# DRYER_CONTROLLER.net
KiCad netlist of a schematic drawn in EAGLE
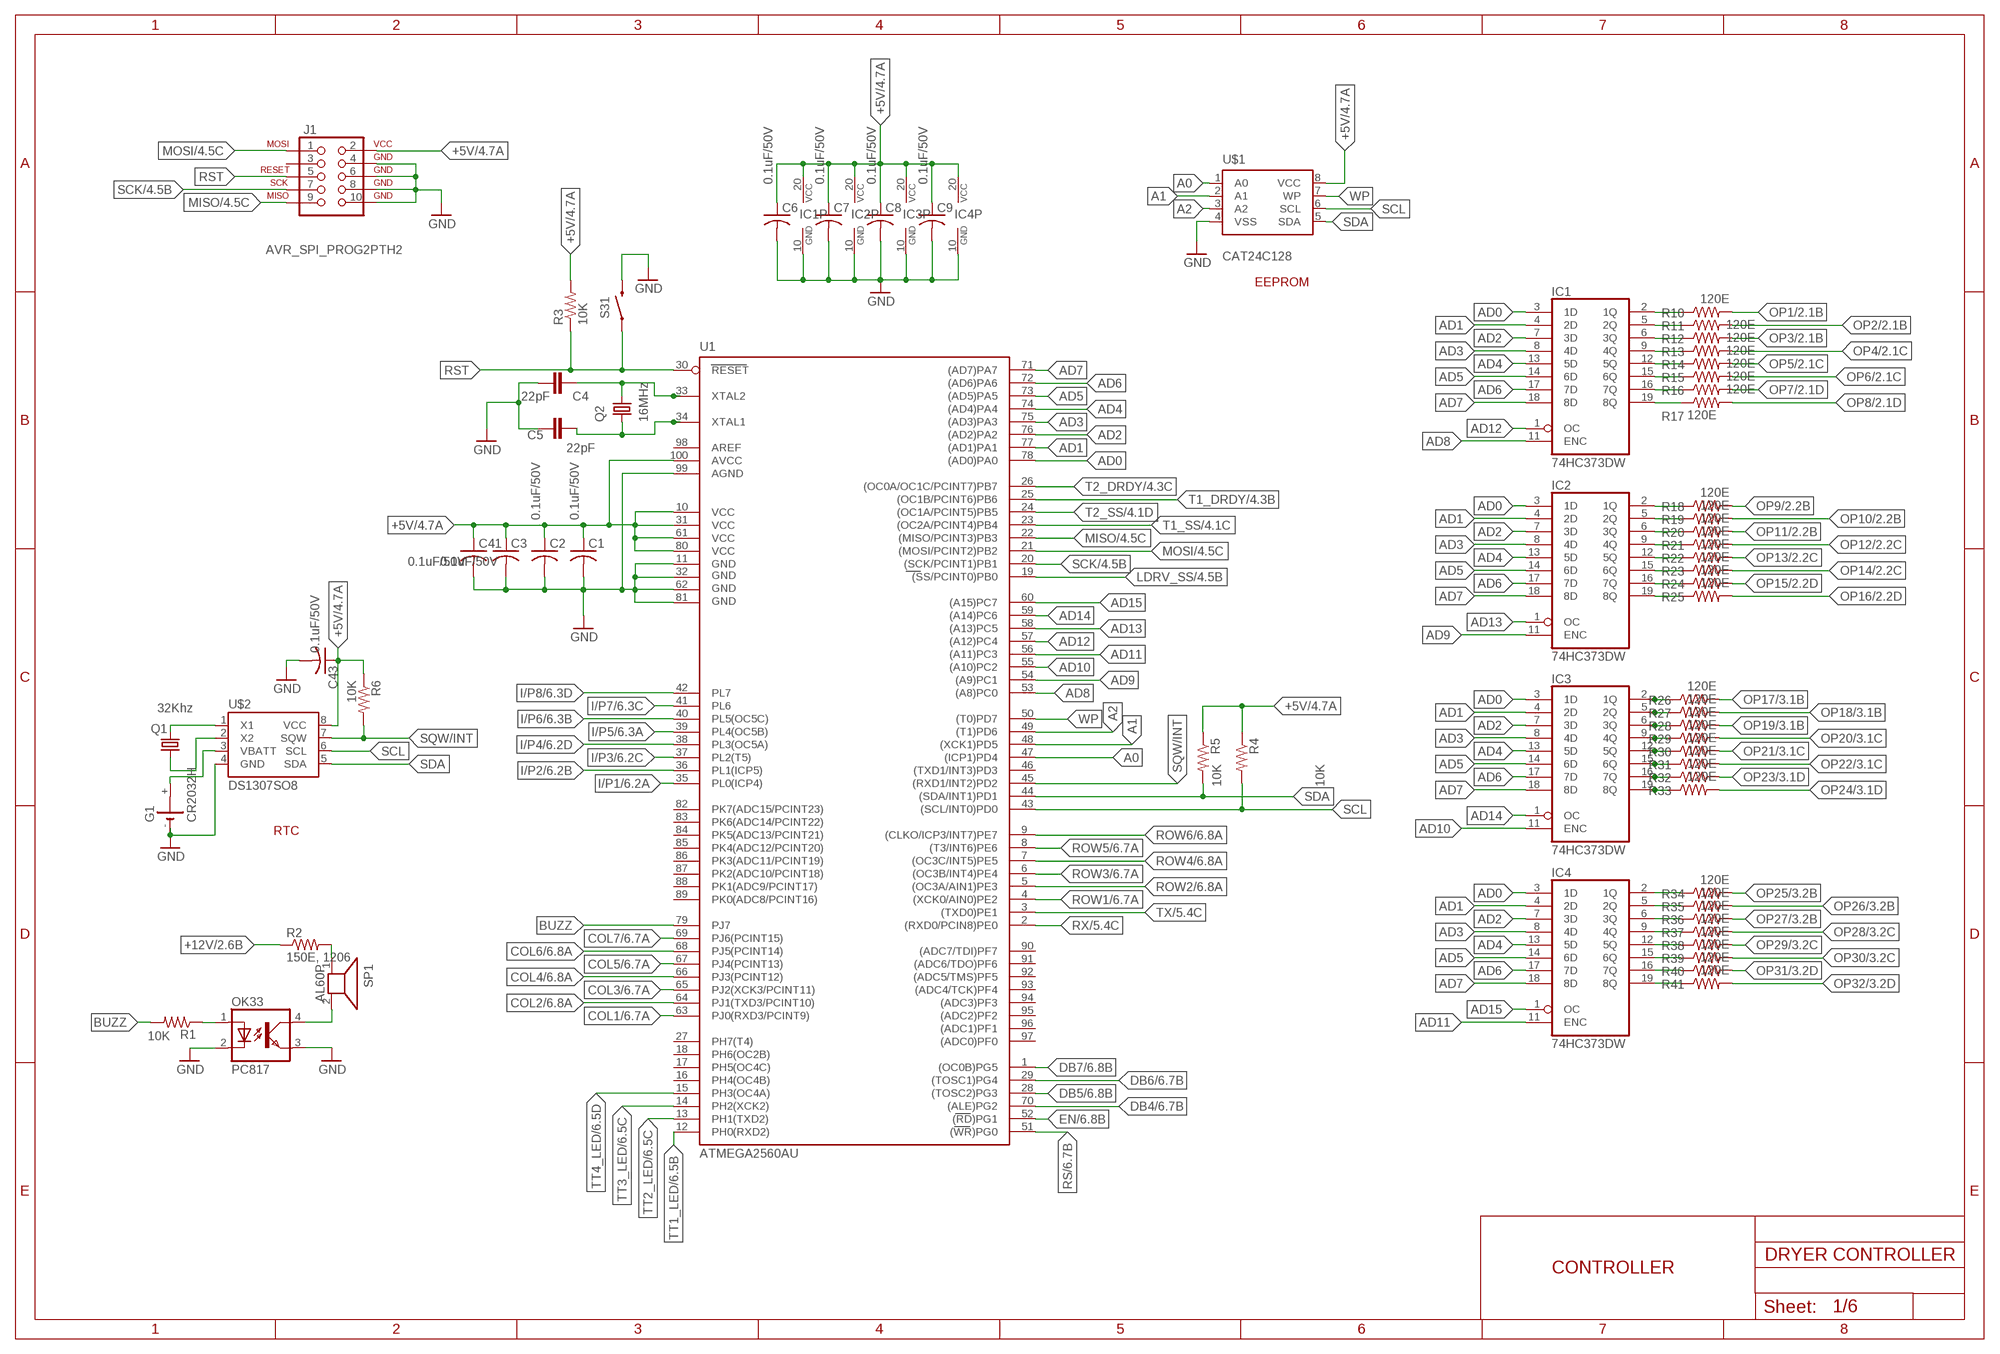
[diagram p0: schematic, sheet 1]
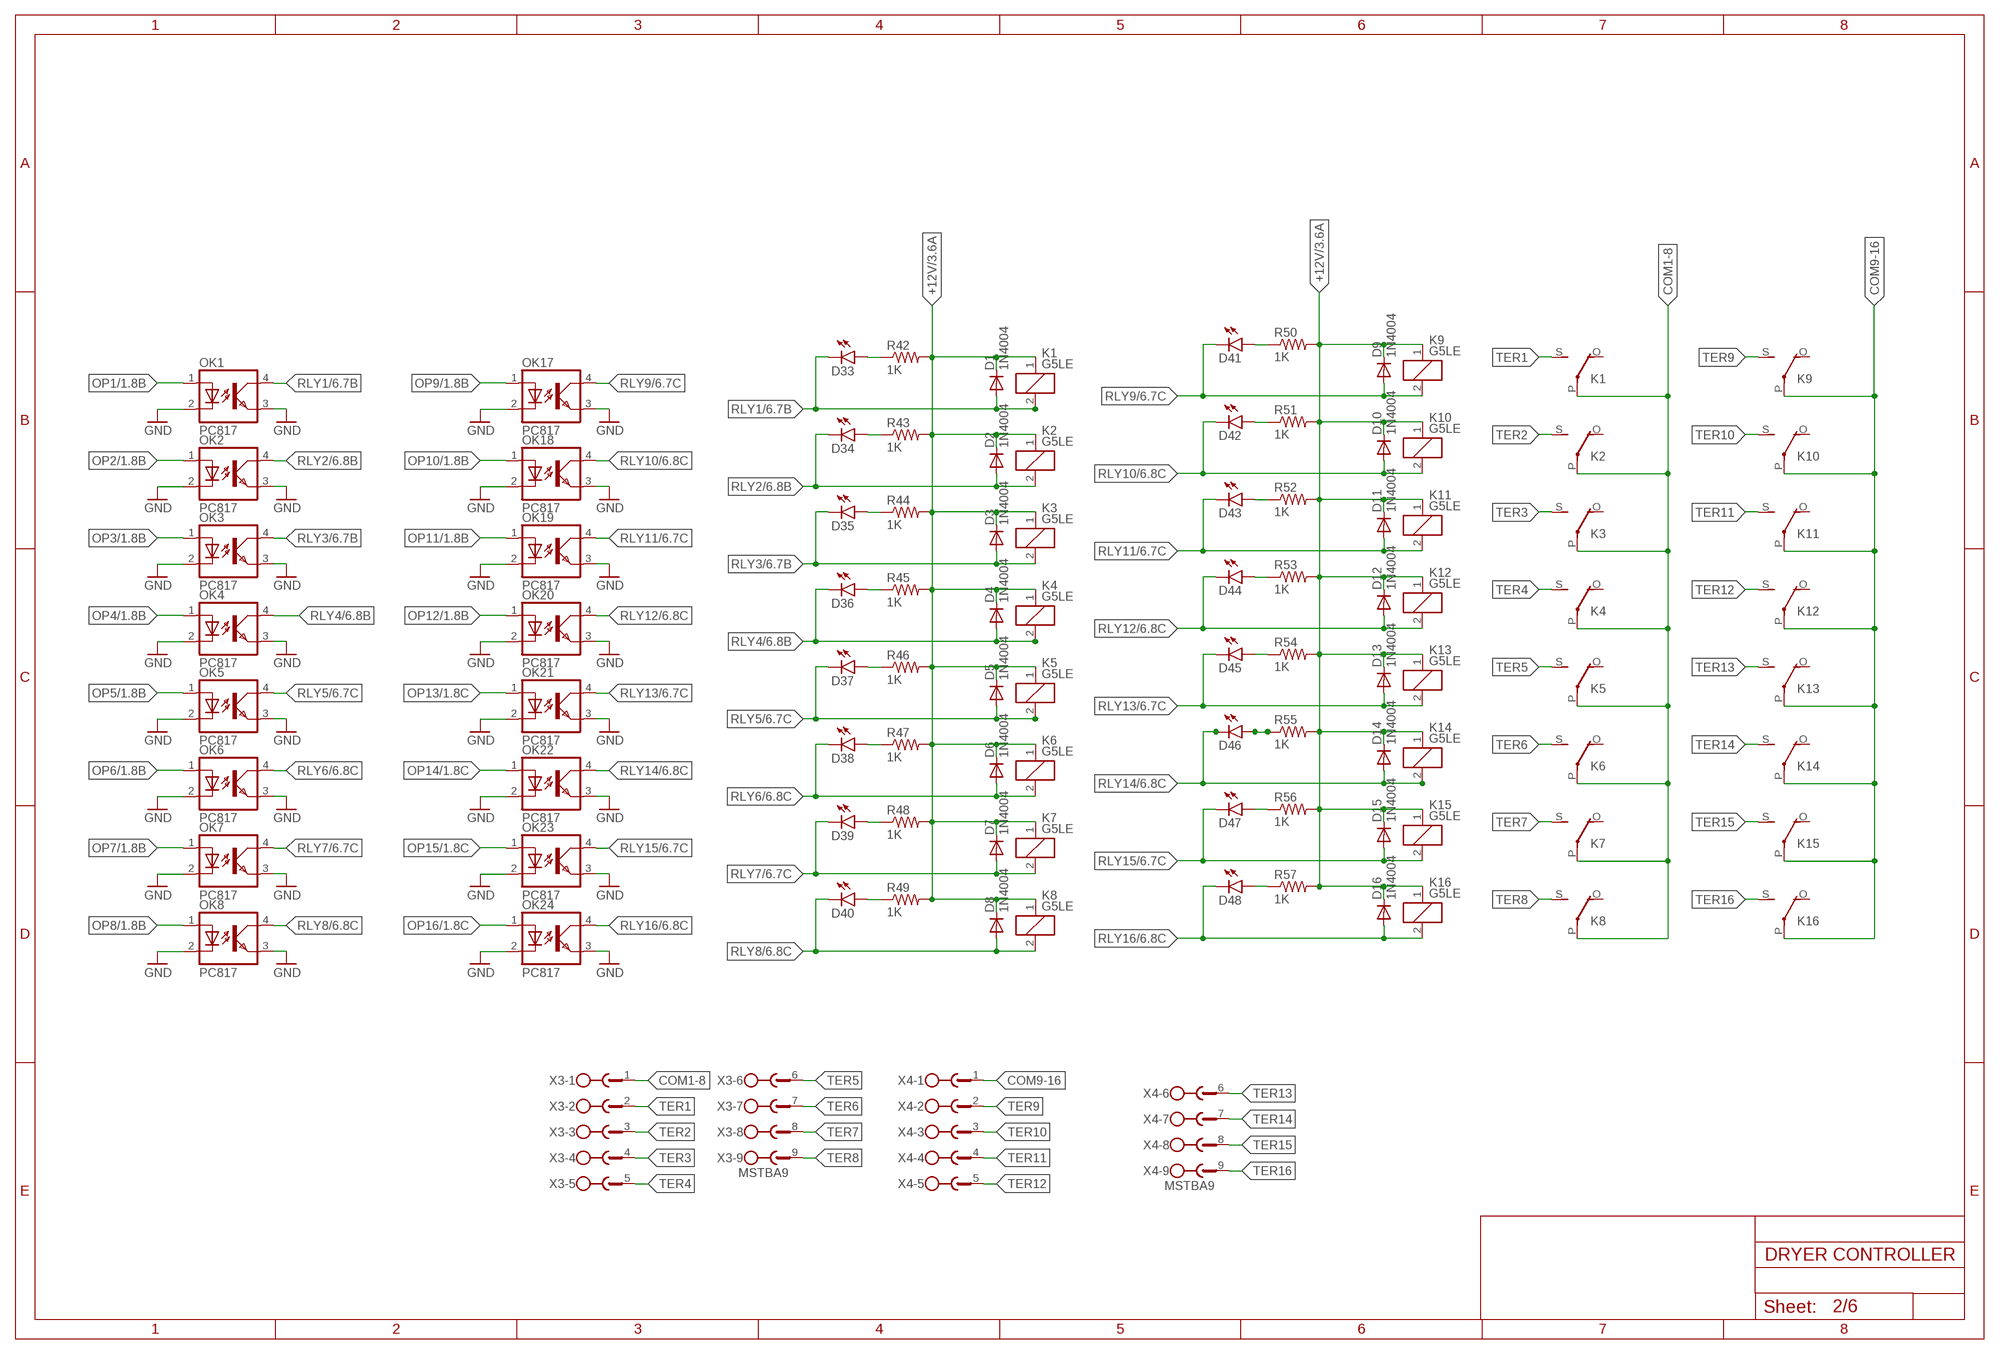
[diagram p1: schematic, sheet 2]
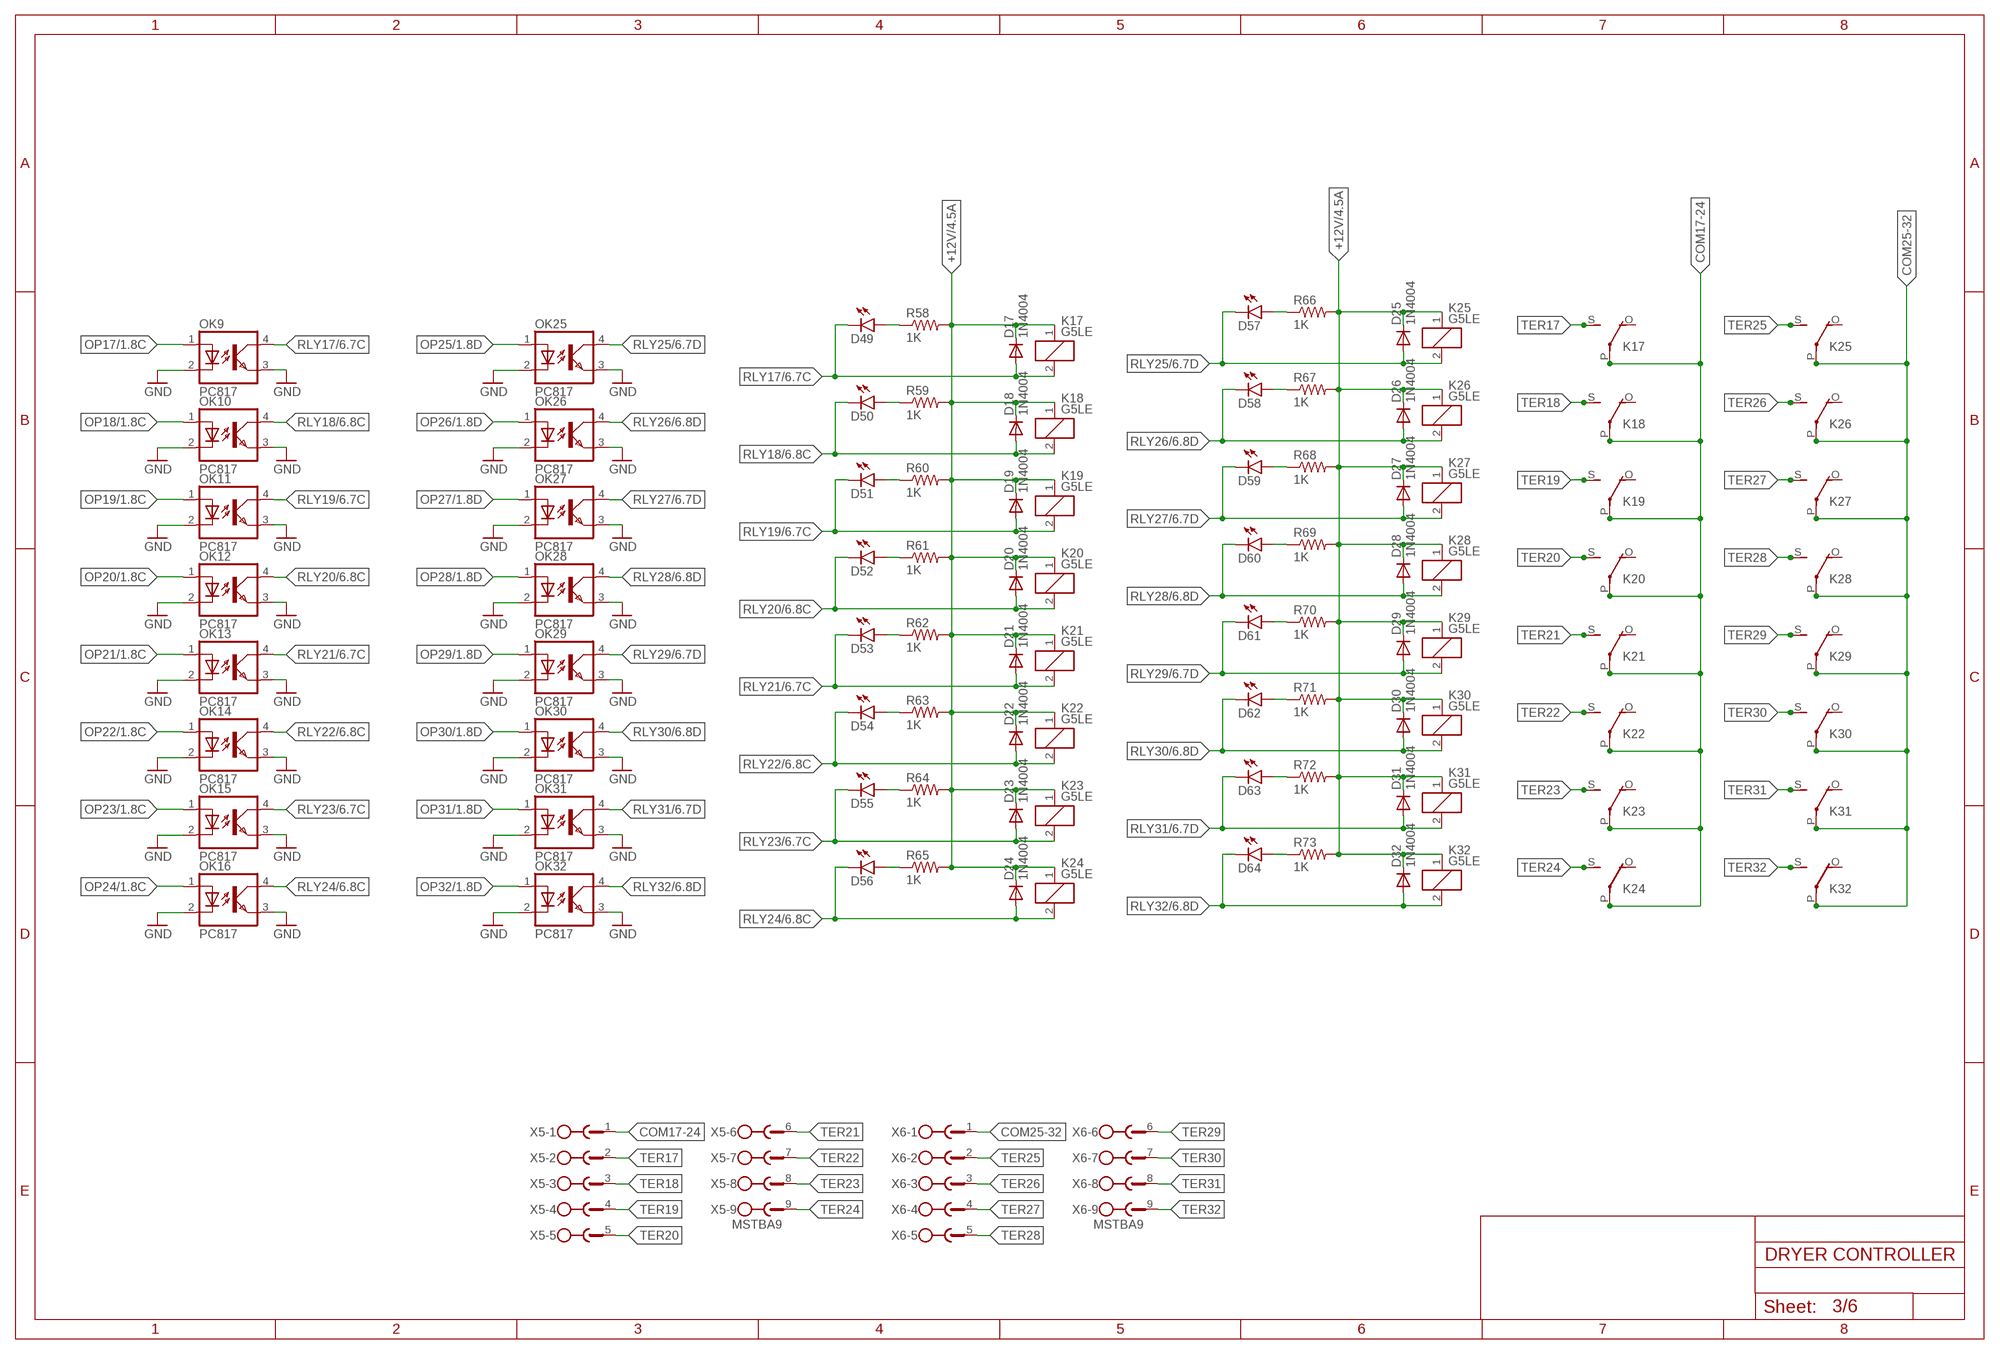
[diagram p2: schematic, sheet 3]
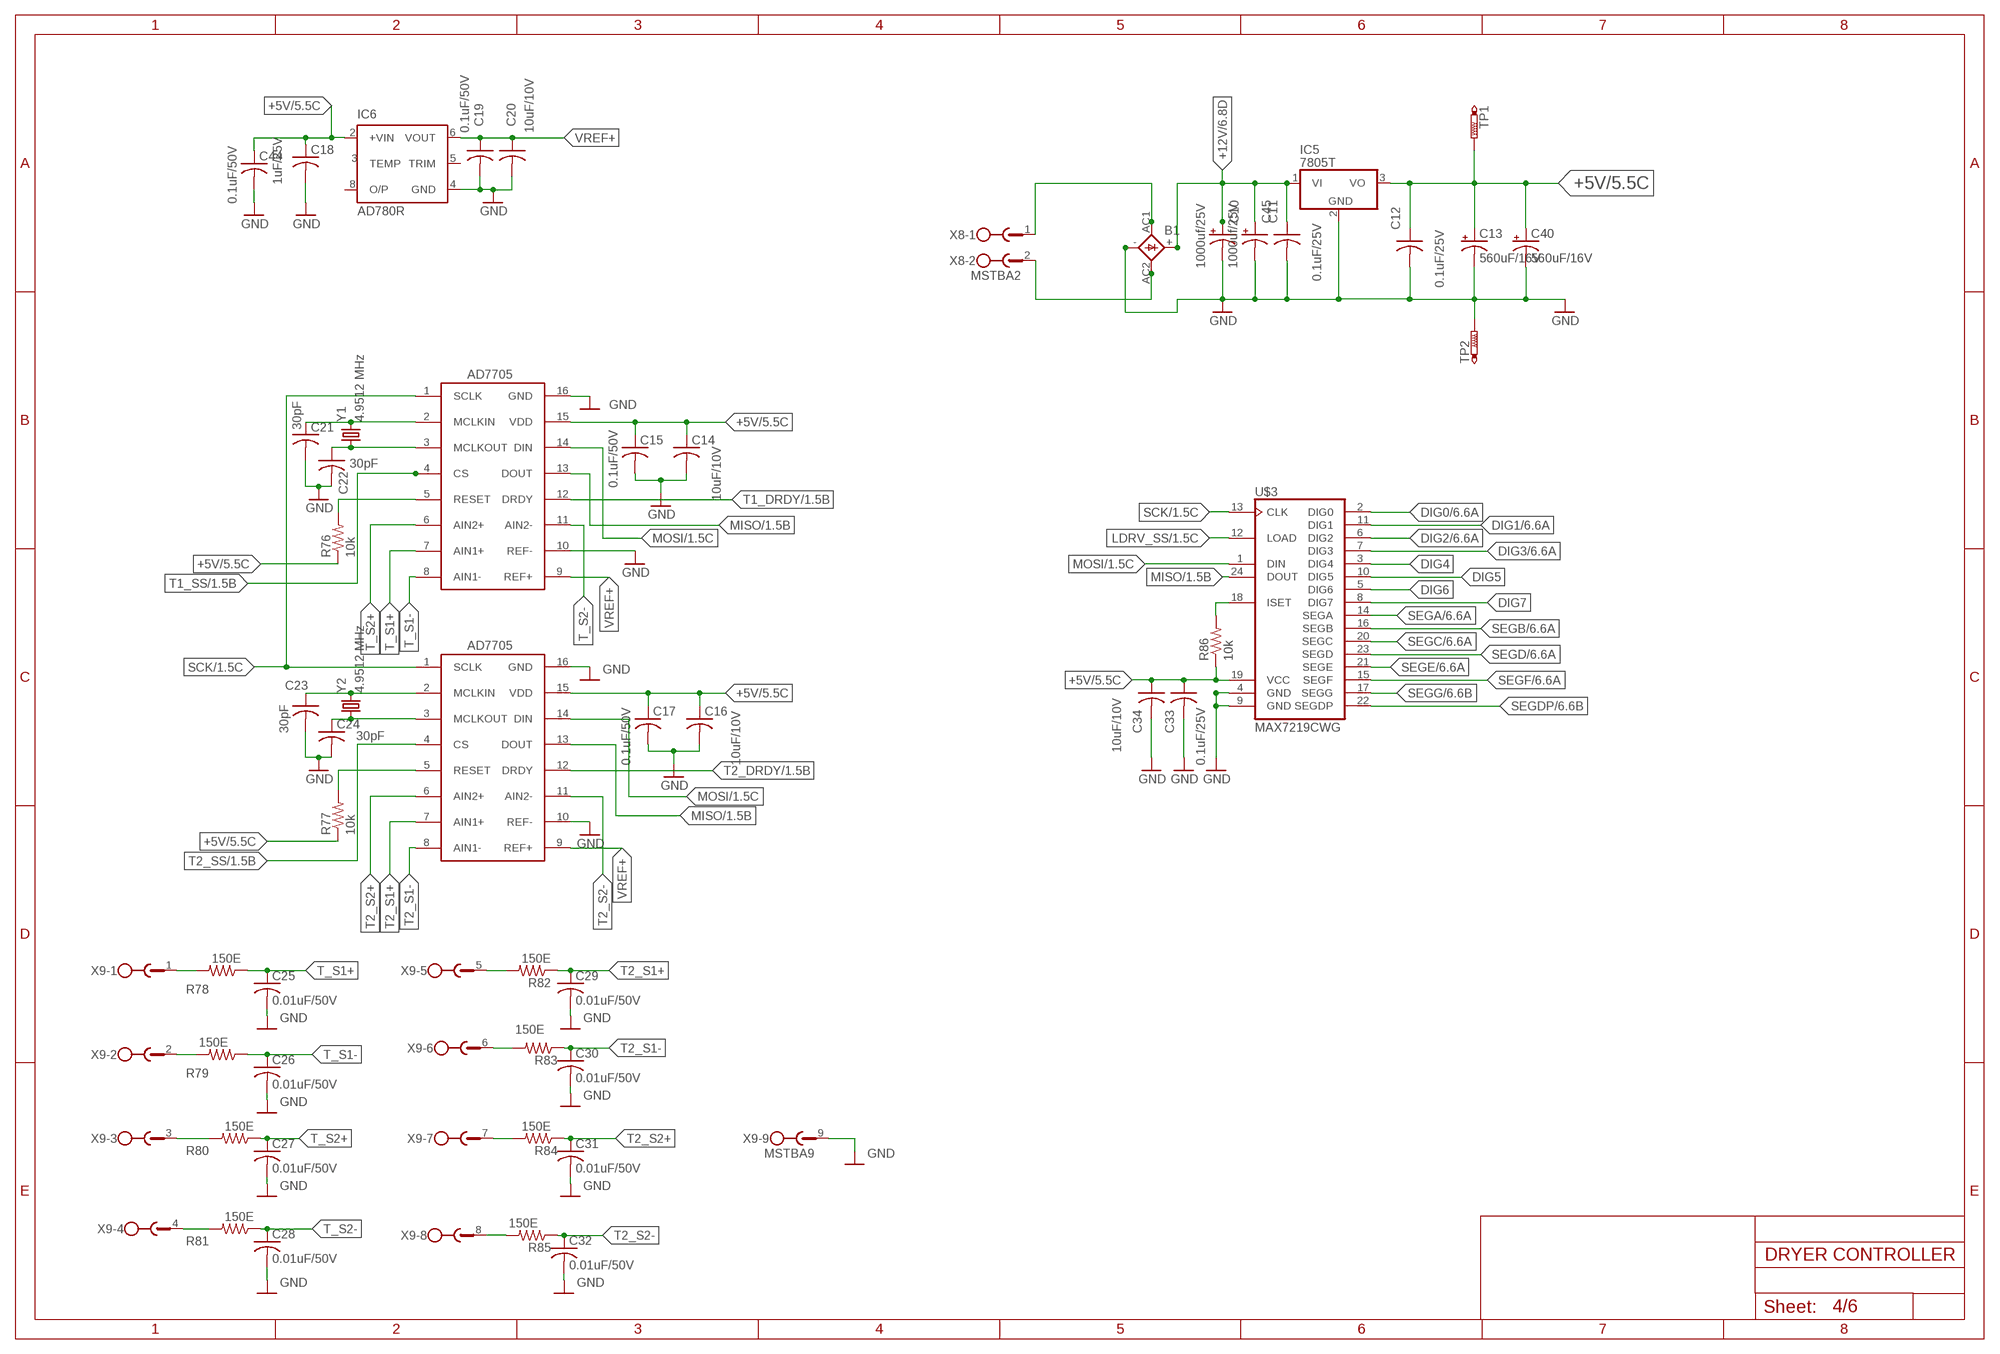
[diagram p3: schematic, sheet 4]
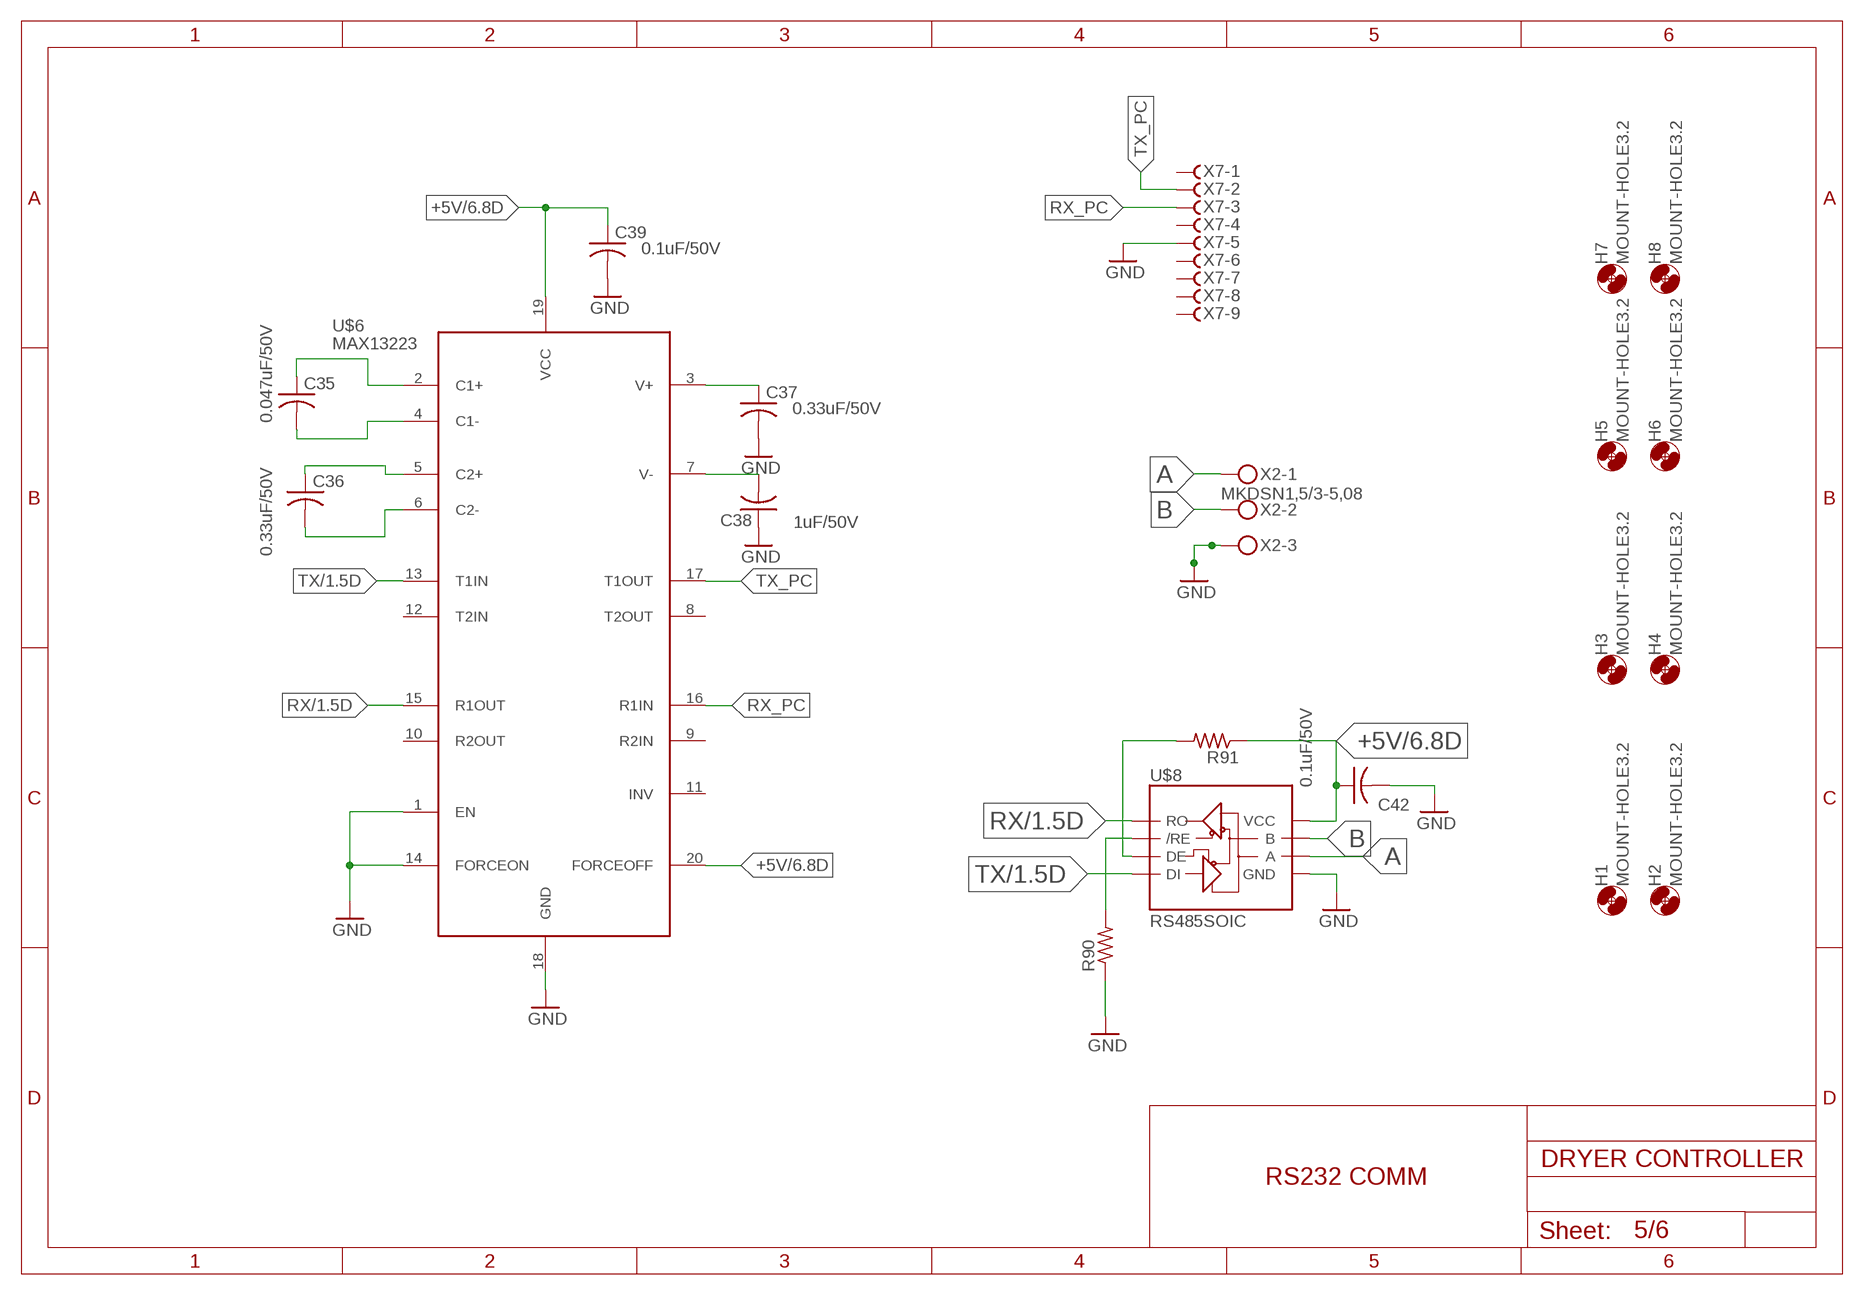
[diagram p4: schematic, sheet 5]
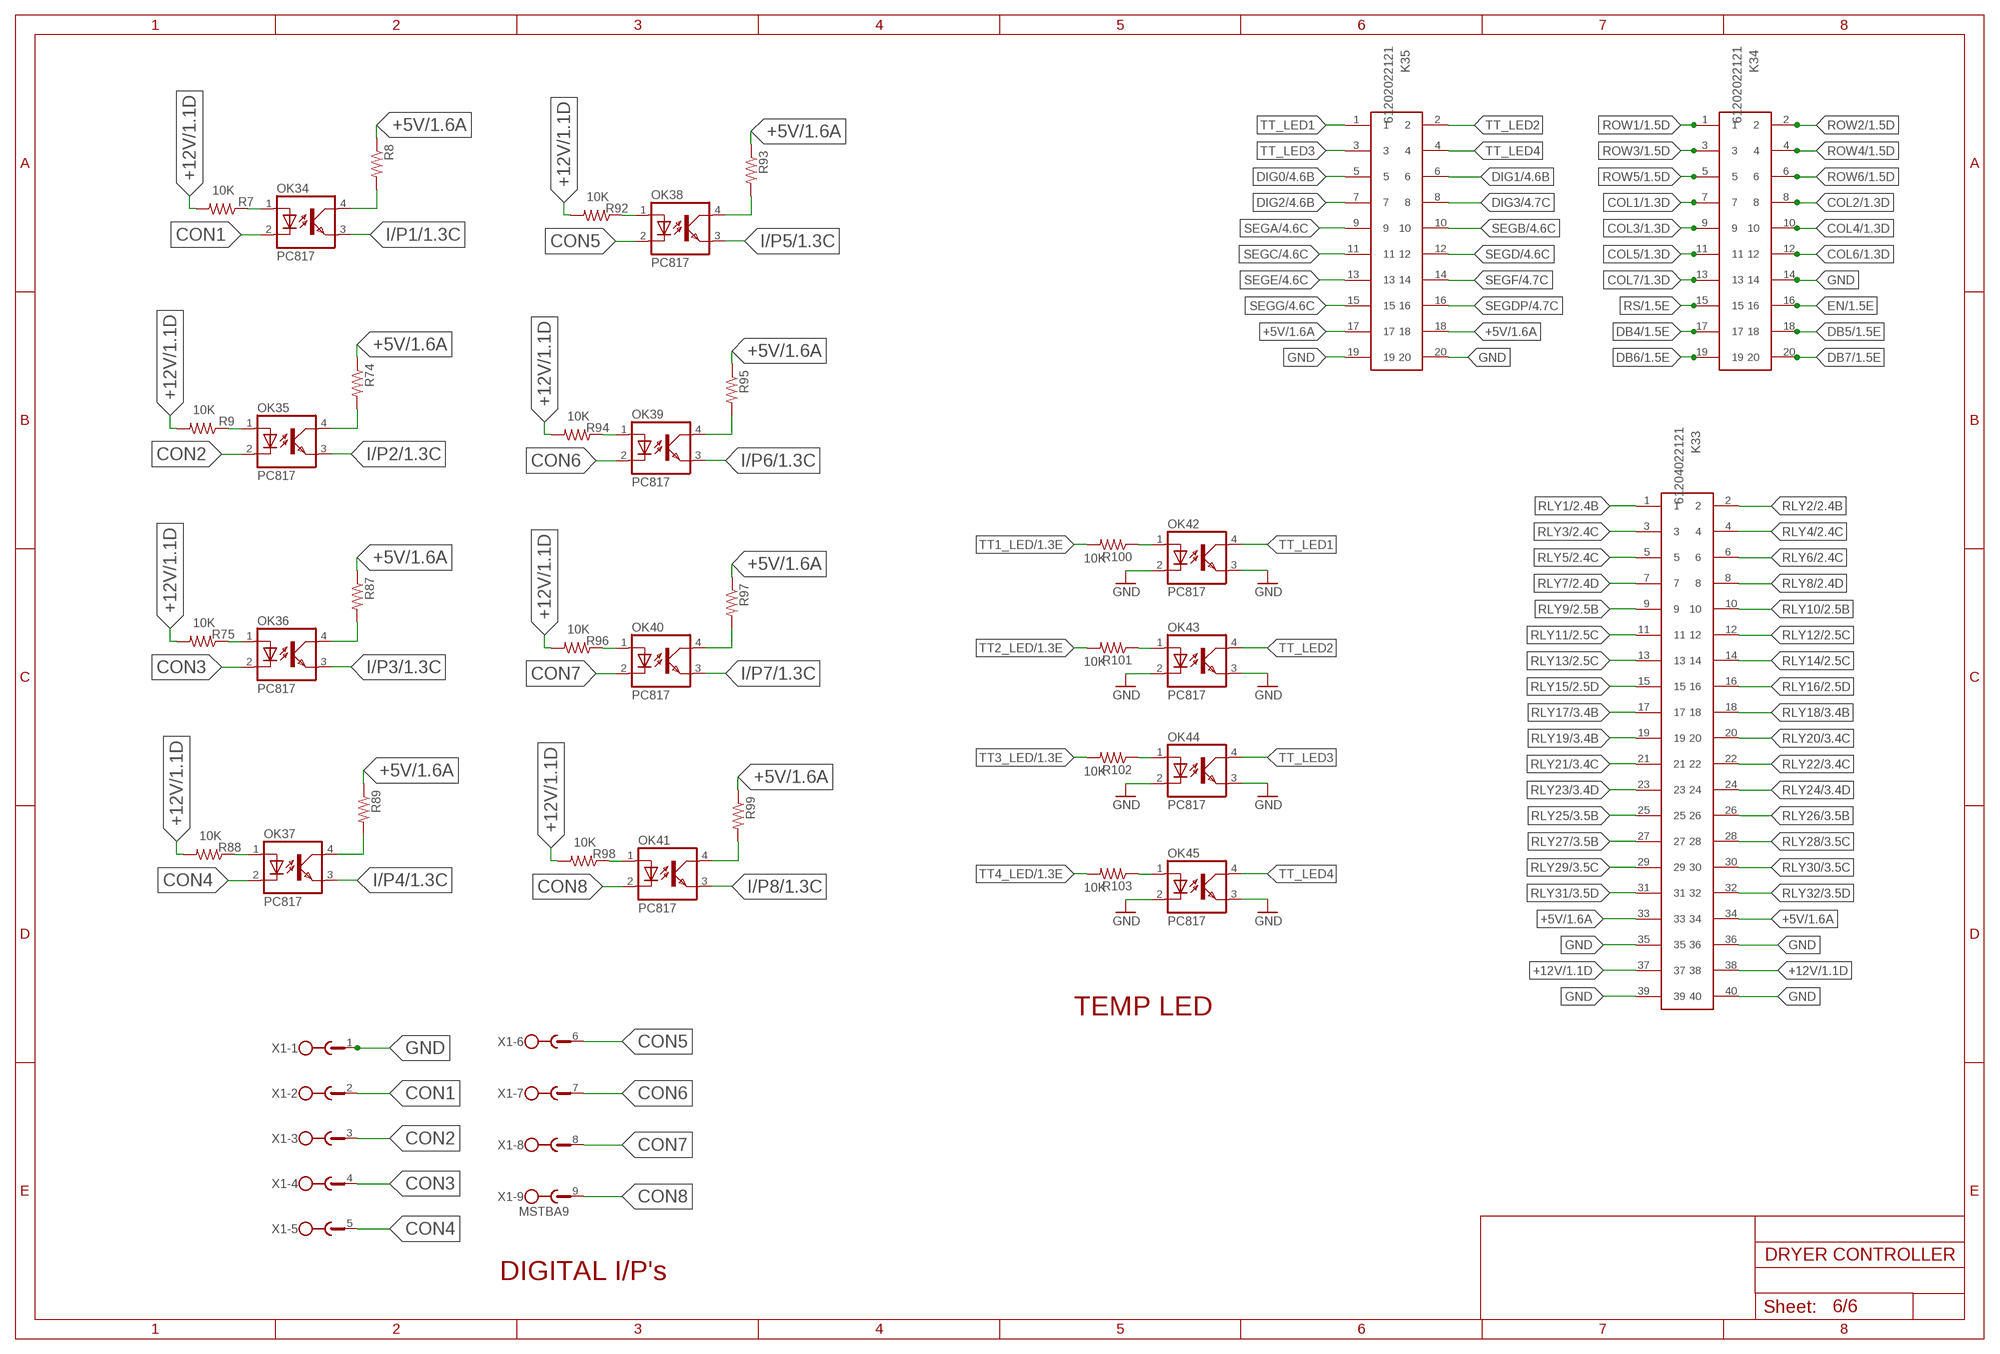
[diagram p5: schematic, sheet 6]

(export (version "E")
  (design (tool "Eeschema 10.0.6"))
  (components
    (comp (ref "B1")
      (value "2KBP")
      (footprint "eagle-import:2KBP")
      (libsource (lib "eagle-import") (part "2KBP"))
    )
    (comp (ref "C10")
      (value "1000uf/25V")
      (footprint "eagle-import:CPOL-RADIAL-1000UF-25V-KIT")
      (libsource (lib "eagle-import") (part "1000UF-25V(PTH)KIT"))
    )
    (comp (ref "C11")
      (value "0.1uF/25V")
      (footprint "eagle-import:C0805K")
      (libsource (lib "eagle-import") (part "C-USC0805K"))
    )
    (comp (ref "C12")
      (value "0.1uF/25V")
      (footprint "eagle-import:C0805K")
      (libsource (lib "eagle-import") (part "C-USC0805K"))
    )
    (comp (ref "C13")
      (value "560uF/16V")
      (footprint "eagle-import:E5-8,5")
      (libsource (lib "eagle-import") (part "CPOL-USE5-8.5"))
    )
    (comp (ref "C14")
      (value "10uF/10V")
      (footprint "eagle-import:C0805K")
      (libsource (lib "eagle-import") (part "C-USC0805K"))
    )
    (comp (ref "C15")
      (value "0.1uF/50V")
      (footprint "eagle-import:C0805K")
      (libsource (lib "eagle-import") (part "C-USC0805K"))
    )
    (comp (ref "C16")
      (value "10uF/10V")
      (footprint "eagle-import:C0805K")
      (libsource (lib "eagle-import") (part "C-USC0805K"))
    )
    (comp (ref "C17")
      (value "0.1uF/50V")
      (footprint "eagle-import:C0805K")
      (libsource (lib "eagle-import") (part "C-USC0805K"))
    )
    (comp (ref "C18")
      (value "1uF/25V")
      (footprint "eagle-import:C0805K")
      (libsource (lib "eagle-import") (part "C-USC0805K"))
    )
    (comp (ref "C19")
      (value "0.1uF/50V")
      (footprint "eagle-import:C0805K")
      (libsource (lib "eagle-import") (part "C-USC0805K"))
    )
    (comp (ref "C20")
      (value "10uF/10V")
      (footprint "eagle-import:C0805K")
      (libsource (lib "eagle-import") (part "C-USC0805K"))
    )
    (comp (ref "C21")
      (value "30pF")
      (footprint "eagle-import:C0603K")
      (libsource (lib "eagle-import") (part "C-USC0603K"))
    )
    (comp (ref "C22")
      (value "30pF")
      (footprint "eagle-import:C0603K")
      (libsource (lib "eagle-import") (part "C-USC0603K"))
    )
    (comp (ref "C23")
      (value "30pF")
      (footprint "eagle-import:C0603K")
      (libsource (lib "eagle-import") (part "C-USC0603K"))
    )
    (comp (ref "C24")
      (value "30pF")
      (footprint "eagle-import:C0603K")
      (libsource (lib "eagle-import") (part "C-USC0603K"))
    )
    (comp (ref "C25")
      (value "0.01uF/50V")
      (footprint "eagle-import:C0603")
      (libsource (lib "eagle-import") (part "C-USC0603"))
    )
    (comp (ref "C26")
      (value "0.01uF/50V")
      (footprint "eagle-import:C0603")
      (libsource (lib "eagle-import") (part "C-USC0603"))
    )
    (comp (ref "C27")
      (value "0.01uF/50V")
      (footprint "eagle-import:C0603")
      (libsource (lib "eagle-import") (part "C-USC0603"))
    )
    (comp (ref "C28")
      (value "0.01uF/50V")
      (footprint "eagle-import:C0603")
      (libsource (lib "eagle-import") (part "C-USC0603"))
    )
    (comp (ref "C29")
      (value "0.01uF/50V")
      (footprint "eagle-import:C0603")
      (libsource (lib "eagle-import") (part "C-USC0603"))
    )
    (comp (ref "C30")
      (value "0.01uF/50V")
      (footprint "eagle-import:C0603")
      (libsource (lib "eagle-import") (part "C-USC0603"))
    )
    (comp (ref "C31")
      (value "0.01uF/50V")
      (footprint "eagle-import:C0603")
      (libsource (lib "eagle-import") (part "C-USC0603"))
    )
    (comp (ref "C32")
      (value "0.01uF/50V")
      (footprint "eagle-import:C0603")
      (libsource (lib "eagle-import") (part "C-USC0603"))
    )
    (comp (ref "C33")
      (value "0.1uF/25V")
      (footprint "eagle-import:C0805K")
      (libsource (lib "eagle-import") (part "C-USC0805K"))
    )
    (comp (ref "C34")
      (value "10uF/10V")
      (footprint "eagle-import:C0805K")
      (libsource (lib "eagle-import") (part "C-USC0805K"))
    )
    (comp (ref "C40")
      (value "560uF/16V")
      (footprint "eagle-import:E5-8,5")
      (libsource (lib "eagle-import") (part "CPOL-USE5-8.5"))
    )
    (comp (ref "C44")
      (value "0.1uF/50V")
      (footprint "eagle-import:C0805K")
      (libsource (lib "eagle-import") (part "C-USC0805K"))
    )
    (comp (ref "C45")
      (value "1000uf/25V")
      (footprint "eagle-import:CPOL-RADIAL-1000UF-25V-KIT")
      (libsource (lib "eagle-import") (part "1000UF-25V(PTH)KIT"))
    )
    (comp (ref "IC5")
      (value "7805T")
      (footprint "eagle-import:TO220H")
      (libsource (lib "eagle-import") (part "78T05"))
    )
    (comp (ref "IC6")
      (value "AD780R")
      (footprint "eagle-import:SO8")
      (fields (field (name "MPN") "AD780BRZ-REEL"))
      (libsource (lib "eagle-import") (part "AD780R"))
    )
    (comp (ref "R76")
      (value "10k")
      (footprint "eagle-import:R0805")
      (libsource (lib "eagle-import") (part "R-US_R0805"))
    )
    (comp (ref "R77")
      (value "10k")
      (footprint "eagle-import:R0805")
      (libsource (lib "eagle-import") (part "R-US_R0805"))
    )
    (comp (ref "R78")
      (value "150E")
      (footprint "eagle-import:R0805")
      (libsource (lib "eagle-import") (part "R-US_R0805"))
    )
    (comp (ref "R79")
      (value "150E")
      (footprint "eagle-import:R0805")
      (libsource (lib "eagle-import") (part "R-US_R0805"))
    )
    (comp (ref "R80")
      (value "150E")
      (footprint "eagle-import:R0805")
      (libsource (lib "eagle-import") (part "R-US_R0805"))
    )
    (comp (ref "R81")
      (value "150E")
      (footprint "eagle-import:R0805")
      (libsource (lib "eagle-import") (part "R-US_R0805"))
    )
    (comp (ref "R82")
      (value "150E")
      (footprint "eagle-import:R0805")
      (libsource (lib "eagle-import") (part "R-US_R0805"))
    )
    (comp (ref "R83")
      (value "150E")
      (footprint "eagle-import:R0805")
      (libsource (lib "eagle-import") (part "R-US_R0805"))
    )
    (comp (ref "R84")
      (value "150E")
      (footprint "eagle-import:R0805")
      (libsource (lib "eagle-import") (part "R-US_R0805"))
    )
    (comp (ref "R85")
      (value "150E")
      (footprint "eagle-import:R0805")
      (libsource (lib "eagle-import") (part "R-US_R0805"))
    )
    (comp (ref "R86")
      (value "10k")
      (footprint "eagle-import:R0805")
      (libsource (lib "eagle-import") (part "R-US_R0805"))
    )
    (comp (ref "TP1")
      (value "PTR1B2,54")
      (footprint "eagle-import:B2,54")
      (libsource (lib "eagle-import") (part "PTR1B2,54"))
    )
    (comp (ref "TP2")
      (value "PTR1B2,54")
      (footprint "eagle-import:B2,54")
      (libsource (lib "eagle-import") (part "PTR1B2,54"))
    )
    (comp (ref "U$3")
      (value "MAX7219CWG")
      (footprint "eagle-import:SO24L")
      (libsource (lib "eagle-import") (part "MAX7219CWG"))
    )
    (comp (ref "U$4")
      (value "AD7705")
      (footprint "eagle-import:SO-16W")
      (libsource (lib "eagle-import") (part "AD7705"))
    )
    (comp (ref "U$5")
      (value "AD7705")
      (footprint "eagle-import:SO-16W")
      (libsource (lib "eagle-import") (part "AD7705"))
    )
    (comp (ref "X8")
      (value "MSTBA2")
      (footprint "eagle-import:MSTBA2")
      (fields (field (name "MF") "FARNELL") (field (name "MPN") "1757242"))
      (libsource (lib "eagle-import") (part "MSTBA2"))
    )
    (comp (ref "X9")
      (value "MSTBA9")
      (footprint "eagle-import:MSTBA9")
      (fields (field (name "MF") "FARNELL") (field (name "MPN") "1757310"))
      (libsource (lib "eagle-import") (part "MSTBA9"))
    )
    (comp (ref "Y1")
      (value "4.9512 MHz")
      (footprint "eagle-import:HC49U-V")
      (libsource (lib "eagle-import") (part "CRYSTALHC49UV"))
    )
    (comp (ref "Y2")
      (value "4.9512 MHz")
      (footprint "eagle-import:HC49U-V")
      (libsource (lib "eagle-import") (part "CRYSTALHC49UV"))
    )
    (comp (ref "D17")
      (value "1N4004")
      (footprint "eagle-import:DO41-10")
      (libsource (lib "eagle-import") (part "1N4004"))
    )
    (comp (ref "D18")
      (value "1N4004")
      (footprint "eagle-import:DO41-10")
      (libsource (lib "eagle-import") (part "1N4004"))
    )
    (comp (ref "D19")
      (value "1N4004")
      (footprint "eagle-import:DO41-10")
      (libsource (lib "eagle-import") (part "1N4004"))
    )
    (comp (ref "D20")
      (value "1N4004")
      (footprint "eagle-import:DO41-10")
      (libsource (lib "eagle-import") (part "1N4004"))
    )
    (comp (ref "D21")
      (value "1N4004")
      (footprint "eagle-import:DO41-10")
      (libsource (lib "eagle-import") (part "1N4004"))
    )
    (comp (ref "D22")
      (value "1N4004")
      (footprint "eagle-import:DO41-10")
      (libsource (lib "eagle-import") (part "1N4004"))
    )
    (comp (ref "D23")
      (value "1N4004")
      (footprint "eagle-import:DO41-10")
      (libsource (lib "eagle-import") (part "1N4004"))
    )
    (comp (ref "D24")
      (value "1N4004")
      (footprint "eagle-import:DO41-10")
      (libsource (lib "eagle-import") (part "1N4004"))
    )
    (comp (ref "D25")
      (value "1N4004")
      (footprint "eagle-import:DO41-10")
      (libsource (lib "eagle-import") (part "1N4004"))
    )
    (comp (ref "D26")
      (value "1N4004")
      (footprint "eagle-import:DO41-10")
      (libsource (lib "eagle-import") (part "1N4004"))
    )
    (comp (ref "D27")
      (value "1N4004")
      (footprint "eagle-import:DO41-10")
      (libsource (lib "eagle-import") (part "1N4004"))
    )
    (comp (ref "D28")
      (value "1N4004")
      (footprint "eagle-import:DO41-10")
      (libsource (lib "eagle-import") (part "1N4004"))
    )
    (comp (ref "D29")
      (value "1N4004")
      (footprint "eagle-import:DO41-10")
      (libsource (lib "eagle-import") (part "1N4004"))
    )
    (comp (ref "D30")
      (value "1N4004")
      (footprint "eagle-import:DO41-10")
      (libsource (lib "eagle-import") (part "1N4004"))
    )
    (comp (ref "D31")
      (value "1N4004")
      (footprint "eagle-import:DO41-10")
      (libsource (lib "eagle-import") (part "1N4004"))
    )
    (comp (ref "D32")
      (value "1N4004")
      (footprint "eagle-import:DO41-10")
      (libsource (lib "eagle-import") (part "1N4004"))
    )
    (comp (ref "D49")
      (value "LED1206")
      (footprint "eagle-import:LED-1206")
      (libsource (lib "eagle-import") (part "LED1206"))
    )
    (comp (ref "D50")
      (value "LED1206")
      (footprint "eagle-import:LED-1206")
      (libsource (lib "eagle-import") (part "LED1206"))
    )
    (comp (ref "D51")
      (value "LED1206")
      (footprint "eagle-import:LED-1206")
      (libsource (lib "eagle-import") (part "LED1206"))
    )
    (comp (ref "D52")
      (value "LED1206")
      (footprint "eagle-import:LED-1206")
      (libsource (lib "eagle-import") (part "LED1206"))
    )
    (comp (ref "D53")
      (value "LED1206")
      (footprint "eagle-import:LED-1206")
      (libsource (lib "eagle-import") (part "LED1206"))
    )
    (comp (ref "D54")
      (value "LED1206")
      (footprint "eagle-import:LED-1206")
      (libsource (lib "eagle-import") (part "LED1206"))
    )
    (comp (ref "D55")
      (value "LED1206")
      (footprint "eagle-import:LED-1206")
      (libsource (lib "eagle-import") (part "LED1206"))
    )
    (comp (ref "D56")
      (value "LED1206")
      (footprint "eagle-import:LED-1206")
      (libsource (lib "eagle-import") (part "LED1206"))
    )
    (comp (ref "D57")
      (value "LED1206")
      (footprint "eagle-import:LED-1206")
      (libsource (lib "eagle-import") (part "LED1206"))
    )
    (comp (ref "D58")
      (value "LED1206")
      (footprint "eagle-import:LED-1206")
      (libsource (lib "eagle-import") (part "LED1206"))
    )
    (comp (ref "D59")
      (value "LED1206")
      (footprint "eagle-import:LED-1206")
      (libsource (lib "eagle-import") (part "LED1206"))
    )
    (comp (ref "D60")
      (value "LED1206")
      (footprint "eagle-import:LED-1206")
      (libsource (lib "eagle-import") (part "LED1206"))
    )
    (comp (ref "D61")
      (value "LED1206")
      (footprint "eagle-import:LED-1206")
      (libsource (lib "eagle-import") (part "LED1206"))
    )
    (comp (ref "D62")
      (value "LED1206")
      (footprint "eagle-import:LED-1206")
      (libsource (lib "eagle-import") (part "LED1206"))
    )
    (comp (ref "D63")
      (value "LED1206")
      (footprint "eagle-import:LED-1206")
      (libsource (lib "eagle-import") (part "LED1206"))
    )
    (comp (ref "D64")
      (value "LED1206")
      (footprint "eagle-import:LED-1206")
      (libsource (lib "eagle-import") (part "LED1206"))
    )
    (comp (ref "K17")
      (value "G5LE")
      (footprint "eagle-import:G5LE")
      (libsource (lib "eagle-import") (part "G5LE"))
    )
    (comp (ref "K18")
      (value "G5LE")
      (footprint "eagle-import:G5LE")
      (libsource (lib "eagle-import") (part "G5LE"))
    )
    (comp (ref "K19")
      (value "G5LE")
      (footprint "eagle-import:G5LE")
      (libsource (lib "eagle-import") (part "G5LE"))
    )
    (comp (ref "K20")
      (value "G5LE")
      (footprint "eagle-import:G5LE")
      (libsource (lib "eagle-import") (part "G5LE"))
    )
    (comp (ref "K21")
      (value "G5LE")
      (footprint "eagle-import:G5LE")
      (libsource (lib "eagle-import") (part "G5LE"))
    )
    (comp (ref "K22")
      (value "G5LE")
      (footprint "eagle-import:G5LE")
      (libsource (lib "eagle-import") (part "G5LE"))
    )
    (comp (ref "K23")
      (value "G5LE")
      (footprint "eagle-import:G5LE")
      (libsource (lib "eagle-import") (part "G5LE"))
    )
    (comp (ref "K24")
      (value "G5LE")
      (footprint "eagle-import:G5LE")
      (libsource (lib "eagle-import") (part "G5LE"))
    )
    (comp (ref "K25")
      (value "G5LE")
      (footprint "eagle-import:G5LE")
      (libsource (lib "eagle-import") (part "G5LE"))
    )
    (comp (ref "K26")
      (value "G5LE")
      (footprint "eagle-import:G5LE")
      (libsource (lib "eagle-import") (part "G5LE"))
    )
    (comp (ref "K27")
      (value "G5LE")
      (footprint "eagle-import:G5LE")
      (libsource (lib "eagle-import") (part "G5LE"))
    )
    (comp (ref "K28")
      (value "G5LE")
      (footprint "eagle-import:G5LE")
      (libsource (lib "eagle-import") (part "G5LE"))
    )
    (comp (ref "K29")
      (value "G5LE")
      (footprint "eagle-import:G5LE")
      (libsource (lib "eagle-import") (part "G5LE"))
    )
    (comp (ref "K30")
      (value "G5LE")
      (footprint "eagle-import:G5LE")
      (libsource (lib "eagle-import") (part "G5LE"))
    )
    (comp (ref "K31")
      (value "G5LE")
      (footprint "eagle-import:G5LE")
      (libsource (lib "eagle-import") (part "G5LE"))
    )
    (comp (ref "K32")
      (value "G5LE")
      (footprint "eagle-import:G5LE")
      (libsource (lib "eagle-import") (part "G5LE"))
    )
    (comp (ref "OK9")
      (value "PC817")
      (footprint "eagle-import:DIL04")
      (fields (field (name "MPN") "PC817X4J000F"))
      (libsource (lib "eagle-import") (part "PC817"))
    )
    (comp (ref "OK10")
      (value "PC817")
      (footprint "eagle-import:DIL04")
      (fields (field (name "MPN") "PC817X4J000F"))
      (libsource (lib "eagle-import") (part "PC817"))
    )
    (comp (ref "OK11")
      (value "PC817")
      (footprint "eagle-import:DIL04")
      (fields (field (name "MPN") "PC817X4J000F"))
      (libsource (lib "eagle-import") (part "PC817"))
    )
    (comp (ref "OK12")
      (value "PC817")
      (footprint "eagle-import:DIL04")
      (fields (field (name "MPN") "PC817X4J000F"))
      (libsource (lib "eagle-import") (part "PC817"))
    )
    (comp (ref "OK13")
      (value "PC817")
      (footprint "eagle-import:DIL04")
      (fields (field (name "MPN") "PC817X4J000F"))
      (libsource (lib "eagle-import") (part "PC817"))
    )
    (comp (ref "OK14")
      (value "PC817")
      (footprint "eagle-import:DIL04")
      (fields (field (name "MPN") "PC817X4J000F"))
      (libsource (lib "eagle-import") (part "PC817"))
    )
    (comp (ref "OK15")
      (value "PC817")
      (footprint "eagle-import:DIL04")
      (fields (field (name "MPN") "PC817X4J000F"))
      (libsource (lib "eagle-import") (part "PC817"))
    )
    (comp (ref "OK16")
      (value "PC817")
      (footprint "eagle-import:DIL04")
      (fields (field (name "MPN") "PC817X4J000F"))
      (libsource (lib "eagle-import") (part "PC817"))
    )
    (comp (ref "OK25")
      (value "PC817")
      (footprint "eagle-import:DIL04")
      (fields (field (name "MPN") "PC817X4J000F"))
      (libsource (lib "eagle-import") (part "PC817"))
    )
    (comp (ref "OK26")
      (value "PC817")
      (footprint "eagle-import:DIL04")
      (fields (field (name "MPN") "PC817X4J000F"))
      (libsource (lib "eagle-import") (part "PC817"))
    )
    (comp (ref "OK27")
      (value "PC817")
      (footprint "eagle-import:DIL04")
      (fields (field (name "MPN") "PC817X4J000F"))
      (libsource (lib "eagle-import") (part "PC817"))
    )
    (comp (ref "OK28")
      (value "PC817")
      (footprint "eagle-import:DIL04")
      (fields (field (name "MPN") "PC817X4J000F"))
      (libsource (lib "eagle-import") (part "PC817"))
    )
    (comp (ref "OK29")
      (value "PC817")
      (footprint "eagle-import:DIL04")
      (fields (field (name "MPN") "PC817X4J000F"))
      (libsource (lib "eagle-import") (part "PC817"))
    )
    (comp (ref "OK30")
      (value "PC817")
      (footprint "eagle-import:DIL04")
      (fields (field (name "MPN") "PC817X4J000F"))
      (libsource (lib "eagle-import") (part "PC817"))
    )
    (comp (ref "OK31")
      (value "PC817")
      (footprint "eagle-import:DIL04")
      (fields (field (name "MPN") "PC817X4J000F"))
      (libsource (lib "eagle-import") (part "PC817"))
    )
    (comp (ref "OK32")
      (value "PC817")
      (footprint "eagle-import:DIL04")
      (fields (field (name "MPN") "PC817X4J000F"))
      (libsource (lib "eagle-import") (part "PC817"))
    )
    (comp (ref "R58")
      (value "1K")
      (footprint "eagle-import:R0805")
      (libsource (lib "eagle-import") (part "R-US_R0805"))
    )
    (comp (ref "R59")
      (value "1K")
      (footprint "eagle-import:R0805")
      (libsource (lib "eagle-import") (part "R-US_R0805"))
    )
    (comp (ref "R60")
      (value "1K")
      (footprint "eagle-import:R0805")
      (libsource (lib "eagle-import") (part "R-US_R0805"))
    )
    (comp (ref "R61")
      (value "1K")
      (footprint "eagle-import:R0805")
      (libsource (lib "eagle-import") (part "R-US_R0805"))
    )
    (comp (ref "R62")
      (value "1K")
      (footprint "eagle-import:R0805")
      (libsource (lib "eagle-import") (part "R-US_R0805"))
    )
    (comp (ref "R63")
      (value "1K")
      (footprint "eagle-import:R0805")
      (libsource (lib "eagle-import") (part "R-US_R0805"))
    )
    (comp (ref "R64")
      (value "1K")
      (footprint "eagle-import:R0805")
      (libsource (lib "eagle-import") (part "R-US_R0805"))
    )
    (comp (ref "R65")
      (value "1K")
      (footprint "eagle-import:R0805")
      (libsource (lib "eagle-import") (part "R-US_R0805"))
    )
    (comp (ref "R66")
      (value "1K")
      (footprint "eagle-import:R0805")
      (libsource (lib "eagle-import") (part "R-US_R0805"))
    )
    (comp (ref "R67")
      (value "1K")
      (footprint "eagle-import:R0805")
      (libsource (lib "eagle-import") (part "R-US_R0805"))
    )
    (comp (ref "R68")
      (value "1K")
      (footprint "eagle-import:R0805")
      (libsource (lib "eagle-import") (part "R-US_R0805"))
    )
    (comp (ref "R69")
      (value "1K")
      (footprint "eagle-import:R0805")
      (libsource (lib "eagle-import") (part "R-US_R0805"))
    )
    (comp (ref "R70")
      (value "1K")
      (footprint "eagle-import:R0805")
      (libsource (lib "eagle-import") (part "R-US_R0805"))
    )
    (comp (ref "R71")
      (value "1K")
      (footprint "eagle-import:R0805")
      (libsource (lib "eagle-import") (part "R-US_R0805"))
    )
    (comp (ref "R72")
      (value "1K")
      (footprint "eagle-import:R0805")
      (libsource (lib "eagle-import") (part "R-US_R0805"))
    )
    (comp (ref "R73")
      (value "1K")
      (footprint "eagle-import:R0805")
      (libsource (lib "eagle-import") (part "R-US_R0805"))
    )
    (comp (ref "X5")
      (value "MSTBA9")
      (footprint "eagle-import:MSTBA9")
      (fields (field (name "MF") "FARNELL") (field (name "MPN") "1757310"))
      (libsource (lib "eagle-import") (part "MSTBA9"))
    )
    (comp (ref "X6")
      (value "MSTBA9")
      (footprint "eagle-import:MSTBA9")
      (fields (field (name "MF") "FARNELL") (field (name "MPN") "1757310"))
      (libsource (lib "eagle-import") (part "MSTBA9"))
    )
    (comp (ref "K33")
      (value "61204022121")
      (footprint "eagle-import:61204022121")
      (libsource (lib "eagle-import") (part "61204022121"))
    )
    (comp (ref "K34")
      (value "61202022121")
      (footprint "eagle-import:61202022121")
      (libsource (lib "eagle-import") (part "61202022121"))
    )
    (comp (ref "K35")
      (value "61202022121")
      (footprint "eagle-import:61202022121")
      (libsource (lib "eagle-import") (part "61202022121"))
    )
    (comp (ref "OK34")
      (value "PC817")
      (footprint "eagle-import:DIL04")
      (fields (field (name "MPN") "PC817X4J000F"))
      (libsource (lib "eagle-import") (part "PC817"))
    )
    (comp (ref "OK35")
      (value "PC817")
      (footprint "eagle-import:DIL04")
      (fields (field (name "MPN") "PC817X4J000F"))
      (libsource (lib "eagle-import") (part "PC817"))
    )
    (comp (ref "OK36")
      (value "PC817")
      (footprint "eagle-import:DIL04")
      (fields (field (name "MPN") "PC817X4J000F"))
      (libsource (lib "eagle-import") (part "PC817"))
    )
    (comp (ref "OK37")
      (value "PC817")
      (footprint "eagle-import:DIL04")
      (fields (field (name "MPN") "PC817X4J000F"))
      (libsource (lib "eagle-import") (part "PC817"))
    )
    (comp (ref "OK38")
      (value "PC817")
      (footprint "eagle-import:DIL04")
      (fields (field (name "MPN") "PC817X4J000F"))
      (libsource (lib "eagle-import") (part "PC817"))
    )
    (comp (ref "OK39")
      (value "PC817")
      (footprint "eagle-import:DIL04")
      (fields (field (name "MPN") "PC817X4J000F"))
      (libsource (lib "eagle-import") (part "PC817"))
    )
    (comp (ref "OK40")
      (value "PC817")
      (footprint "eagle-import:DIL04")
      (fields (field (name "MPN") "PC817X4J000F"))
      (libsource (lib "eagle-import") (part "PC817"))
    )
    (comp (ref "OK41")
      (value "PC817")
      (footprint "eagle-import:DIL04")
      (fields (field (name "MPN") "PC817X4J000F"))
      (libsource (lib "eagle-import") (part "PC817"))
    )
    (comp (ref "OK42")
      (value "PC817")
      (footprint "eagle-import:DIL04")
      (fields (field (name "MPN") "PC817X4J000F"))
      (libsource (lib "eagle-import") (part "PC817"))
    )
    (comp (ref "OK43")
      (value "PC817")
      (footprint "eagle-import:DIL04")
      (fields (field (name "MPN") "PC817X4J000F"))
      (libsource (lib "eagle-import") (part "PC817"))
    )
    (comp (ref "OK44")
      (value "PC817")
      (footprint "eagle-import:DIL04")
      (fields (field (name "MPN") "PC817X4J000F"))
      (libsource (lib "eagle-import") (part "PC817"))
    )
    (comp (ref "OK45")
      (value "PC817")
      (footprint "eagle-import:DIL04")
      (fields (field (name "MPN") "PC817X4J000F"))
      (libsource (lib "eagle-import") (part "PC817"))
    )
    (comp (ref "R7")
      (value "10K")
      (footprint "eagle-import:R0805")
      (libsource (lib "eagle-import") (part "R-US_R0805"))
    )
    (comp (ref "R8")
      (value "R-US_R1206")
      (footprint "eagle-import:R1206")
      (libsource (lib "eagle-import") (part "R-US_R1206"))
    )
    (comp (ref "R9")
      (value "10K")
      (footprint "eagle-import:R0805")
      (libsource (lib "eagle-import") (part "R-US_R0805"))
    )
    (comp (ref "R74")
      (value "R-US_R1206")
      (footprint "eagle-import:R1206")
      (libsource (lib "eagle-import") (part "R-US_R1206"))
    )
    (comp (ref "R75")
      (value "10K")
      (footprint "eagle-import:R0805")
      (libsource (lib "eagle-import") (part "R-US_R0805"))
    )
    (comp (ref "R87")
      (value "R-US_R1206")
      (footprint "eagle-import:R1206")
      (libsource (lib "eagle-import") (part "R-US_R1206"))
    )
    (comp (ref "R88")
      (value "10K")
      (footprint "eagle-import:R0805")
      (libsource (lib "eagle-import") (part "R-US_R0805"))
    )
    (comp (ref "R89")
      (value "R-US_R1206")
      (footprint "eagle-import:R1206")
      (libsource (lib "eagle-import") (part "R-US_R1206"))
    )
    (comp (ref "R92")
      (value "10K")
      (footprint "eagle-import:R0805")
      (libsource (lib "eagle-import") (part "R-US_R0805"))
    )
    (comp (ref "R93")
      (value "R-US_R1206")
      (footprint "eagle-import:R1206")
      (libsource (lib "eagle-import") (part "R-US_R1206"))
    )
    (comp (ref "R94")
      (value "10K")
      (footprint "eagle-import:R0805")
      (libsource (lib "eagle-import") (part "R-US_R0805"))
    )
    (comp (ref "R95")
      (value "R-US_R1206")
      (footprint "eagle-import:R1206")
      (libsource (lib "eagle-import") (part "R-US_R1206"))
    )
    (comp (ref "R96")
      (value "10K")
      (footprint "eagle-import:R0805")
      (libsource (lib "eagle-import") (part "R-US_R0805"))
    )
    (comp (ref "R97")
      (value "R-US_R1206")
      (footprint "eagle-import:R1206")
      (libsource (lib "eagle-import") (part "R-US_R1206"))
    )
    (comp (ref "R98")
      (value "10K")
      (footprint "eagle-import:R0805")
      (libsource (lib "eagle-import") (part "R-US_R0805"))
    )
    (comp (ref "R99")
      (value "R-US_R1206")
      (footprint "eagle-import:R1206")
      (libsource (lib "eagle-import") (part "R-US_R1206"))
    )
    (comp (ref "R100")
      (value "10K")
      (footprint "eagle-import:R0805")
      (libsource (lib "eagle-import") (part "R-US_R0805"))
    )
    (comp (ref "R101")
      (value "10K")
      (footprint "eagle-import:R0805")
      (libsource (lib "eagle-import") (part "R-US_R0805"))
    )
    (comp (ref "R102")
      (value "10K")
      (footprint "eagle-import:R0805")
      (libsource (lib "eagle-import") (part "R-US_R0805"))
    )
    (comp (ref "R103")
      (value "10K")
      (footprint "eagle-import:R0805")
      (libsource (lib "eagle-import") (part "R-US_R0805"))
    )
    (comp (ref "X1")
      (value "MSTBA9")
      (footprint "eagle-import:MSTBA9")
      (fields (field (name "MF") "FARNELL") (field (name "MPN") "1757310"))
      (libsource (lib "eagle-import") (part "MSTBA9"))
    )
    (comp (ref "C1")
      (value "0.1uF/50V")
      (footprint "eagle-import:C0805K")
      (libsource (lib "eagle-import") (part "C-USC0805K"))
    )
    (comp (ref "C2")
      (value "0.1uF/50V")
      (footprint "eagle-import:C0805K")
      (libsource (lib "eagle-import") (part "C-USC0805K"))
    )
    (comp (ref "C3")
      (value "0.1uF/50V")
      (footprint "eagle-import:C0805K")
      (libsource (lib "eagle-import") (part "C-USC0805K"))
    )
    (comp (ref "C4")
      (value "22pF")
      (footprint "eagle-import:0805")
      (libsource (lib "eagle-import") (part "CAP0805"))
    )
    (comp (ref "C5")
      (value "22pF")
      (footprint "eagle-import:0805")
      (libsource (lib "eagle-import") (part "CAP0805"))
    )
    (comp (ref "C6")
      (value "0.1uF/50V")
      (footprint "eagle-import:C0805K")
      (libsource (lib "eagle-import") (part "C-USC0805K"))
    )
    (comp (ref "C7")
      (value "0.1uF/50V")
      (footprint "eagle-import:C0805K")
      (libsource (lib "eagle-import") (part "C-USC0805K"))
    )
    (comp (ref "C8")
      (value "0.1uF/50V")
      (footprint "eagle-import:C0805K")
      (libsource (lib "eagle-import") (part "C-USC0805K"))
    )
    (comp (ref "C9")
      (value "0.1uF/50V")
      (footprint "eagle-import:C0805K")
      (libsource (lib "eagle-import") (part "C-USC0805K"))
    )
    (comp (ref "C41")
      (value "0.1uF/50V")
      (footprint "eagle-import:C0805K")
      (libsource (lib "eagle-import") (part "C-USC0805K"))
    )
    (comp (ref "C43")
      (value "0.1uF/50V")
      (footprint "eagle-import:C0805K")
      (libsource (lib "eagle-import") (part "C-USC0805K"))
    )
    (comp (ref "G1")
      (value "CR2032H")
      (footprint "eagle-import:CR2032H")
      (libsource (lib "eagle-import") (part "CR2032H"))
    )
    (comp (ref "IC1")
      (value "74HC373DW")
      (footprint "eagle-import:SO20W")
      (libsource (lib "eagle-import") (part "74373DWHC"))
    )
    (comp (ref "IC2")
      (value "74HC373DW")
      (footprint "eagle-import:SO20W")
      (libsource (lib "eagle-import") (part "74373DWHC"))
    )
    (comp (ref "IC3")
      (value "74HC373DW")
      (footprint "eagle-import:SO20W")
      (libsource (lib "eagle-import") (part "74373DWHC"))
    )
    (comp (ref "IC4")
      (value "74HC373DW")
      (footprint "eagle-import:SO20W")
      (libsource (lib "eagle-import") (part "74373DWHC"))
    )
    (comp (ref "J1")
      (value "AVR_SPI_PROG2PTH2")
      (footprint "eagle-import:2X5-SHROUDED")
      (libsource (lib "eagle-import") (part "AVR_SPI_PROG2PTH2"))
    )
    (comp (ref "OK33")
      (value "PC817")
      (footprint "eagle-import:DIL04")
      (fields (field (name "MPN") "PC817X4J000F"))
      (libsource (lib "eagle-import") (part "PC817"))
    )
    (comp (ref "Q1")
      (value "32Khz")
      (footprint "eagle-import:HC49_S")
      (fields (field (name "OC_FARNELL") "1667008") (field (name "OC_NEWARK") "unknown"))
      (libsource (lib "eagle-import") (part "CRYSTALHC49S"))
    )
    (comp (ref "Q2")
      (value "16MHz")
      (footprint "eagle-import:HC49_S")
      (libsource (lib "eagle-import") (part "CRYSTALHC49S"))
    )
    (comp (ref "R1")
      (value "10K")
      (footprint "eagle-import:R0805")
      (libsource (lib "eagle-import") (part "R-US_R0805"))
    )
    (comp (ref "R2")
      (value "150E, 1206")
      (footprint "eagle-import:R1206")
      (libsource (lib "eagle-import") (part "R-US_R1206"))
    )
    (comp (ref "R3")
      (value "10K")
      (footprint "eagle-import:R0805")
      (libsource (lib "eagle-import") (part "R-US_R0805"))
    )
    (comp (ref "R4")
      (value "10K")
      (footprint "eagle-import:R0805")
      (libsource (lib "eagle-import") (part "R-US_R0805"))
    )
    (comp (ref "R5")
      (value "10K")
      (footprint "eagle-import:R0805")
      (libsource (lib "eagle-import") (part "R-US_R0805"))
    )
    (comp (ref "R6")
      (value "10K")
      (footprint "eagle-import:R0805")
      (libsource (lib "eagle-import") (part "R-US_R0805"))
    )
    (comp (ref "R10")
      (value "120E")
      (footprint "eagle-import:R0805")
      (libsource (lib "eagle-import") (part "R-US_R0805"))
    )
    (comp (ref "R11")
      (value "120E")
      (footprint "eagle-import:R0805")
      (libsource (lib "eagle-import") (part "R-US_R0805"))
    )
    (comp (ref "R12")
      (value "120E")
      (footprint "eagle-import:R0805")
      (libsource (lib "eagle-import") (part "R-US_R0805"))
    )
    (comp (ref "R13")
      (value "120E")
      (footprint "eagle-import:R0805")
      (libsource (lib "eagle-import") (part "R-US_R0805"))
    )
    (comp (ref "R14")
      (value "120E")
      (footprint "eagle-import:R0805")
      (libsource (lib "eagle-import") (part "R-US_R0805"))
    )
    (comp (ref "R15")
      (value "120E")
      (footprint "eagle-import:R0805")
      (libsource (lib "eagle-import") (part "R-US_R0805"))
    )
    (comp (ref "R16")
      (value "120E")
      (footprint "eagle-import:R0805")
      (libsource (lib "eagle-import") (part "R-US_R0805"))
    )
    (comp (ref "R17")
      (value "120E")
      (footprint "eagle-import:R0805")
      (libsource (lib "eagle-import") (part "R-US_R0805"))
    )
    (comp (ref "R18")
      (value "120E")
      (footprint "eagle-import:R0805")
      (libsource (lib "eagle-import") (part "R-US_R0805"))
    )
    (comp (ref "R19")
      (value "120E")
      (footprint "eagle-import:R0805")
      (libsource (lib "eagle-import") (part "R-US_R0805"))
    )
    (comp (ref "R20")
      (value "120E")
      (footprint "eagle-import:R0805")
      (libsource (lib "eagle-import") (part "R-US_R0805"))
    )
    (comp (ref "R21")
      (value "120E")
      (footprint "eagle-import:R0805")
      (libsource (lib "eagle-import") (part "R-US_R0805"))
    )
    (comp (ref "R22")
      (value "120E")
      (footprint "eagle-import:R0805")
      (libsource (lib "eagle-import") (part "R-US_R0805"))
    )
    (comp (ref "R23")
      (value "120E")
      (footprint "eagle-import:R0805")
      (libsource (lib "eagle-import") (part "R-US_R0805"))
    )
    (comp (ref "R24")
      (value "120E")
      (footprint "eagle-import:R0805")
      (libsource (lib "eagle-import") (part "R-US_R0805"))
    )
    (comp (ref "R25")
      (value "120E")
      (footprint "eagle-import:R0805")
      (libsource (lib "eagle-import") (part "R-US_R0805"))
    )
    (comp (ref "R26")
      (value "120E")
      (footprint "eagle-import:R0805")
      (libsource (lib "eagle-import") (part "R-US_R0805"))
    )
    (comp (ref "R27")
      (value "120E")
      (footprint "eagle-import:R0805")
      (libsource (lib "eagle-import") (part "R-US_R0805"))
    )
    (comp (ref "R28")
      (value "120E")
      (footprint "eagle-import:R0805")
      (libsource (lib "eagle-import") (part "R-US_R0805"))
    )
    (comp (ref "R29")
      (value "120E")
      (footprint "eagle-import:R0805")
      (libsource (lib "eagle-import") (part "R-US_R0805"))
    )
    (comp (ref "R30")
      (value "120E")
      (footprint "eagle-import:R0805")
      (libsource (lib "eagle-import") (part "R-US_R0805"))
    )
    (comp (ref "R31")
      (value "120E")
      (footprint "eagle-import:R0805")
      (libsource (lib "eagle-import") (part "R-US_R0805"))
    )
    (comp (ref "R32")
      (value "120E")
      (footprint "eagle-import:R0805")
      (libsource (lib "eagle-import") (part "R-US_R0805"))
    )
    (comp (ref "R33")
      (value "120E")
      (footprint "eagle-import:R0805")
      (libsource (lib "eagle-import") (part "R-US_R0805"))
    )
    (comp (ref "R34")
      (value "120E")
      (footprint "eagle-import:R0805")
      (libsource (lib "eagle-import") (part "R-US_R0805"))
    )
    (comp (ref "R35")
      (value "120E")
      (footprint "eagle-import:R0805")
      (libsource (lib "eagle-import") (part "R-US_R0805"))
    )
    (comp (ref "R36")
      (value "120E")
      (footprint "eagle-import:R0805")
      (libsource (lib "eagle-import") (part "R-US_R0805"))
    )
    (comp (ref "R37")
      (value "120E")
      (footprint "eagle-import:R0805")
      (libsource (lib "eagle-import") (part "R-US_R0805"))
    )
    (comp (ref "R38")
      (value "120E")
      (footprint "eagle-import:R0805")
      (libsource (lib "eagle-import") (part "R-US_R0805"))
    )
    (comp (ref "R39")
      (value "120E")
      (footprint "eagle-import:R0805")
      (libsource (lib "eagle-import") (part "R-US_R0805"))
    )
    (comp (ref "R40")
      (value "120E")
      (footprint "eagle-import:R0805")
      (libsource (lib "eagle-import") (part "R-US_R0805"))
    )
    (comp (ref "R41")
      (value "120E")
      (footprint "eagle-import:R0805")
      (libsource (lib "eagle-import") (part "R-US_R0805"))
    )
    (comp (ref "S31")
      (value "SWITCH-MOMENTARY-2SMD-4")
      (footprint "eagle-import:TACTILE_SWITCH_TALL")
      (libsource (lib "eagle-import") (part "SWITCH-MOMENTARY-2SMD-4"))
    )
    (comp (ref "SP1")
      (value "AL60P")
      (footprint "eagle-import:AL60P")
      (libsource (lib "eagle-import") (part "AL60P"))
    )
    (comp (ref "U$1")
      (value "CAT24C128")
      (footprint "eagle-import:SOIC8")
      (libsource (lib "eagle-import") (part "CAT24C128"))
    )
    (comp (ref "U$2")
      (value "DS1307SO8")
      (footprint "eagle-import:SO08")
      (libsource (lib "eagle-import") (part "DS1307SO8"))
    )
    (comp (ref "U1")
      (value "ATMEGA2560AU")
      (footprint "eagle-import:TQFP100")
      (libsource (lib "eagle-import") (part "ATMEGA2560AU"))
    )
    (comp (ref "D1")
      (value "1N4004")
      (footprint "eagle-import:DO41-10")
      (libsource (lib "eagle-import") (part "1N4004"))
    )
    (comp (ref "D2")
      (value "1N4004")
      (footprint "eagle-import:DO41-10")
      (libsource (lib "eagle-import") (part "1N4004"))
    )
    (comp (ref "D3")
      (value "1N4004")
      (footprint "eagle-import:DO41-10")
      (libsource (lib "eagle-import") (part "1N4004"))
    )
    (comp (ref "D4")
      (value "1N4004")
      (footprint "eagle-import:DO41-10")
      (libsource (lib "eagle-import") (part "1N4004"))
    )
    (comp (ref "D5")
      (value "1N4004")
      (footprint "eagle-import:DO41-10")
      (libsource (lib "eagle-import") (part "1N4004"))
    )
    (comp (ref "D6")
      (value "1N4004")
      (footprint "eagle-import:DO41-10")
      (libsource (lib "eagle-import") (part "1N4004"))
    )
    (comp (ref "D7")
      (value "1N4004")
      (footprint "eagle-import:DO41-10")
      (libsource (lib "eagle-import") (part "1N4004"))
    )
    (comp (ref "D8")
      (value "1N4004")
      (footprint "eagle-import:DO41-10")
      (libsource (lib "eagle-import") (part "1N4004"))
    )
    (comp (ref "D9")
      (value "1N4004")
      (footprint "eagle-import:DO41-10")
      (libsource (lib "eagle-import") (part "1N4004"))
    )
    (comp (ref "D10")
      (value "1N4004")
      (footprint "eagle-import:DO41-10")
      (libsource (lib "eagle-import") (part "1N4004"))
    )
    (comp (ref "D11")
      (value "1N4004")
      (footprint "eagle-import:DO41-10")
      (libsource (lib "eagle-import") (part "1N4004"))
    )
    (comp (ref "D12")
      (value "1N4004")
      (footprint "eagle-import:DO41-10")
      (libsource (lib "eagle-import") (part "1N4004"))
    )
    (comp (ref "D13")
      (value "1N4004")
      (footprint "eagle-import:DO41-10")
      (libsource (lib "eagle-import") (part "1N4004"))
    )
    (comp (ref "D14")
      (value "1N4004")
      (footprint "eagle-import:DO41-10")
      (libsource (lib "eagle-import") (part "1N4004"))
    )
    (comp (ref "D15")
      (value "1N4004")
      (footprint "eagle-import:DO41-10")
      (libsource (lib "eagle-import") (part "1N4004"))
    )
    (comp (ref "D16")
      (value "1N4004")
      (footprint "eagle-import:DO41-10")
      (libsource (lib "eagle-import") (part "1N4004"))
    )
    (comp (ref "D33")
      (value "LED1206")
      (footprint "eagle-import:LED-1206")
      (libsource (lib "eagle-import") (part "LED1206"))
    )
    (comp (ref "D34")
      (value "LED1206")
      (footprint "eagle-import:LED-1206")
      (libsource (lib "eagle-import") (part "LED1206"))
    )
    (comp (ref "D35")
      (value "LED1206")
      (footprint "eagle-import:LED-1206")
      (libsource (lib "eagle-import") (part "LED1206"))
    )
    (comp (ref "D36")
      (value "LED1206")
      (footprint "eagle-import:LED-1206")
      (libsource (lib "eagle-import") (part "LED1206"))
    )
    (comp (ref "D37")
      (value "LED1206")
      (footprint "eagle-import:LED-1206")
      (libsource (lib "eagle-import") (part "LED1206"))
    )
    (comp (ref "D38")
      (value "LED1206")
      (footprint "eagle-import:LED-1206")
      (libsource (lib "eagle-import") (part "LED1206"))
    )
    (comp (ref "D39")
      (value "LED1206")
      (footprint "eagle-import:LED-1206")
      (libsource (lib "eagle-import") (part "LED1206"))
    )
    (comp (ref "D40")
      (value "LED1206")
      (footprint "eagle-import:LED-1206")
      (libsource (lib "eagle-import") (part "LED1206"))
    )
    (comp (ref "D41")
      (value "LED1206")
      (footprint "eagle-import:LED-1206")
      (libsource (lib "eagle-import") (part "LED1206"))
    )
    (comp (ref "D42")
      (value "LED1206")
      (footprint "eagle-import:LED-1206")
      (libsource (lib "eagle-import") (part "LED1206"))
    )
    (comp (ref "D43")
      (value "LED1206")
      (footprint "eagle-import:LED-1206")
      (libsource (lib "eagle-import") (part "LED1206"))
    )
    (comp (ref "D44")
      (value "LED1206")
      (footprint "eagle-import:LED-1206")
      (libsource (lib "eagle-import") (part "LED1206"))
    )
    (comp (ref "D45")
      (value "LED1206")
      (footprint "eagle-import:LED-1206")
      (libsource (lib "eagle-import") (part "LED1206"))
    )
    (comp (ref "D46")
      (value "LED1206")
      (footprint "eagle-import:LED-1206")
      (libsource (lib "eagle-import") (part "LED1206"))
    )
    (comp (ref "D47")
      (value "LED1206")
      (footprint "eagle-import:LED-1206")
      (libsource (lib "eagle-import") (part "LED1206"))
    )
    (comp (ref "D48")
      (value "LED1206")
      (footprint "eagle-import:LED-1206")
      (libsource (lib "eagle-import") (part "LED1206"))
    )
    (comp (ref "K1")
      (value "G5LE")
      (footprint "eagle-import:G5LE")
      (libsource (lib "eagle-import") (part "G5LE"))
    )
    (comp (ref "K2")
      (value "G5LE")
      (footprint "eagle-import:G5LE")
      (libsource (lib "eagle-import") (part "G5LE"))
    )
    (comp (ref "K3")
      (value "G5LE")
      (footprint "eagle-import:G5LE")
      (libsource (lib "eagle-import") (part "G5LE"))
    )
    (comp (ref "K4")
      (value "G5LE")
      (footprint "eagle-import:G5LE")
      (libsource (lib "eagle-import") (part "G5LE"))
    )
    (comp (ref "K5")
      (value "G5LE")
      (footprint "eagle-import:G5LE")
      (libsource (lib "eagle-import") (part "G5LE"))
    )
    (comp (ref "K6")
      (value "G5LE")
      (footprint "eagle-import:G5LE")
      (libsource (lib "eagle-import") (part "G5LE"))
    )
    (comp (ref "K7")
      (value "G5LE")
      (footprint "eagle-import:G5LE")
      (libsource (lib "eagle-import") (part "G5LE"))
    )
    (comp (ref "K8")
      (value "G5LE")
      (footprint "eagle-import:G5LE")
      (libsource (lib "eagle-import") (part "G5LE"))
    )
    (comp (ref "K9")
      (value "G5LE")
      (footprint "eagle-import:G5LE")
      (libsource (lib "eagle-import") (part "G5LE"))
    )
    (comp (ref "K10")
      (value "G5LE")
      (footprint "eagle-import:G5LE")
      (libsource (lib "eagle-import") (part "G5LE"))
    )
    (comp (ref "K11")
      (value "G5LE")
      (footprint "eagle-import:G5LE")
      (libsource (lib "eagle-import") (part "G5LE"))
    )
    (comp (ref "K12")
      (value "G5LE")
      (footprint "eagle-import:G5LE")
      (libsource (lib "eagle-import") (part "G5LE"))
    )
    (comp (ref "K13")
      (value "G5LE")
      (footprint "eagle-import:G5LE")
      (libsource (lib "eagle-import") (part "G5LE"))
    )
    (comp (ref "K14")
      (value "G5LE")
      (footprint "eagle-import:G5LE")
      (libsource (lib "eagle-import") (part "G5LE"))
    )
    (comp (ref "K15")
      (value "G5LE")
      (footprint "eagle-import:G5LE")
      (libsource (lib "eagle-import") (part "G5LE"))
    )
    (comp (ref "K16")
      (value "G5LE")
      (footprint "eagle-import:G5LE")
      (libsource (lib "eagle-import") (part "G5LE"))
    )
    (comp (ref "OK1")
      (value "PC817")
      (footprint "eagle-import:DIL04")
      (fields (field (name "MPN") "PC817X4J000F"))
      (libsource (lib "eagle-import") (part "PC817"))
    )
    (comp (ref "OK2")
      (value "PC817")
      (footprint "eagle-import:DIL04")
      (fields (field (name "MPN") "PC817X4J000F"))
      (libsource (lib "eagle-import") (part "PC817"))
    )
    (comp (ref "OK3")
      (value "PC817")
      (footprint "eagle-import:DIL04")
      (fields (field (name "MPN") "PC817X4J000F"))
      (libsource (lib "eagle-import") (part "PC817"))
    )
    (comp (ref "OK4")
      (value "PC817")
      (footprint "eagle-import:DIL04")
      (fields (field (name "MPN") "PC817X4J000F"))
      (libsource (lib "eagle-import") (part "PC817"))
    )
    (comp (ref "OK5")
      (value "PC817")
      (footprint "eagle-import:DIL04")
      (fields (field (name "MPN") "PC817X4J000F"))
      (libsource (lib "eagle-import") (part "PC817"))
    )
    (comp (ref "OK6")
      (value "PC817")
      (footprint "eagle-import:DIL04")
      (fields (field (name "MPN") "PC817X4J000F"))
      (libsource (lib "eagle-import") (part "PC817"))
    )
    (comp (ref "OK7")
      (value "PC817")
      (footprint "eagle-import:DIL04")
      (fields (field (name "MPN") "PC817X4J000F"))
      (libsource (lib "eagle-import") (part "PC817"))
    )
    (comp (ref "OK8")
      (value "PC817")
      (footprint "eagle-import:DIL04")
      (fields (field (name "MPN") "PC817X4J000F"))
      (libsource (lib "eagle-import") (part "PC817"))
    )
    (comp (ref "OK17")
      (value "PC817")
      (footprint "eagle-import:DIL04")
      (fields (field (name "MPN") "PC817X4J000F"))
      (libsource (lib "eagle-import") (part "PC817"))
    )
    (comp (ref "OK18")
      (value "PC817")
      (footprint "eagle-import:DIL04")
      (fields (field (name "MPN") "PC817X4J000F"))
      (libsource (lib "eagle-import") (part "PC817"))
    )
    (comp (ref "OK19")
      (value "PC817")
      (footprint "eagle-import:DIL04")
      (fields (field (name "MPN") "PC817X4J000F"))
      (libsource (lib "eagle-import") (part "PC817"))
    )
    (comp (ref "OK20")
      (value "PC817")
      (footprint "eagle-import:DIL04")
      (fields (field (name "MPN") "PC817X4J000F"))
      (libsource (lib "eagle-import") (part "PC817"))
    )
    (comp (ref "OK21")
      (value "PC817")
      (footprint "eagle-import:DIL04")
      (fields (field (name "MPN") "PC817X4J000F"))
      (libsource (lib "eagle-import") (part "PC817"))
    )
    (comp (ref "OK22")
      (value "PC817")
      (footprint "eagle-import:DIL04")
      (fields (field (name "MPN") "PC817X4J000F"))
      (libsource (lib "eagle-import") (part "PC817"))
    )
    (comp (ref "OK23")
      (value "PC817")
      (footprint "eagle-import:DIL04")
      (fields (field (name "MPN") "PC817X4J000F"))
      (libsource (lib "eagle-import") (part "PC817"))
    )
    (comp (ref "OK24")
      (value "PC817")
      (footprint "eagle-import:DIL04")
      (fields (field (name "MPN") "PC817X4J000F"))
      (libsource (lib "eagle-import") (part "PC817"))
    )
    (comp (ref "R42")
      (value "1K")
      (footprint "eagle-import:R0805")
      (libsource (lib "eagle-import") (part "R-US_R0805"))
    )
    (comp (ref "R43")
      (value "1K")
      (footprint "eagle-import:R0805")
      (libsource (lib "eagle-import") (part "R-US_R0805"))
    )
    (comp (ref "R44")
      (value "1K")
      (footprint "eagle-import:R0805")
      (libsource (lib "eagle-import") (part "R-US_R0805"))
    )
    (comp (ref "R45")
      (value "1K")
      (footprint "eagle-import:R0805")
      (libsource (lib "eagle-import") (part "R-US_R0805"))
    )
    (comp (ref "R46")
      (value "1K")
      (footprint "eagle-import:R0805")
      (libsource (lib "eagle-import") (part "R-US_R0805"))
    )
    (comp (ref "R47")
      (value "1K")
      (footprint "eagle-import:R0805")
      (libsource (lib "eagle-import") (part "R-US_R0805"))
    )
    (comp (ref "R48")
      (value "1K")
      (footprint "eagle-import:R0805")
      (libsource (lib "eagle-import") (part "R-US_R0805"))
    )
    (comp (ref "R49")
      (value "1K")
      (footprint "eagle-import:R0805")
      (libsource (lib "eagle-import") (part "R-US_R0805"))
    )
    (comp (ref "R50")
      (value "1K")
      (footprint "eagle-import:R0805")
      (libsource (lib "eagle-import") (part "R-US_R0805"))
    )
    (comp (ref "R51")
      (value "1K")
      (footprint "eagle-import:R0805")
      (libsource (lib "eagle-import") (part "R-US_R0805"))
    )
    (comp (ref "R52")
      (value "1K")
      (footprint "eagle-import:R0805")
      (libsource (lib "eagle-import") (part "R-US_R0805"))
    )
    (comp (ref "R53")
      (value "1K")
      (footprint "eagle-import:R0805")
      (libsource (lib "eagle-import") (part "R-US_R0805"))
    )
    (comp (ref "R54")
      (value "1K")
      (footprint "eagle-import:R0805")
      (libsource (lib "eagle-import") (part "R-US_R0805"))
    )
    (comp (ref "R55")
      (value "1K")
      (footprint "eagle-import:R0805")
      (libsource (lib "eagle-import") (part "R-US_R0805"))
    )
    (comp (ref "R56")
      (value "1K")
      (footprint "eagle-import:R0805")
      (libsource (lib "eagle-import") (part "R-US_R0805"))
    )
    (comp (ref "R57")
      (value "1K")
      (footprint "eagle-import:R0805")
      (libsource (lib "eagle-import") (part "R-US_R0805"))
    )
    (comp (ref "X3")
      (value "MSTBA9")
      (footprint "eagle-import:MSTBA9")
      (fields (field (name "MF") "FARNELL") (field (name "MPN") "1757310"))
      (libsource (lib "eagle-import") (part "MSTBA9"))
    )
    (comp (ref "X4")
      (value "MSTBA9")
      (footprint "eagle-import:MSTBA9")
      (fields (field (name "MF") "FARNELL") (field (name "MPN") "1757310"))
      (libsource (lib "eagle-import") (part "MSTBA9"))
    )
    (comp (ref "C35")
      (value "0.047uF/50V")
      (footprint "eagle-import:C0805K")
      (libsource (lib "eagle-import") (part "C-USC0805K"))
    )
    (comp (ref "C36")
      (value "0.33uF/50V")
      (footprint "eagle-import:C0805K")
      (libsource (lib "eagle-import") (part "C-USC0805K"))
    )
    (comp (ref "C37")
      (value "0.33uF/50V")
      (footprint "eagle-import:C0805K")
      (libsource (lib "eagle-import") (part "C-USC0805K"))
    )
    (comp (ref "C38")
      (value "1uF/50V")
      (footprint "eagle-import:C0805K")
      (libsource (lib "eagle-import") (part "C-USC0805K"))
    )
    (comp (ref "C39")
      (value "0.1uF/50V")
      (footprint "eagle-import:C0805K")
      (libsource (lib "eagle-import") (part "C-USC0805K"))
    )
    (comp (ref "C42")
      (value "0.1uF/50V")
      (footprint "eagle-import:C0805K")
      (libsource (lib "eagle-import") (part "C-USC0805K"))
    )
    (comp (ref "H1")
      (value "MOUNT-HOLE3.2")
      (footprint "eagle-import:3,2")
      (libsource (lib "eagle-import") (part "MOUNT-HOLE3.2"))
    )
    (comp (ref "H2")
      (value "MOUNT-HOLE3.2")
      (footprint "eagle-import:3,2")
      (libsource (lib "eagle-import") (part "MOUNT-HOLE3.2"))
    )
    (comp (ref "H3")
      (value "MOUNT-HOLE3.2")
      (footprint "eagle-import:3,2")
      (libsource (lib "eagle-import") (part "MOUNT-HOLE3.2"))
    )
    (comp (ref "H4")
      (value "MOUNT-HOLE3.2")
      (footprint "eagle-import:3,2")
      (libsource (lib "eagle-import") (part "MOUNT-HOLE3.2"))
    )
    (comp (ref "H5")
      (value "MOUNT-HOLE3.2")
      (footprint "eagle-import:3,2")
      (libsource (lib "eagle-import") (part "MOUNT-HOLE3.2"))
    )
    (comp (ref "H6")
      (value "MOUNT-HOLE3.2")
      (footprint "eagle-import:3,2")
      (libsource (lib "eagle-import") (part "MOUNT-HOLE3.2"))
    )
    (comp (ref "H7")
      (value "MOUNT-HOLE3.2")
      (footprint "eagle-import:3,2")
      (libsource (lib "eagle-import") (part "MOUNT-HOLE3.2"))
    )
    (comp (ref "H8")
      (value "MOUNT-HOLE3.2")
      (footprint "eagle-import:3,2")
      (libsource (lib "eagle-import") (part "MOUNT-HOLE3.2"))
    )
    (comp (ref "R90")
      (value "R-US_R0805")
      (footprint "eagle-import:R0805")
      (libsource (lib "eagle-import") (part "R-US_R0805"))
    )
    (comp (ref "R91")
      (value "R-US_R0805")
      (footprint "eagle-import:R0805")
      (libsource (lib "eagle-import") (part "R-US_R0805"))
    )
    (comp (ref "U$6")
      (value "MAX13223")
      (footprint "eagle-import:TSSOP20")
      (libsource (lib "eagle-import") (part "MAX13223"))
    )
    (comp (ref "U$8")
      (value "RS485SOIC")
      (footprint "eagle-import:SO08")
      (libsource (lib "eagle-import") (part "RS485SOIC"))
    )
    (comp (ref "X2")
      (value "MKDSN1,5/3-5,08")
      (footprint "eagle-import:MKDSN1,5_3-5,08")
      (fields (field (name "MPN") "SMKDSN1,5/3-5,08"))
      (libsource (lib "eagle-import") (part "MKDSN1,5/3-5,08"))
    )
    (comp (ref "X7")
      (value "F09.590S")
      (footprint "eagle-import:177-009-FEMALE")
      (libsource (lib "eagle-import") (part "F09?S.590"))
    )
  )
  (nets
    (net (code "1") (name "+5V") (class "Default")
      (node (ref "C1") (pin "1") (pinfunction "1_1") (pintype "passive"))
      (node (ref "C12") (pin "1") (pinfunction "1_1") (pintype "passive"))
      (node (ref "C13") (pin "+") (pinfunction "+_+") (pintype "passive"))
      (node (ref "C14") (pin "1") (pinfunction "1_1") (pintype "passive"))
      (node (ref "C15") (pin "1") (pinfunction "1_1") (pintype "passive"))
      (node (ref "C16") (pin "1") (pinfunction "1_1") (pintype "passive"))
      (node (ref "C17") (pin "1") (pinfunction "1_1") (pintype "passive"))
      (node (ref "C18") (pin "1") (pinfunction "1_1") (pintype "passive"))
      (node (ref "C2") (pin "1") (pinfunction "1_1") (pintype "passive"))
      (node (ref "C3") (pin "1") (pinfunction "1_1") (pintype "passive"))
      (node (ref "C33") (pin "1") (pinfunction "1_1") (pintype "passive"))
      (node (ref "C34") (pin "1") (pinfunction "1_1") (pintype "passive"))
      (node (ref "C39") (pin "1") (pinfunction "1_1") (pintype "passive"))
      (node (ref "C40") (pin "+") (pinfunction "+_+") (pintype "passive"))
      (node (ref "C41") (pin "1") (pinfunction "1_1") (pintype "passive"))
      (node (ref "C42") (pin "1") (pinfunction "1_1") (pintype "passive"))
      (node (ref "C43") (pin "1") (pinfunction "1_1") (pintype "passive"))
      (node (ref "C44") (pin "1") (pinfunction "1_1") (pintype "passive"))
      (node (ref "C6") (pin "1") (pinfunction "1_1") (pintype "passive"))
      (node (ref "C7") (pin "1") (pinfunction "1_1") (pintype "passive"))
      (node (ref "C8") (pin "1") (pinfunction "1_1") (pintype "passive"))
      (node (ref "C9") (pin "1") (pinfunction "1_1") (pintype "passive"))
      (node (ref "IC1") (pin "20") (pinfunction "VCC_20") (pintype "power_in"))
      (node (ref "IC2") (pin "20") (pinfunction "VCC_20") (pintype "power_in"))
      (node (ref "IC3") (pin "20") (pinfunction "VCC_20") (pintype "power_in"))
      (node (ref "IC4") (pin "20") (pinfunction "VCC_20") (pintype "power_in"))
      (node (ref "IC5") (pin "3") (pinfunction "VO_3") (pintype "passive"))
      (node (ref "IC6") (pin "2") (pinfunction "+VIN_2") (pintype "input"))
      (node (ref "J1") (pin "2") (pinfunction "VCC_2") (pintype "power_in"))
      (node (ref "K33") (pin "33") (pinfunction "33_33") (pintype "passive"))
      (node (ref "K33") (pin "34") (pinfunction "34_34") (pintype "passive"))
      (node (ref "K35") (pin "17") (pinfunction "17_17") (pintype "passive"))
      (node (ref "K35") (pin "18") (pinfunction "18_18") (pintype "passive"))
      (node (ref "R3") (pin "2") (pinfunction "2_2") (pintype "passive"))
      (node (ref "R4") (pin "1") (pinfunction "1_1") (pintype "passive"))
      (node (ref "R5") (pin "1") (pinfunction "1_1") (pintype "passive"))
      (node (ref "R6") (pin "1") (pinfunction "1_1") (pintype "passive"))
      (node (ref "R74") (pin "1") (pinfunction "1_1") (pintype "passive"))
      (node (ref "R76") (pin "1") (pinfunction "1_1") (pintype "passive"))
      (node (ref "R77") (pin "1") (pinfunction "1_1") (pintype "passive"))
      (node (ref "R8") (pin "1") (pinfunction "1_1") (pintype "passive"))
      (node (ref "R86") (pin "1") (pinfunction "1_1") (pintype "passive"))
      (node (ref "R87") (pin "1") (pinfunction "1_1") (pintype "passive"))
      (node (ref "R89") (pin "1") (pinfunction "1_1") (pintype "passive"))
      (node (ref "R91") (pin "1") (pinfunction "1_1") (pintype "passive"))
      (node (ref "R93") (pin "1") (pinfunction "1_1") (pintype "passive"))
      (node (ref "R95") (pin "1") (pinfunction "1_1") (pintype "passive"))
      (node (ref "R97") (pin "1") (pinfunction "1_1") (pintype "passive"))
      (node (ref "R99") (pin "1") (pinfunction "1_1") (pintype "passive"))
      (node (ref "TP1") (pin "TP") (pinfunction "TP_TP") (pintype "input"))
      (node (ref "U$1") (pin "8") (pinfunction "VCC_8") (pintype "power_in"))
      (node (ref "U$2") (pin "8") (pinfunction "VCC_8") (pintype "bidirectional"))
      (node (ref "U$3") (pin "19") (pinfunction "VCC_19") (pintype "power_in"))
      (node (ref "U$4") (pin "15") (pinfunction "VDD_15") (pintype "power_in"))
      (node (ref "U$5") (pin "15") (pinfunction "VDD_15") (pintype "power_in"))
      (node (ref "U$6") (pin "19") (pinfunction "VCC_19") (pintype "bidirectional"))
      (node (ref "U$6") (pin "20") (pinfunction "FORCEOFF_20") (pintype "bidirectional"))
      (node (ref "U$8") (pin "8") (pinfunction "VCC_8") (pintype "bidirectional"))
      (node (ref "U1") (pin "10") (pinfunction "VCC_10") (pintype "power_in"))
      (node (ref "U1") (pin "100") (pinfunction "AVCC_100") (pintype "power_in"))
      (node (ref "U1") (pin "31") (pinfunction "VCC1_31") (pintype "power_in"))
      (node (ref "U1") (pin "61") (pinfunction "VCC2_61") (pintype "power_in"))
      (node (ref "U1") (pin "80") (pinfunction "VCC3_80") (pintype "power_in"))
    )
    (net (code "2") (name "+12V") (class "Default")
      (node (ref "B1") (pin "+") (pinfunction "+_+") (pintype "passive"))
      (node (ref "C10") (pin "+") (pinfunction "+_+") (pintype "passive"))
      (node (ref "C11") (pin "1") (pinfunction "1_1") (pintype "passive"))
      (node (ref "C45") (pin "+") (pinfunction "+_+") (pintype "passive"))
      (node (ref "D1") (pin "C") (pinfunction "C_C") (pintype "passive"))
      (node (ref "D10") (pin "C") (pinfunction "C_C") (pintype "passive"))
      (node (ref "D11") (pin "C") (pinfunction "C_C") (pintype "passive"))
      (node (ref "D12") (pin "C") (pinfunction "C_C") (pintype "passive"))
      (node (ref "D13") (pin "C") (pinfunction "C_C") (pintype "passive"))
      (node (ref "D14") (pin "C") (pinfunction "C_C") (pintype "passive"))
      (node (ref "D15") (pin "C") (pinfunction "C_C") (pintype "passive"))
      (node (ref "D16") (pin "C") (pinfunction "C_C") (pintype "passive"))
      (node (ref "D17") (pin "C") (pinfunction "C_C") (pintype "passive"))
      (node (ref "D18") (pin "C") (pinfunction "C_C") (pintype "passive"))
      (node (ref "D19") (pin "C") (pinfunction "C_C") (pintype "passive"))
      (node (ref "D2") (pin "C") (pinfunction "C_C") (pintype "passive"))
      (node (ref "D20") (pin "C") (pinfunction "C_C") (pintype "passive"))
      (node (ref "D21") (pin "C") (pinfunction "C_C") (pintype "passive"))
      (node (ref "D22") (pin "C") (pinfunction "C_C") (pintype "passive"))
      (node (ref "D23") (pin "C") (pinfunction "C_C") (pintype "passive"))
      (node (ref "D24") (pin "C") (pinfunction "C_C") (pintype "passive"))
      (node (ref "D25") (pin "C") (pinfunction "C_C") (pintype "passive"))
      (node (ref "D26") (pin "C") (pinfunction "C_C") (pintype "passive"))
      (node (ref "D27") (pin "C") (pinfunction "C_C") (pintype "passive"))
      (node (ref "D28") (pin "C") (pinfunction "C_C") (pintype "passive"))
      (node (ref "D29") (pin "C") (pinfunction "C_C") (pintype "passive"))
      (node (ref "D3") (pin "C") (pinfunction "C_C") (pintype "passive"))
      (node (ref "D30") (pin "C") (pinfunction "C_C") (pintype "passive"))
      (node (ref "D31") (pin "C") (pinfunction "C_C") (pintype "passive"))
      (node (ref "D32") (pin "C") (pinfunction "C_C") (pintype "passive"))
      (node (ref "D4") (pin "C") (pinfunction "C_C") (pintype "passive"))
      (node (ref "D5") (pin "C") (pinfunction "C_C") (pintype "passive"))
      (node (ref "D6") (pin "C") (pinfunction "C_C") (pintype "passive"))
      (node (ref "D7") (pin "C") (pinfunction "C_C") (pintype "passive"))
      (node (ref "D8") (pin "C") (pinfunction "C_C") (pintype "passive"))
      (node (ref "D9") (pin "C") (pinfunction "C_C") (pintype "passive"))
      (node (ref "IC5") (pin "1") (pinfunction "VI_1") (pintype "input"))
      (node (ref "K1") (pin "1") (pinfunction "1_1") (pintype "passive"))
      (node (ref "K10") (pin "1") (pinfunction "1_1") (pintype "passive"))
      (node (ref "K11") (pin "1") (pinfunction "1_1") (pintype "passive"))
      (node (ref "K12") (pin "1") (pinfunction "1_1") (pintype "passive"))
      (node (ref "K13") (pin "1") (pinfunction "1_1") (pintype "passive"))
      (node (ref "K14") (pin "1") (pinfunction "1_1") (pintype "passive"))
      (node (ref "K15") (pin "1") (pinfunction "1_1") (pintype "passive"))
      (node (ref "K16") (pin "1") (pinfunction "1_1") (pintype "passive"))
      (node (ref "K17") (pin "1") (pinfunction "1_1") (pintype "passive"))
      (node (ref "K18") (pin "1") (pinfunction "1_1") (pintype "passive"))
      (node (ref "K19") (pin "1") (pinfunction "1_1") (pintype "passive"))
      (node (ref "K2") (pin "1") (pinfunction "1_1") (pintype "passive"))
      (node (ref "K20") (pin "1") (pinfunction "1_1") (pintype "passive"))
      (node (ref "K21") (pin "1") (pinfunction "1_1") (pintype "passive"))
      (node (ref "K22") (pin "1") (pinfunction "1_1") (pintype "passive"))
      (node (ref "K23") (pin "1") (pinfunction "1_1") (pintype "passive"))
      (node (ref "K24") (pin "1") (pinfunction "1_1") (pintype "passive"))
      (node (ref "K25") (pin "1") (pinfunction "1_1") (pintype "passive"))
      (node (ref "K26") (pin "1") (pinfunction "1_1") (pintype "passive"))
      (node (ref "K27") (pin "1") (pinfunction "1_1") (pintype "passive"))
      (node (ref "K28") (pin "1") (pinfunction "1_1") (pintype "passive"))
      (node (ref "K29") (pin "1") (pinfunction "1_1") (pintype "passive"))
      (node (ref "K3") (pin "1") (pinfunction "1_1") (pintype "passive"))
      (node (ref "K30") (pin "1") (pinfunction "1_1") (pintype "passive"))
      (node (ref "K31") (pin "1") (pinfunction "1_1") (pintype "passive"))
      (node (ref "K32") (pin "1") (pinfunction "1_1") (pintype "passive"))
      (node (ref "K33") (pin "37") (pinfunction "37_37") (pintype "passive"))
      (node (ref "K33") (pin "38") (pinfunction "38_38") (pintype "passive"))
      (node (ref "K4") (pin "1") (pinfunction "1_1") (pintype "passive"))
      (node (ref "K5") (pin "1") (pinfunction "1_1") (pintype "passive"))
      (node (ref "K6") (pin "1") (pinfunction "1_1") (pintype "passive"))
      (node (ref "K7") (pin "1") (pinfunction "1_1") (pintype "passive"))
      (node (ref "K8") (pin "1") (pinfunction "1_1") (pintype "passive"))
      (node (ref "K9") (pin "1") (pinfunction "1_1") (pintype "passive"))
      (node (ref "R2") (pin "1") (pinfunction "1_1") (pintype "passive"))
      (node (ref "R42") (pin "2") (pinfunction "2_2") (pintype "passive"))
      (node (ref "R43") (pin "2") (pinfunction "2_2") (pintype "passive"))
      (node (ref "R44") (pin "2") (pinfunction "2_2") (pintype "passive"))
      (node (ref "R45") (pin "2") (pinfunction "2_2") (pintype "passive"))
      (node (ref "R46") (pin "2") (pinfunction "2_2") (pintype "passive"))
      (node (ref "R47") (pin "2") (pinfunction "2_2") (pintype "passive"))
      (node (ref "R48") (pin "2") (pinfunction "2_2") (pintype "passive"))
      (node (ref "R49") (pin "2") (pinfunction "2_2") (pintype "passive"))
      (node (ref "R50") (pin "2") (pinfunction "2_2") (pintype "passive"))
      (node (ref "R51") (pin "2") (pinfunction "2_2") (pintype "passive"))
      (node (ref "R52") (pin "2") (pinfunction "2_2") (pintype "passive"))
      (node (ref "R53") (pin "2") (pinfunction "2_2") (pintype "passive"))
      (node (ref "R54") (pin "2") (pinfunction "2_2") (pintype "passive"))
      (node (ref "R55") (pin "2") (pinfunction "2_2") (pintype "passive"))
      (node (ref "R56") (pin "2") (pinfunction "2_2") (pintype "passive"))
      (node (ref "R57") (pin "2") (pinfunction "2_2") (pintype "passive"))
      (node (ref "R58") (pin "2") (pinfunction "2_2") (pintype "passive"))
      (node (ref "R59") (pin "2") (pinfunction "2_2") (pintype "passive"))
      (node (ref "R60") (pin "2") (pinfunction "2_2") (pintype "passive"))
      (node (ref "R61") (pin "2") (pinfunction "2_2") (pintype "passive"))
      (node (ref "R62") (pin "2") (pinfunction "2_2") (pintype "passive"))
      (node (ref "R63") (pin "2") (pinfunction "2_2") (pintype "passive"))
      (node (ref "R64") (pin "2") (pinfunction "2_2") (pintype "passive"))
      (node (ref "R65") (pin "2") (pinfunction "2_2") (pintype "passive"))
      (node (ref "R66") (pin "2") (pinfunction "2_2") (pintype "passive"))
      (node (ref "R67") (pin "2") (pinfunction "2_2") (pintype "passive"))
      (node (ref "R68") (pin "2") (pinfunction "2_2") (pintype "passive"))
      (node (ref "R69") (pin "2") (pinfunction "2_2") (pintype "passive"))
      (node (ref "R7") (pin "2") (pinfunction "2_2") (pintype "passive"))
      (node (ref "R70") (pin "2") (pinfunction "2_2") (pintype "passive"))
      (node (ref "R71") (pin "2") (pinfunction "2_2") (pintype "passive"))
      (node (ref "R72") (pin "2") (pinfunction "2_2") (pintype "passive"))
      (node (ref "R73") (pin "2") (pinfunction "2_2") (pintype "passive"))
      (node (ref "R75") (pin "2") (pinfunction "2_2") (pintype "passive"))
      (node (ref "R88") (pin "2") (pinfunction "2_2") (pintype "passive"))
      (node (ref "R9") (pin "2") (pinfunction "2_2") (pintype "passive"))
      (node (ref "R92") (pin "2") (pinfunction "2_2") (pintype "passive"))
      (node (ref "R94") (pin "2") (pinfunction "2_2") (pintype "passive"))
      (node (ref "R96") (pin "2") (pinfunction "2_2") (pintype "passive"))
      (node (ref "R98") (pin "2") (pinfunction "2_2") (pintype "passive"))
    )
    (net (code "3") (name "A") (class "Default")
      (node (ref "U$8") (pin "6") (pinfunction "A_6") (pintype "bidirectional"))
      (node (ref "X2") (pin "1") (pinfunction "KL_1") (pintype "passive"))
    )
    (net (code "4") (name "A0") (class "Default")
      (node (ref "U$1") (pin "1") (pinfunction "A0_1") (pintype "input"))
      (node (ref "U1") (pin "47") (pinfunction "(ICP1)PD4_47") (pintype "bidirectional"))
    )
    (net (code "5") (name "A1") (class "Default")
      (node (ref "U$1") (pin "2") (pinfunction "A1_2") (pintype "input"))
      (node (ref "U1") (pin "48") (pinfunction "(XCK1)PD5_48") (pintype "bidirectional"))
    )
    (net (code "6") (name "A2") (class "Default")
      (node (ref "U$1") (pin "3") (pinfunction "A2_3") (pintype "input"))
      (node (ref "U1") (pin "49") (pinfunction "(T1)PD6_49") (pintype "bidirectional"))
    )
    (net (code "7") (name "AD0") (class "Default")
      (node (ref "IC1") (pin "3") (pinfunction "1D_3") (pintype "input"))
      (node (ref "IC2") (pin "3") (pinfunction "1D_3") (pintype "input"))
      (node (ref "IC3") (pin "3") (pinfunction "1D_3") (pintype "input"))
      (node (ref "IC4") (pin "3") (pinfunction "1D_3") (pintype "input"))
      (node (ref "U1") (pin "78") (pinfunction "(AD0)PA0_78") (pintype "bidirectional"))
    )
    (net (code "8") (name "AD1") (class "Default")
      (node (ref "IC1") (pin "4") (pinfunction "2D_4") (pintype "input"))
      (node (ref "IC2") (pin "4") (pinfunction "2D_4") (pintype "input"))
      (node (ref "IC3") (pin "4") (pinfunction "2D_4") (pintype "input"))
      (node (ref "IC4") (pin "4") (pinfunction "2D_4") (pintype "input"))
      (node (ref "U1") (pin "77") (pinfunction "(AD1)PA1_77") (pintype "bidirectional"))
    )
    (net (code "9") (name "AD2") (class "Default")
      (node (ref "IC1") (pin "7") (pinfunction "3D_7") (pintype "input"))
      (node (ref "IC2") (pin "7") (pinfunction "3D_7") (pintype "input"))
      (node (ref "IC3") (pin "7") (pinfunction "3D_7") (pintype "input"))
      (node (ref "IC4") (pin "7") (pinfunction "3D_7") (pintype "input"))
      (node (ref "U1") (pin "76") (pinfunction "(AD2)PA2_76") (pintype "bidirectional"))
    )
    (net (code "10") (name "AD3") (class "Default")
      (node (ref "IC1") (pin "8") (pinfunction "4D_8") (pintype "input"))
      (node (ref "IC2") (pin "8") (pinfunction "4D_8") (pintype "input"))
      (node (ref "IC3") (pin "8") (pinfunction "4D_8") (pintype "input"))
      (node (ref "IC4") (pin "8") (pinfunction "4D_8") (pintype "input"))
      (node (ref "U1") (pin "75") (pinfunction "(AD3)PA3_75") (pintype "bidirectional"))
    )
    (net (code "11") (name "AD4") (class "Default")
      (node (ref "IC1") (pin "13") (pinfunction "5D_13") (pintype "input"))
      (node (ref "IC2") (pin "13") (pinfunction "5D_13") (pintype "input"))
      (node (ref "IC3") (pin "13") (pinfunction "5D_13") (pintype "input"))
      (node (ref "IC4") (pin "13") (pinfunction "5D_13") (pintype "input"))
      (node (ref "U1") (pin "74") (pinfunction "(AD4)PA4_74") (pintype "bidirectional"))
    )
    (net (code "12") (name "AD5") (class "Default")
      (node (ref "IC1") (pin "14") (pinfunction "6D_14") (pintype "input"))
      (node (ref "IC2") (pin "14") (pinfunction "6D_14") (pintype "input"))
      (node (ref "IC3") (pin "14") (pinfunction "6D_14") (pintype "input"))
      (node (ref "IC4") (pin "14") (pinfunction "6D_14") (pintype "input"))
      (node (ref "U1") (pin "73") (pinfunction "(AD5)PA5_73") (pintype "bidirectional"))
    )
    (net (code "13") (name "AD6") (class "Default")
      (node (ref "IC1") (pin "17") (pinfunction "7D_17") (pintype "input"))
      (node (ref "IC2") (pin "17") (pinfunction "7D_17") (pintype "input"))
      (node (ref "IC3") (pin "17") (pinfunction "7D_17") (pintype "input"))
      (node (ref "IC4") (pin "17") (pinfunction "7D_17") (pintype "input"))
      (node (ref "U1") (pin "72") (pinfunction "(AD6)PA6_72") (pintype "bidirectional"))
    )
    (net (code "14") (name "AD7") (class "Default")
      (node (ref "IC1") (pin "18") (pinfunction "8D_18") (pintype "input"))
      (node (ref "IC2") (pin "18") (pinfunction "8D_18") (pintype "input"))
      (node (ref "IC3") (pin "18") (pinfunction "8D_18") (pintype "input"))
      (node (ref "IC4") (pin "18") (pinfunction "8D_18") (pintype "input"))
      (node (ref "U1") (pin "71") (pinfunction "(AD7)PA7_71") (pintype "bidirectional"))
    )
    (net (code "15") (name "AD8") (class "Default")
      (node (ref "IC1") (pin "11") (pinfunction "ENC_11") (pintype "input"))
      (node (ref "U1") (pin "53") (pinfunction "(A8)PC0_53") (pintype "bidirectional"))
    )
    (net (code "16") (name "AD9") (class "Default")
      (node (ref "IC2") (pin "11") (pinfunction "ENC_11") (pintype "input"))
      (node (ref "U1") (pin "54") (pinfunction "(A9)PC1_54") (pintype "bidirectional"))
    )
    (net (code "17") (name "AD10") (class "Default")
      (node (ref "IC3") (pin "11") (pinfunction "ENC_11") (pintype "input"))
      (node (ref "U1") (pin "55") (pinfunction "(A10)PC2_55") (pintype "bidirectional"))
    )
    (net (code "18") (name "AD11") (class "Default")
      (node (ref "IC4") (pin "11") (pinfunction "ENC_11") (pintype "input"))
      (node (ref "U1") (pin "56") (pinfunction "(A11)PC3_56") (pintype "bidirectional"))
    )
    (net (code "19") (name "AD12") (class "Default")
      (node (ref "IC1") (pin "1") (pinfunction "OC_1") (pintype "input"))
      (node (ref "U1") (pin "57") (pinfunction "(A12)PC4_57") (pintype "bidirectional"))
    )
    (net (code "20") (name "AD13") (class "Default")
      (node (ref "IC2") (pin "1") (pinfunction "OC_1") (pintype "input"))
      (node (ref "U1") (pin "58") (pinfunction "(A13)PC5_58") (pintype "bidirectional"))
    )
    (net (code "21") (name "AD14") (class "Default")
      (node (ref "IC3") (pin "1") (pinfunction "OC_1") (pintype "input"))
      (node (ref "U1") (pin "59") (pinfunction "(A14)PC6_59") (pintype "bidirectional"))
    )
    (net (code "22") (name "AD15") (class "Default")
      (node (ref "IC4") (pin "1") (pinfunction "OC_1") (pintype "input"))
      (node (ref "U1") (pin "60") (pinfunction "(A15)PC7_60") (pintype "bidirectional"))
    )
    (net (code "23") (name "B") (class "Default")
      (node (ref "U$8") (pin "7") (pinfunction "B_7") (pintype "bidirectional"))
      (node (ref "X2") (pin "2") (pinfunction "KL_2") (pintype "passive"))
    )
    (net (code "24") (name "BUZZ") (class "Default")
      (node (ref "R1") (pin "2") (pinfunction "2_2") (pintype "passive"))
      (node (ref "U1") (pin "79") (pinfunction "PJ7_79") (pintype "bidirectional"))
    )
    (net (code "25") (name "COL1") (class "Default")
      (node (ref "K34") (pin "7") (pinfunction "7_7") (pintype "passive"))
      (node (ref "U1") (pin "63") (pinfunction "PJ0(RXD3/PCINT9)_63") (pintype "bidirectional"))
    )
    (net (code "26") (name "COL2") (class "Default")
      (node (ref "K34") (pin "8") (pinfunction "8_8") (pintype "passive"))
      (node (ref "U1") (pin "64") (pinfunction "PJ1(TXD3/PCINT10)_64") (pintype "bidirectional"))
    )
    (net (code "27") (name "COL3") (class "Default")
      (node (ref "K34") (pin "9") (pinfunction "9_9") (pintype "passive"))
      (node (ref "U1") (pin "65") (pinfunction "PJ2(XCK3/PCINT11)_65") (pintype "bidirectional"))
    )
    (net (code "28") (name "COL4") (class "Default")
      (node (ref "K34") (pin "10") (pinfunction "10_10") (pintype "passive"))
      (node (ref "U1") (pin "66") (pinfunction "PJ3(PCINT12)_66") (pintype "bidirectional"))
    )
    (net (code "29") (name "COL5") (class "Default")
      (node (ref "K34") (pin "11") (pinfunction "11_11") (pintype "passive"))
      (node (ref "U1") (pin "67") (pinfunction "PJ4(PCINT13)_67") (pintype "bidirectional"))
    )
    (net (code "30") (name "COL6") (class "Default")
      (node (ref "K34") (pin "12") (pinfunction "12_12") (pintype "passive"))
      (node (ref "U1") (pin "68") (pinfunction "PJ5(PCINT14)_68") (pintype "bidirectional"))
    )
    (net (code "31") (name "COL7") (class "Default")
      (node (ref "K34") (pin "13") (pinfunction "13_13") (pintype "passive"))
      (node (ref "U1") (pin "69") (pinfunction "PJ6(PCINT15)_69") (pintype "bidirectional"))
    )
    (net (code "32") (name "COM1-8") (class "Default")
      (node (ref "K1") (pin "P") (pinfunction "P_P") (pintype "passive"))
      (node (ref "K2") (pin "P") (pinfunction "P_P") (pintype "passive"))
      (node (ref "K3") (pin "P") (pinfunction "P_P") (pintype "passive"))
      (node (ref "K4") (pin "P") (pinfunction "P_P") (pintype "passive"))
      (node (ref "K5") (pin "P") (pinfunction "P_P") (pintype "passive"))
      (node (ref "K6") (pin "P") (pinfunction "P_P") (pintype "passive"))
      (node (ref "K7") (pin "P") (pinfunction "P_P") (pintype "passive"))
      (node (ref "K8") (pin "P") (pinfunction "P_P") (pintype "passive"))
      (node (ref "X3") (pin "1") (pinfunction "1_1") (pintype "passive"))
    )
    (net (code "33") (name "COM9-16") (class "Default")
      (node (ref "K10") (pin "P") (pinfunction "P_P") (pintype "passive"))
      (node (ref "K11") (pin "P") (pinfunction "P_P") (pintype "passive"))
      (node (ref "K12") (pin "P") (pinfunction "P_P") (pintype "passive"))
      (node (ref "K13") (pin "P") (pinfunction "P_P") (pintype "passive"))
      (node (ref "K14") (pin "P") (pinfunction "P_P") (pintype "passive"))
      (node (ref "K15") (pin "P") (pinfunction "P_P") (pintype "passive"))
      (node (ref "K16") (pin "P") (pinfunction "P_P") (pintype "passive"))
      (node (ref "K9") (pin "P") (pinfunction "P_P") (pintype "passive"))
      (node (ref "X4") (pin "1") (pinfunction "1_1") (pintype "passive"))
    )
    (net (code "34") (name "COM17-24") (class "Default")
      (node (ref "K17") (pin "P") (pinfunction "P_P") (pintype "passive"))
      (node (ref "K18") (pin "P") (pinfunction "P_P") (pintype "passive"))
      (node (ref "K19") (pin "P") (pinfunction "P_P") (pintype "passive"))
      (node (ref "K20") (pin "P") (pinfunction "P_P") (pintype "passive"))
      (node (ref "K21") (pin "P") (pinfunction "P_P") (pintype "passive"))
      (node (ref "K22") (pin "P") (pinfunction "P_P") (pintype "passive"))
      (node (ref "K23") (pin "P") (pinfunction "P_P") (pintype "passive"))
      (node (ref "K24") (pin "P") (pinfunction "P_P") (pintype "passive"))
      (node (ref "X5") (pin "1") (pinfunction "1_1") (pintype "passive"))
    )
    (net (code "35") (name "COM25-32") (class "Default")
      (node (ref "K25") (pin "P") (pinfunction "P_P") (pintype "passive"))
      (node (ref "K26") (pin "P") (pinfunction "P_P") (pintype "passive"))
      (node (ref "K27") (pin "P") (pinfunction "P_P") (pintype "passive"))
      (node (ref "K28") (pin "P") (pinfunction "P_P") (pintype "passive"))
      (node (ref "K29") (pin "P") (pinfunction "P_P") (pintype "passive"))
      (node (ref "K30") (pin "P") (pinfunction "P_P") (pintype "passive"))
      (node (ref "K31") (pin "P") (pinfunction "P_P") (pintype "passive"))
      (node (ref "K32") (pin "P") (pinfunction "P_P") (pintype "passive"))
      (node (ref "X6") (pin "1") (pinfunction "1_1") (pintype "passive"))
    )
    (net (code "36") (name "CON1") (class "Default")
      (node (ref "OK34") (pin "2") (pinfunction "C_2") (pintype "passive"))
      (node (ref "X1") (pin "2") (pinfunction "1_2") (pintype "passive"))
    )
    (net (code "37") (name "CON2") (class "Default")
      (node (ref "OK35") (pin "2") (pinfunction "C_2") (pintype "passive"))
      (node (ref "X1") (pin "3") (pinfunction "1_3") (pintype "passive"))
    )
    (net (code "38") (name "CON3") (class "Default")
      (node (ref "OK36") (pin "2") (pinfunction "C_2") (pintype "passive"))
      (node (ref "X1") (pin "4") (pinfunction "1_4") (pintype "passive"))
    )
    (net (code "39") (name "CON4") (class "Default")
      (node (ref "OK37") (pin "2") (pinfunction "C_2") (pintype "passive"))
      (node (ref "X1") (pin "5") (pinfunction "1_5") (pintype "passive"))
    )
    (net (code "40") (name "CON5") (class "Default")
      (node (ref "OK38") (pin "2") (pinfunction "C_2") (pintype "passive"))
      (node (ref "X1") (pin "6") (pinfunction "1_6") (pintype "passive"))
    )
    (net (code "41") (name "CON6") (class "Default")
      (node (ref "OK39") (pin "2") (pinfunction "C_2") (pintype "passive"))
      (node (ref "X1") (pin "7") (pinfunction "1_7") (pintype "passive"))
    )
    (net (code "42") (name "CON7") (class "Default")
      (node (ref "OK40") (pin "2") (pinfunction "C_2") (pintype "passive"))
      (node (ref "X1") (pin "8") (pinfunction "1_8") (pintype "passive"))
    )
    (net (code "43") (name "CON8") (class "Default")
      (node (ref "OK41") (pin "2") (pinfunction "C_2") (pintype "passive"))
      (node (ref "X1") (pin "9") (pinfunction "1_9") (pintype "passive"))
    )
    (net (code "44") (name "DB4") (class "Default")
      (node (ref "K34") (pin "17") (pinfunction "17_17") (pintype "passive"))
      (node (ref "U1") (pin "70") (pinfunction "(ALE)PG2_70") (pintype "bidirectional"))
    )
    (net (code "45") (name "DB5") (class "Default")
      (node (ref "K34") (pin "18") (pinfunction "18_18") (pintype "passive"))
      (node (ref "U1") (pin "28") (pinfunction "(TOSC2)PG3_28") (pintype "bidirectional"))
    )
    (net (code "46") (name "DB6") (class "Default")
      (node (ref "K34") (pin "19") (pinfunction "19_19") (pintype "passive"))
      (node (ref "U1") (pin "29") (pinfunction "(TOSC1)PG4_29") (pintype "bidirectional"))
    )
    (net (code "47") (name "DB7") (class "Default")
      (node (ref "K34") (pin "20") (pinfunction "20_20") (pintype "passive"))
      (node (ref "U1") (pin "1") (pinfunction "(OC0B)PG5_1") (pintype "bidirectional"))
    )
    (net (code "48") (name "DIG0") (class "Default")
      (node (ref "K35") (pin "5") (pinfunction "5_5") (pintype "passive"))
      (node (ref "U$3") (pin "2") (pinfunction "DIG0_2") (pintype "output"))
    )
    (net (code "49") (name "DIG1") (class "Default")
      (node (ref "K35") (pin "6") (pinfunction "6_6") (pintype "passive"))
      (node (ref "U$3") (pin "11") (pinfunction "DIG1_11") (pintype "output"))
    )
    (net (code "50") (name "DIG2") (class "Default")
      (node (ref "K35") (pin "7") (pinfunction "7_7") (pintype "passive"))
      (node (ref "U$3") (pin "6") (pinfunction "DIG2_6") (pintype "output"))
    )
    (net (code "51") (name "DIG3") (class "Default")
      (node (ref "K35") (pin "8") (pinfunction "8_8") (pintype "passive"))
      (node (ref "U$3") (pin "7") (pinfunction "DIG3_7") (pintype "output"))
    )
    (net (code "52") (name "DIG4") (class "Default")
      (node (ref "U$3") (pin "3") (pinfunction "DIG4_3") (pintype "output"))
    )
    (net (code "53") (name "DIG5") (class "Default")
      (node (ref "U$3") (pin "10") (pinfunction "DIG5_10") (pintype "output"))
    )
    (net (code "54") (name "DIG6") (class "Default")
      (node (ref "U$3") (pin "5") (pinfunction "DIG6_5") (pintype "output"))
    )
    (net (code "55") (name "DIG7") (class "Default")
      (node (ref "U$3") (pin "8") (pinfunction "DIG7_8") (pintype "output"))
    )
    (net (code "56") (name "EN") (class "Default")
      (node (ref "K34") (pin "16") (pinfunction "16_16") (pintype "passive"))
      (node (ref "U1") (pin "52") (pinfunction "(RD)PG1_52") (pintype "bidirectional"))
    )
    (net (code "57") (name "GND") (class "Default")
      (node (ref "B1") (pin "-") (pinfunction "-_-") (pintype "passive"))
      (node (ref "C1") (pin "2") (pinfunction "2_2") (pintype "passive"))
      (node (ref "C10") (pin "-") (pinfunction "-_-") (pintype "passive"))
      (node (ref "C11") (pin "2") (pinfunction "2_2") (pintype "passive"))
      (node (ref "C12") (pin "2") (pinfunction "2_2") (pintype "passive"))
      (node (ref "C13") (pin "-") (pinfunction "-_-") (pintype "passive"))
      (node (ref "C14") (pin "2") (pinfunction "2_2") (pintype "passive"))
      (node (ref "C15") (pin "2") (pinfunction "2_2") (pintype "passive"))
      (node (ref "C16") (pin "2") (pinfunction "2_2") (pintype "passive"))
      (node (ref "C17") (pin "2") (pinfunction "2_2") (pintype "passive"))
      (node (ref "C18") (pin "2") (pinfunction "2_2") (pintype "passive"))
      (node (ref "C19") (pin "2") (pinfunction "2_2") (pintype "passive"))
      (node (ref "C2") (pin "2") (pinfunction "2_2") (pintype "passive"))
      (node (ref "C20") (pin "2") (pinfunction "2_2") (pintype "passive"))
      (node (ref "C21") (pin "2") (pinfunction "2_2") (pintype "passive"))
      (node (ref "C22") (pin "2") (pinfunction "2_2") (pintype "passive"))
      (node (ref "C23") (pin "2") (pinfunction "2_2") (pintype "passive"))
      (node (ref "C24") (pin "2") (pinfunction "2_2") (pintype "passive"))
      (node (ref "C25") (pin "2") (pinfunction "2_2") (pintype "passive"))
      (node (ref "C26") (pin "2") (pinfunction "2_2") (pintype "passive"))
      (node (ref "C27") (pin "2") (pinfunction "2_2") (pintype "passive"))
      (node (ref "C28") (pin "2") (pinfunction "2_2") (pintype "passive"))
      (node (ref "C29") (pin "2") (pinfunction "2_2") (pintype "passive"))
      (node (ref "C3") (pin "2") (pinfunction "2_2") (pintype "passive"))
      (node (ref "C30") (pin "2") (pinfunction "2_2") (pintype "passive"))
      (node (ref "C31") (pin "2") (pinfunction "2_2") (pintype "passive"))
      (node (ref "C32") (pin "2") (pinfunction "2_2") (pintype "passive"))
      (node (ref "C33") (pin "2") (pinfunction "2_2") (pintype "passive"))
      (node (ref "C34") (pin "2") (pinfunction "2_2") (pintype "passive"))
      (node (ref "C37") (pin "2") (pinfunction "2_2") (pintype "passive"))
      (node (ref "C38") (pin "1") (pinfunction "1_1") (pintype "passive"))
      (node (ref "C39") (pin "2") (pinfunction "2_2") (pintype "passive"))
      (node (ref "C4") (pin "1") (pinfunction "1_1") (pintype "passive"))
      (node (ref "C40") (pin "-") (pinfunction "-_-") (pintype "passive"))
      (node (ref "C41") (pin "2") (pinfunction "2_2") (pintype "passive"))
      (node (ref "C42") (pin "2") (pinfunction "2_2") (pintype "passive"))
      (node (ref "C43") (pin "2") (pinfunction "2_2") (pintype "passive"))
      (node (ref "C44") (pin "2") (pinfunction "2_2") (pintype "passive"))
      (node (ref "C45") (pin "-") (pinfunction "-_-") (pintype "passive"))
      (node (ref "C5") (pin "1") (pinfunction "1_1") (pintype "passive"))
      (node (ref "C6") (pin "2") (pinfunction "2_2") (pintype "passive"))
      (node (ref "C7") (pin "2") (pinfunction "2_2") (pintype "passive"))
      (node (ref "C8") (pin "2") (pinfunction "2_2") (pintype "passive"))
      (node (ref "C9") (pin "2") (pinfunction "2_2") (pintype "passive"))
      (node (ref "G1") (pin "-") (pinfunction "-_-") (pintype "passive"))
      (node (ref "IC1") (pin "10") (pinfunction "GND_10") (pintype "power_in"))
      (node (ref "IC2") (pin "10") (pinfunction "GND_10") (pintype "power_in"))
      (node (ref "IC3") (pin "10") (pinfunction "GND_10") (pintype "power_in"))
      (node (ref "IC4") (pin "10") (pinfunction "GND_10") (pintype "power_in"))
      (node (ref "IC5") (pin "2") (pinfunction "GND_2") (pintype "passive"))
      (node (ref "IC6") (pin "4") (pinfunction "GND_4") (pintype "power_in"))
      (node (ref "J1") (pin "10") (pinfunction "GND_10") (pintype "power_in"))
      (node (ref "J1") (pin "4") (pinfunction "GND_4") (pintype "power_in"))
      (node (ref "J1") (pin "6") (pinfunction "GND_6") (pintype "power_in"))
      (node (ref "J1") (pin "8") (pinfunction "GND_8") (pintype "power_in"))
      (node (ref "K33") (pin "35") (pinfunction "35_35") (pintype "passive"))
      (node (ref "K33") (pin "36") (pinfunction "36_36") (pintype "passive"))
      (node (ref "K33") (pin "39") (pinfunction "39_39") (pintype "passive"))
      (node (ref "K33") (pin "40") (pinfunction "40_40") (pintype "passive"))
      (node (ref "K34") (pin "14") (pinfunction "14_14") (pintype "passive"))
      (node (ref "K35") (pin "19") (pinfunction "19_19") (pintype "passive"))
      (node (ref "K35") (pin "20") (pinfunction "20_20") (pintype "passive"))
      (node (ref "OK1") (pin "2") (pinfunction "C_2") (pintype "passive"))
      (node (ref "OK1") (pin "3") (pinfunction "EMIT_3") (pintype "passive"))
      (node (ref "OK10") (pin "2") (pinfunction "C_2") (pintype "passive"))
      (node (ref "OK10") (pin "3") (pinfunction "EMIT_3") (pintype "passive"))
      (node (ref "OK11") (pin "2") (pinfunction "C_2") (pintype "passive"))
      (node (ref "OK11") (pin "3") (pinfunction "EMIT_3") (pintype "passive"))
      (node (ref "OK12") (pin "2") (pinfunction "C_2") (pintype "passive"))
      (node (ref "OK12") (pin "3") (pinfunction "EMIT_3") (pintype "passive"))
      (node (ref "OK13") (pin "2") (pinfunction "C_2") (pintype "passive"))
      (node (ref "OK13") (pin "3") (pinfunction "EMIT_3") (pintype "passive"))
      (node (ref "OK14") (pin "2") (pinfunction "C_2") (pintype "passive"))
      (node (ref "OK14") (pin "3") (pinfunction "EMIT_3") (pintype "passive"))
      (node (ref "OK15") (pin "2") (pinfunction "C_2") (pintype "passive"))
      (node (ref "OK15") (pin "3") (pinfunction "EMIT_3") (pintype "passive"))
      (node (ref "OK16") (pin "2") (pinfunction "C_2") (pintype "passive"))
      (node (ref "OK16") (pin "3") (pinfunction "EMIT_3") (pintype "passive"))
      (node (ref "OK17") (pin "2") (pinfunction "C_2") (pintype "passive"))
      (node (ref "OK17") (pin "3") (pinfunction "EMIT_3") (pintype "passive"))
      (node (ref "OK18") (pin "2") (pinfunction "C_2") (pintype "passive"))
      (node (ref "OK18") (pin "3") (pinfunction "EMIT_3") (pintype "passive"))
      (node (ref "OK19") (pin "2") (pinfunction "C_2") (pintype "passive"))
      (node (ref "OK19") (pin "3") (pinfunction "EMIT_3") (pintype "passive"))
      (node (ref "OK2") (pin "2") (pinfunction "C_2") (pintype "passive"))
      (node (ref "OK2") (pin "3") (pinfunction "EMIT_3") (pintype "passive"))
      (node (ref "OK20") (pin "2") (pinfunction "C_2") (pintype "passive"))
      (node (ref "OK20") (pin "3") (pinfunction "EMIT_3") (pintype "passive"))
      (node (ref "OK21") (pin "2") (pinfunction "C_2") (pintype "passive"))
      (node (ref "OK21") (pin "3") (pinfunction "EMIT_3") (pintype "passive"))
      (node (ref "OK22") (pin "2") (pinfunction "C_2") (pintype "passive"))
      (node (ref "OK22") (pin "3") (pinfunction "EMIT_3") (pintype "passive"))
      (node (ref "OK23") (pin "2") (pinfunction "C_2") (pintype "passive"))
      (node (ref "OK23") (pin "3") (pinfunction "EMIT_3") (pintype "passive"))
      (node (ref "OK24") (pin "2") (pinfunction "C_2") (pintype "passive"))
      (node (ref "OK24") (pin "3") (pinfunction "EMIT_3") (pintype "passive"))
      (node (ref "OK25") (pin "2") (pinfunction "C_2") (pintype "passive"))
      (node (ref "OK25") (pin "3") (pinfunction "EMIT_3") (pintype "passive"))
      (node (ref "OK26") (pin "2") (pinfunction "C_2") (pintype "passive"))
      (node (ref "OK26") (pin "3") (pinfunction "EMIT_3") (pintype "passive"))
      (node (ref "OK27") (pin "2") (pinfunction "C_2") (pintype "passive"))
      (node (ref "OK27") (pin "3") (pinfunction "EMIT_3") (pintype "passive"))
      (node (ref "OK28") (pin "2") (pinfunction "C_2") (pintype "passive"))
      (node (ref "OK28") (pin "3") (pinfunction "EMIT_3") (pintype "passive"))
      (node (ref "OK29") (pin "2") (pinfunction "C_2") (pintype "passive"))
      (node (ref "OK29") (pin "3") (pinfunction "EMIT_3") (pintype "passive"))
      (node (ref "OK3") (pin "2") (pinfunction "C_2") (pintype "passive"))
      (node (ref "OK3") (pin "3") (pinfunction "EMIT_3") (pintype "passive"))
      (node (ref "OK30") (pin "2") (pinfunction "C_2") (pintype "passive"))
      (node (ref "OK30") (pin "3") (pinfunction "EMIT_3") (pintype "passive"))
      (node (ref "OK31") (pin "2") (pinfunction "C_2") (pintype "passive"))
      (node (ref "OK31") (pin "3") (pinfunction "EMIT_3") (pintype "passive"))
      (node (ref "OK32") (pin "2") (pinfunction "C_2") (pintype "passive"))
      (node (ref "OK32") (pin "3") (pinfunction "EMIT_3") (pintype "passive"))
      (node (ref "OK33") (pin "2") (pinfunction "C_2") (pintype "passive"))
      (node (ref "OK33") (pin "3") (pinfunction "EMIT_3") (pintype "passive"))
      (node (ref "OK4") (pin "2") (pinfunction "C_2") (pintype "passive"))
      (node (ref "OK4") (pin "3") (pinfunction "EMIT_3") (pintype "passive"))
      (node (ref "OK42") (pin "2") (pinfunction "C_2") (pintype "passive"))
      (node (ref "OK42") (pin "3") (pinfunction "EMIT_3") (pintype "passive"))
      (node (ref "OK43") (pin "2") (pinfunction "C_2") (pintype "passive"))
      (node (ref "OK43") (pin "3") (pinfunction "EMIT_3") (pintype "passive"))
      (node (ref "OK44") (pin "2") (pinfunction "C_2") (pintype "passive"))
      (node (ref "OK44") (pin "3") (pinfunction "EMIT_3") (pintype "passive"))
      (node (ref "OK45") (pin "2") (pinfunction "C_2") (pintype "passive"))
      (node (ref "OK45") (pin "3") (pinfunction "EMIT_3") (pintype "passive"))
      (node (ref "OK5") (pin "2") (pinfunction "C_2") (pintype "passive"))
      (node (ref "OK5") (pin "3") (pinfunction "EMIT_3") (pintype "passive"))
      (node (ref "OK6") (pin "2") (pinfunction "C_2") (pintype "passive"))
      (node (ref "OK6") (pin "3") (pinfunction "EMIT_3") (pintype "passive"))
      (node (ref "OK7") (pin "2") (pinfunction "C_2") (pintype "passive"))
      (node (ref "OK7") (pin "3") (pinfunction "EMIT_3") (pintype "passive"))
      (node (ref "OK8") (pin "2") (pinfunction "C_2") (pintype "passive"))
      (node (ref "OK8") (pin "3") (pinfunction "EMIT_3") (pintype "passive"))
      (node (ref "OK9") (pin "2") (pinfunction "C_2") (pintype "passive"))
      (node (ref "OK9") (pin "3") (pinfunction "EMIT_3") (pintype "passive"))
      (node (ref "R90") (pin "1") (pinfunction "1_1") (pintype "passive"))
      (node (ref "S31") (pin "B2") (pinfunction "2_B2") (pintype "passive"))
      (node (ref "TP2") (pin "TP") (pinfunction "TP_TP") (pintype "input"))
      (node (ref "U$1") (pin "4") (pinfunction "VSS_4") (pintype "power_in"))
      (node (ref "U$2") (pin "4") (pinfunction "GND_4") (pintype "bidirectional"))
      (node (ref "U$3") (pin "4") (pinfunction "GND_4") (pintype "power_in"))
      (node (ref "U$3") (pin "9") (pinfunction "GND_9") (pintype "power_in"))
      (node (ref "U$4") (pin "10") (pinfunction "REF-_10") (pintype "input"))
      (node (ref "U$4") (pin "16") (pinfunction "GND_16") (pintype "input"))
      (node (ref "U$5") (pin "10") (pinfunction "REF-_10") (pintype "input"))
      (node (ref "U$5") (pin "16") (pinfunction "GND_16") (pintype "input"))
      (node (ref "U$6") (pin "1") (pinfunction "EN_1") (pintype "bidirectional"))
      (node (ref "U$6") (pin "14") (pinfunction "FORCEON_14") (pintype "bidirectional"))
      (node (ref "U$6") (pin "18") (pinfunction "GND_18") (pintype "bidirectional"))
      (node (ref "U$8") (pin "5") (pinfunction "GND_5") (pintype "bidirectional"))
      (node (ref "U1") (pin "11") (pinfunction "GND_11") (pintype "power_in"))
      (node (ref "U1") (pin "32") (pinfunction "GND1_32") (pintype "power_in"))
      (node (ref "U1") (pin "62") (pinfunction "GND2_62") (pintype "power_in"))
      (node (ref "U1") (pin "81") (pinfunction "GND3_81") (pintype "power_in"))
      (node (ref "U1") (pin "99") (pinfunction "AGND_99") (pintype "power_in"))
      (node (ref "X1") (pin "1") (pinfunction "1_1") (pintype "passive"))
      (node (ref "X2") (pin "3") (pinfunction "KL_3") (pintype "passive"))
      (node (ref "X7") (pin "5") (pinfunction "F_5") (pintype "passive"))
      (node (ref "X9") (pin "9") (pinfunction "1_9") (pintype "passive"))
    )
    (net (code "58") (name "I{slash}P1") (class "Default")
      (node (ref "OK34") (pin "3") (pinfunction "EMIT_3") (pintype "passive"))
      (node (ref "U1") (pin "35") (pinfunction "PL0(ICP4)_35") (pintype "bidirectional"))
    )
    (net (code "59") (name "I{slash}P2") (class "Default")
      (node (ref "OK35") (pin "3") (pinfunction "EMIT_3") (pintype "passive"))
      (node (ref "U1") (pin "36") (pinfunction "PL1(ICP5)_36") (pintype "bidirectional"))
    )
    (net (code "60") (name "I{slash}P3") (class "Default")
      (node (ref "OK36") (pin "3") (pinfunction "EMIT_3") (pintype "passive"))
      (node (ref "U1") (pin "37") (pinfunction "PL2(T5)_37") (pintype "bidirectional"))
    )
    (net (code "61") (name "I{slash}P4") (class "Default")
      (node (ref "OK37") (pin "3") (pinfunction "EMIT_3") (pintype "passive"))
      (node (ref "U1") (pin "38") (pinfunction "PL3(OC5A)_38") (pintype "bidirectional"))
    )
    (net (code "62") (name "I{slash}P5") (class "Default")
      (node (ref "OK38") (pin "3") (pinfunction "EMIT_3") (pintype "passive"))
      (node (ref "U1") (pin "39") (pinfunction "PL4(OC5B)_39") (pintype "bidirectional"))
    )
    (net (code "63") (name "I{slash}P6") (class "Default")
      (node (ref "OK39") (pin "3") (pinfunction "EMIT_3") (pintype "passive"))
      (node (ref "U1") (pin "40") (pinfunction "PL5(OC5C)_40") (pintype "bidirectional"))
    )
    (net (code "64") (name "I{slash}P7") (class "Default")
      (node (ref "OK40") (pin "3") (pinfunction "EMIT_3") (pintype "passive"))
      (node (ref "U1") (pin "41") (pinfunction "PL6_41") (pintype "bidirectional"))
    )
    (net (code "65") (name "I{slash}P8") (class "Default")
      (node (ref "OK41") (pin "3") (pinfunction "EMIT_3") (pintype "passive"))
      (node (ref "U1") (pin "42") (pinfunction "PL7_42") (pintype "bidirectional"))
    )
    (net (code "66") (name "LDRV_SS") (class "Default")
      (node (ref "U$3") (pin "12") (pinfunction "LOAD_12") (pintype "input"))
      (node (ref "U1") (pin "19") (pinfunction "(SS/PCINT0)PB0_19") (pintype "bidirectional"))
    )
    (net (code "67") (name "MISO") (class "Default")
      (node (ref "J1") (pin "9") (pinfunction "MISO_9") (pintype "passive"))
      (node (ref "U$3") (pin "24") (pinfunction "DOUT_24") (pintype "output"))
      (node (ref "U$4") (pin "13") (pinfunction "DOUT_13") (pintype "bidirectional"))
      (node (ref "U$5") (pin "13") (pinfunction "DOUT_13") (pintype "bidirectional"))
      (node (ref "U1") (pin "22") (pinfunction "(MISO/PCINT3)PB3_22") (pintype "bidirectional"))
    )
    (net (code "68") (name "MOSI") (class "Default")
      (node (ref "J1") (pin "1") (pinfunction "MOSI_1") (pintype "passive"))
      (node (ref "U$3") (pin "1") (pinfunction "DIN_1") (pintype "input"))
      (node (ref "U$4") (pin "14") (pinfunction "DIN_14") (pintype "bidirectional"))
      (node (ref "U$5") (pin "14") (pinfunction "DIN_14") (pintype "bidirectional"))
      (node (ref "U1") (pin "21") (pinfunction "(MOSI/PCINT2)PB2_21") (pintype "bidirectional"))
    )
    (net (code "69") (name "Net-(B1-PadAC1)") (class "Default")
      (node (ref "B1") (pin "AC1") (pinfunction "AC1_AC1") (pintype "passive"))
      (node (ref "X8") (pin "1") (pinfunction "1_1") (pintype "passive"))
    )
    (net (code "70") (name "Net-(D33-PadA)") (class "Default")
      (node (ref "D33") (pin "A") (pinfunction "A_A") (pintype "passive"))
      (node (ref "R42") (pin "1") (pinfunction "1_1") (pintype "passive"))
    )
    (net (code "71") (name "Net-(D34-PadA)") (class "Default")
      (node (ref "D34") (pin "A") (pinfunction "A_A") (pintype "passive"))
      (node (ref "R43") (pin "1") (pinfunction "1_1") (pintype "passive"))
    )
    (net (code "72") (name "Net-(D35-PadA)") (class "Default")
      (node (ref "D35") (pin "A") (pinfunction "A_A") (pintype "passive"))
      (node (ref "R44") (pin "1") (pinfunction "1_1") (pintype "passive"))
    )
    (net (code "73") (name "Net-(D36-PadA)") (class "Default")
      (node (ref "D36") (pin "A") (pinfunction "A_A") (pintype "passive"))
      (node (ref "R45") (pin "1") (pinfunction "1_1") (pintype "passive"))
    )
    (net (code "74") (name "Net-(D37-PadA)") (class "Default")
      (node (ref "D37") (pin "A") (pinfunction "A_A") (pintype "passive"))
      (node (ref "R46") (pin "1") (pinfunction "1_1") (pintype "passive"))
    )
    (net (code "75") (name "Net-(D38-PadA)") (class "Default")
      (node (ref "D38") (pin "A") (pinfunction "A_A") (pintype "passive"))
      (node (ref "R47") (pin "1") (pinfunction "1_1") (pintype "passive"))
    )
    (net (code "76") (name "Net-(D39-PadA)") (class "Default")
      (node (ref "D39") (pin "A") (pinfunction "A_A") (pintype "passive"))
      (node (ref "R48") (pin "1") (pinfunction "1_1") (pintype "passive"))
    )
    (net (code "77") (name "Net-(D40-PadA)") (class "Default")
      (node (ref "D40") (pin "A") (pinfunction "A_A") (pintype "passive"))
      (node (ref "R49") (pin "1") (pinfunction "1_1") (pintype "passive"))
    )
    (net (code "78") (name "Net-(D41-PadA)") (class "Default")
      (node (ref "D41") (pin "A") (pinfunction "A_A") (pintype "passive"))
      (node (ref "R50") (pin "1") (pinfunction "1_1") (pintype "passive"))
    )
    (net (code "79") (name "Net-(D42-PadA)") (class "Default")
      (node (ref "D42") (pin "A") (pinfunction "A_A") (pintype "passive"))
      (node (ref "R51") (pin "1") (pinfunction "1_1") (pintype "passive"))
    )
    (net (code "80") (name "Net-(D43-PadA)") (class "Default")
      (node (ref "D43") (pin "A") (pinfunction "A_A") (pintype "passive"))
      (node (ref "R52") (pin "1") (pinfunction "1_1") (pintype "passive"))
    )
    (net (code "81") (name "Net-(D44-PadA)") (class "Default")
      (node (ref "D44") (pin "A") (pinfunction "A_A") (pintype "passive"))
      (node (ref "R53") (pin "1") (pinfunction "1_1") (pintype "passive"))
    )
    (net (code "82") (name "Net-(D45-PadA)") (class "Default")
      (node (ref "D45") (pin "A") (pinfunction "A_A") (pintype "passive"))
      (node (ref "R54") (pin "1") (pinfunction "1_1") (pintype "passive"))
    )
    (net (code "83") (name "Net-(D46-PadA)") (class "Default")
      (node (ref "D46") (pin "A") (pinfunction "A_A") (pintype "passive"))
      (node (ref "R55") (pin "1") (pinfunction "1_1") (pintype "passive"))
    )
    (net (code "84") (name "Net-(D47-PadA)") (class "Default")
      (node (ref "D47") (pin "A") (pinfunction "A_A") (pintype "passive"))
      (node (ref "R56") (pin "1") (pinfunction "1_1") (pintype "passive"))
    )
    (net (code "85") (name "Net-(D48-PadA)") (class "Default")
      (node (ref "D48") (pin "A") (pinfunction "A_A") (pintype "passive"))
      (node (ref "R57") (pin "1") (pinfunction "1_1") (pintype "passive"))
    )
    (net (code "86") (name "Net-(D49-PadA)") (class "Default")
      (node (ref "D49") (pin "A") (pinfunction "A_A") (pintype "passive"))
      (node (ref "R58") (pin "1") (pinfunction "1_1") (pintype "passive"))
    )
    (net (code "87") (name "Net-(D50-PadA)") (class "Default")
      (node (ref "D50") (pin "A") (pinfunction "A_A") (pintype "passive"))
      (node (ref "R59") (pin "1") (pinfunction "1_1") (pintype "passive"))
    )
    (net (code "88") (name "Net-(D51-PadA)") (class "Default")
      (node (ref "D51") (pin "A") (pinfunction "A_A") (pintype "passive"))
      (node (ref "R60") (pin "1") (pinfunction "1_1") (pintype "passive"))
    )
    (net (code "89") (name "Net-(D52-PadA)") (class "Default")
      (node (ref "D52") (pin "A") (pinfunction "A_A") (pintype "passive"))
      (node (ref "R61") (pin "1") (pinfunction "1_1") (pintype "passive"))
    )
    (net (code "90") (name "Net-(D53-PadA)") (class "Default")
      (node (ref "D53") (pin "A") (pinfunction "A_A") (pintype "passive"))
      (node (ref "R62") (pin "1") (pinfunction "1_1") (pintype "passive"))
    )
    (net (code "91") (name "Net-(D54-PadA)") (class "Default")
      (node (ref "D54") (pin "A") (pinfunction "A_A") (pintype "passive"))
      (node (ref "R63") (pin "1") (pinfunction "1_1") (pintype "passive"))
    )
    (net (code "92") (name "Net-(D55-PadA)") (class "Default")
      (node (ref "D55") (pin "A") (pinfunction "A_A") (pintype "passive"))
      (node (ref "R64") (pin "1") (pinfunction "1_1") (pintype "passive"))
    )
    (net (code "93") (name "Net-(D56-PadA)") (class "Default")
      (node (ref "D56") (pin "A") (pinfunction "A_A") (pintype "passive"))
      (node (ref "R65") (pin "1") (pinfunction "1_1") (pintype "passive"))
    )
    (net (code "94") (name "Net-(D57-PadA)") (class "Default")
      (node (ref "D57") (pin "A") (pinfunction "A_A") (pintype "passive"))
      (node (ref "R66") (pin "1") (pinfunction "1_1") (pintype "passive"))
    )
    (net (code "95") (name "Net-(D58-PadA)") (class "Default")
      (node (ref "D58") (pin "A") (pinfunction "A_A") (pintype "passive"))
      (node (ref "R67") (pin "1") (pinfunction "1_1") (pintype "passive"))
    )
    (net (code "96") (name "Net-(D59-PadA)") (class "Default")
      (node (ref "D59") (pin "A") (pinfunction "A_A") (pintype "passive"))
      (node (ref "R68") (pin "1") (pinfunction "1_1") (pintype "passive"))
    )
    (net (code "97") (name "Net-(D60-PadA)") (class "Default")
      (node (ref "D60") (pin "A") (pinfunction "A_A") (pintype "passive"))
      (node (ref "R69") (pin "1") (pinfunction "1_1") (pintype "passive"))
    )
    (net (code "98") (name "Net-(D61-PadA)") (class "Default")
      (node (ref "D61") (pin "A") (pinfunction "A_A") (pintype "passive"))
      (node (ref "R70") (pin "1") (pinfunction "1_1") (pintype "passive"))
    )
    (net (code "99") (name "Net-(D62-PadA)") (class "Default")
      (node (ref "D62") (pin "A") (pinfunction "A_A") (pintype "passive"))
      (node (ref "R71") (pin "1") (pinfunction "1_1") (pintype "passive"))
    )
    (net (code "100") (name "Net-(D63-PadA)") (class "Default")
      (node (ref "D63") (pin "A") (pinfunction "A_A") (pintype "passive"))
      (node (ref "R72") (pin "1") (pinfunction "1_1") (pintype "passive"))
    )
    (net (code "101") (name "Net-(D64-PadA)") (class "Default")
      (node (ref "D64") (pin "A") (pinfunction "A_A") (pintype "passive"))
      (node (ref "R73") (pin "1") (pinfunction "1_1") (pintype "passive"))
    )
    (net (code "102") (name "Net-(IC1A-1Q)") (class "Default")
      (node (ref "IC1") (pin "2") (pinfunction "1Q_2") (pintype "tri_state"))
      (node (ref "R10") (pin "1") (pinfunction "1_1") (pintype "passive"))
    )
    (net (code "103") (name "Net-(IC1A-2Q)") (class "Default")
      (node (ref "IC1") (pin "5") (pinfunction "2Q_5") (pintype "tri_state"))
      (node (ref "R11") (pin "1") (pinfunction "1_1") (pintype "passive"))
    )
    (net (code "104") (name "Net-(IC1A-3Q)") (class "Default")
      (node (ref "IC1") (pin "6") (pinfunction "3Q_6") (pintype "tri_state"))
      (node (ref "R12") (pin "1") (pinfunction "1_1") (pintype "passive"))
    )
    (net (code "105") (name "Net-(IC1A-4Q)") (class "Default")
      (node (ref "IC1") (pin "9") (pinfunction "4Q_9") (pintype "tri_state"))
      (node (ref "R13") (pin "1") (pinfunction "1_1") (pintype "passive"))
    )
    (net (code "106") (name "Net-(IC1A-5Q)") (class "Default")
      (node (ref "IC1") (pin "12") (pinfunction "5Q_12") (pintype "tri_state"))
      (node (ref "R14") (pin "1") (pinfunction "1_1") (pintype "passive"))
    )
    (net (code "107") (name "Net-(IC1A-6Q)") (class "Default")
      (node (ref "IC1") (pin "15") (pinfunction "6Q_15") (pintype "tri_state"))
      (node (ref "R15") (pin "1") (pinfunction "1_1") (pintype "passive"))
    )
    (net (code "108") (name "Net-(IC1A-7Q)") (class "Default")
      (node (ref "IC1") (pin "16") (pinfunction "7Q_16") (pintype "tri_state"))
      (node (ref "R16") (pin "1") (pinfunction "1_1") (pintype "passive"))
    )
    (net (code "109") (name "Net-(IC1A-8Q)") (class "Default")
      (node (ref "IC1") (pin "19") (pinfunction "8Q_19") (pintype "tri_state"))
      (node (ref "R17") (pin "1") (pinfunction "1_1") (pintype "passive"))
    )
    (net (code "110") (name "Net-(IC2A-1Q)") (class "Default")
      (node (ref "IC2") (pin "2") (pinfunction "1Q_2") (pintype "tri_state"))
      (node (ref "R18") (pin "1") (pinfunction "1_1") (pintype "passive"))
    )
    (net (code "111") (name "Net-(IC2A-2Q)") (class "Default")
      (node (ref "IC2") (pin "5") (pinfunction "2Q_5") (pintype "tri_state"))
      (node (ref "R19") (pin "1") (pinfunction "1_1") (pintype "passive"))
    )
    (net (code "112") (name "Net-(IC2A-3Q)") (class "Default")
      (node (ref "IC2") (pin "6") (pinfunction "3Q_6") (pintype "tri_state"))
      (node (ref "R20") (pin "1") (pinfunction "1_1") (pintype "passive"))
    )
    (net (code "113") (name "Net-(IC2A-4Q)") (class "Default")
      (node (ref "IC2") (pin "9") (pinfunction "4Q_9") (pintype "tri_state"))
      (node (ref "R21") (pin "1") (pinfunction "1_1") (pintype "passive"))
    )
    (net (code "114") (name "Net-(IC2A-5Q)") (class "Default")
      (node (ref "IC2") (pin "12") (pinfunction "5Q_12") (pintype "tri_state"))
      (node (ref "R22") (pin "1") (pinfunction "1_1") (pintype "passive"))
    )
    (net (code "115") (name "Net-(IC2A-6Q)") (class "Default")
      (node (ref "IC2") (pin "15") (pinfunction "6Q_15") (pintype "tri_state"))
      (node (ref "R23") (pin "1") (pinfunction "1_1") (pintype "passive"))
    )
    (net (code "116") (name "Net-(IC2A-7Q)") (class "Default")
      (node (ref "IC2") (pin "16") (pinfunction "7Q_16") (pintype "tri_state"))
      (node (ref "R24") (pin "1") (pinfunction "1_1") (pintype "passive"))
    )
    (net (code "117") (name "Net-(IC2A-8Q)") (class "Default")
      (node (ref "IC2") (pin "19") (pinfunction "8Q_19") (pintype "tri_state"))
      (node (ref "R25") (pin "1") (pinfunction "1_1") (pintype "passive"))
    )
    (net (code "118") (name "Net-(IC3A-1Q)") (class "Default")
      (node (ref "IC3") (pin "2") (pinfunction "1Q_2") (pintype "tri_state"))
      (node (ref "R26") (pin "1") (pinfunction "1_1") (pintype "passive"))
    )
    (net (code "119") (name "Net-(IC3A-2Q)") (class "Default")
      (node (ref "IC3") (pin "5") (pinfunction "2Q_5") (pintype "tri_state"))
      (node (ref "R27") (pin "1") (pinfunction "1_1") (pintype "passive"))
    )
    (net (code "120") (name "Net-(IC3A-3Q)") (class "Default")
      (node (ref "IC3") (pin "6") (pinfunction "3Q_6") (pintype "tri_state"))
      (node (ref "R28") (pin "1") (pinfunction "1_1") (pintype "passive"))
    )
    (net (code "121") (name "Net-(IC3A-4Q)") (class "Default")
      (node (ref "IC3") (pin "9") (pinfunction "4Q_9") (pintype "tri_state"))
      (node (ref "R29") (pin "1") (pinfunction "1_1") (pintype "passive"))
    )
    (net (code "122") (name "Net-(IC3A-5Q)") (class "Default")
      (node (ref "IC3") (pin "12") (pinfunction "5Q_12") (pintype "tri_state"))
      (node (ref "R30") (pin "1") (pinfunction "1_1") (pintype "passive"))
    )
    (net (code "123") (name "Net-(IC3A-6Q)") (class "Default")
      (node (ref "IC3") (pin "15") (pinfunction "6Q_15") (pintype "tri_state"))
      (node (ref "R31") (pin "1") (pinfunction "1_1") (pintype "passive"))
    )
    (net (code "124") (name "Net-(IC3A-7Q)") (class "Default")
      (node (ref "IC3") (pin "16") (pinfunction "7Q_16") (pintype "tri_state"))
      (node (ref "R32") (pin "1") (pinfunction "1_1") (pintype "passive"))
    )
    (net (code "125") (name "Net-(IC3A-8Q)") (class "Default")
      (node (ref "IC3") (pin "19") (pinfunction "8Q_19") (pintype "tri_state"))
      (node (ref "R33") (pin "1") (pinfunction "1_1") (pintype "passive"))
    )
    (net (code "126") (name "Net-(IC4A-1Q)") (class "Default")
      (node (ref "IC4") (pin "2") (pinfunction "1Q_2") (pintype "tri_state"))
      (node (ref "R34") (pin "1") (pinfunction "1_1") (pintype "passive"))
    )
    (net (code "127") (name "Net-(IC4A-2Q)") (class "Default")
      (node (ref "IC4") (pin "5") (pinfunction "2Q_5") (pintype "tri_state"))
      (node (ref "R35") (pin "1") (pinfunction "1_1") (pintype "passive"))
    )
    (net (code "128") (name "Net-(IC4A-3Q)") (class "Default")
      (node (ref "IC4") (pin "6") (pinfunction "3Q_6") (pintype "tri_state"))
      (node (ref "R36") (pin "1") (pinfunction "1_1") (pintype "passive"))
    )
    (net (code "129") (name "Net-(IC4A-4Q)") (class "Default")
      (node (ref "IC4") (pin "9") (pinfunction "4Q_9") (pintype "tri_state"))
      (node (ref "R37") (pin "1") (pinfunction "1_1") (pintype "passive"))
    )
    (net (code "130") (name "Net-(IC4A-5Q)") (class "Default")
      (node (ref "IC4") (pin "12") (pinfunction "5Q_12") (pintype "tri_state"))
      (node (ref "R38") (pin "1") (pinfunction "1_1") (pintype "passive"))
    )
    (net (code "131") (name "Net-(IC4A-6Q)") (class "Default")
      (node (ref "IC4") (pin "15") (pinfunction "6Q_15") (pintype "tri_state"))
      (node (ref "R39") (pin "1") (pinfunction "1_1") (pintype "passive"))
    )
    (net (code "132") (name "Net-(IC4A-7Q)") (class "Default")
      (node (ref "IC4") (pin "16") (pinfunction "7Q_16") (pintype "tri_state"))
      (node (ref "R40") (pin "1") (pinfunction "1_1") (pintype "passive"))
    )
    (net (code "133") (name "Net-(IC4A-8Q)") (class "Default")
      (node (ref "IC4") (pin "19") (pinfunction "8Q_19") (pintype "tri_state"))
      (node (ref "R41") (pin "1") (pinfunction "1_1") (pintype "passive"))
    )
    (net (code "134") (name "Net-(OK33-A)") (class "Default")
      (node (ref "OK33") (pin "1") (pinfunction "A_1") (pintype "passive"))
      (node (ref "R1") (pin "1") (pinfunction "1_1") (pintype "passive"))
    )
    (net (code "135") (name "Net-(OK33-COL)") (class "Default")
      (node (ref "OK33") (pin "4") (pinfunction "COL_4") (pintype "passive"))
      (node (ref "SP1") (pin "2") (pinfunction "2_2") (pintype "passive"))
    )
    (net (code "136") (name "Net-(OK34-A)") (class "Default")
      (node (ref "OK34") (pin "1") (pinfunction "A_1") (pintype "passive"))
      (node (ref "R7") (pin "1") (pinfunction "1_1") (pintype "passive"))
    )
    (net (code "137") (name "Net-(OK34-COL)") (class "Default")
      (node (ref "OK34") (pin "4") (pinfunction "COL_4") (pintype "passive"))
      (node (ref "R8") (pin "2") (pinfunction "2_2") (pintype "passive"))
    )
    (net (code "138") (name "Net-(OK35-A)") (class "Default")
      (node (ref "OK35") (pin "1") (pinfunction "A_1") (pintype "passive"))
      (node (ref "R9") (pin "1") (pinfunction "1_1") (pintype "passive"))
    )
    (net (code "139") (name "Net-(OK35-COL)") (class "Default")
      (node (ref "OK35") (pin "4") (pinfunction "COL_4") (pintype "passive"))
      (node (ref "R74") (pin "2") (pinfunction "2_2") (pintype "passive"))
    )
    (net (code "140") (name "Net-(OK36-A)") (class "Default")
      (node (ref "OK36") (pin "1") (pinfunction "A_1") (pintype "passive"))
      (node (ref "R75") (pin "1") (pinfunction "1_1") (pintype "passive"))
    )
    (net (code "141") (name "Net-(OK36-COL)") (class "Default")
      (node (ref "OK36") (pin "4") (pinfunction "COL_4") (pintype "passive"))
      (node (ref "R87") (pin "2") (pinfunction "2_2") (pintype "passive"))
    )
    (net (code "142") (name "Net-(OK37-A)") (class "Default")
      (node (ref "OK37") (pin "1") (pinfunction "A_1") (pintype "passive"))
      (node (ref "R88") (pin "1") (pinfunction "1_1") (pintype "passive"))
    )
    (net (code "143") (name "Net-(OK37-COL)") (class "Default")
      (node (ref "OK37") (pin "4") (pinfunction "COL_4") (pintype "passive"))
      (node (ref "R89") (pin "2") (pinfunction "2_2") (pintype "passive"))
    )
    (net (code "144") (name "Net-(OK38-A)") (class "Default")
      (node (ref "OK38") (pin "1") (pinfunction "A_1") (pintype "passive"))
      (node (ref "R92") (pin "1") (pinfunction "1_1") (pintype "passive"))
    )
    (net (code "145") (name "Net-(OK38-COL)") (class "Default")
      (node (ref "OK38") (pin "4") (pinfunction "COL_4") (pintype "passive"))
      (node (ref "R93") (pin "2") (pinfunction "2_2") (pintype "passive"))
    )
    (net (code "146") (name "Net-(OK39-A)") (class "Default")
      (node (ref "OK39") (pin "1") (pinfunction "A_1") (pintype "passive"))
      (node (ref "R94") (pin "1") (pinfunction "1_1") (pintype "passive"))
    )
    (net (code "147") (name "Net-(OK39-COL)") (class "Default")
      (node (ref "OK39") (pin "4") (pinfunction "COL_4") (pintype "passive"))
      (node (ref "R95") (pin "2") (pinfunction "2_2") (pintype "passive"))
    )
    (net (code "148") (name "Net-(OK40-A)") (class "Default")
      (node (ref "OK40") (pin "1") (pinfunction "A_1") (pintype "passive"))
      (node (ref "R96") (pin "1") (pinfunction "1_1") (pintype "passive"))
    )
    (net (code "149") (name "Net-(OK40-COL)") (class "Default")
      (node (ref "OK40") (pin "4") (pinfunction "COL_4") (pintype "passive"))
      (node (ref "R97") (pin "2") (pinfunction "2_2") (pintype "passive"))
    )
    (net (code "150") (name "Net-(OK41-A)") (class "Default")
      (node (ref "OK41") (pin "1") (pinfunction "A_1") (pintype "passive"))
      (node (ref "R98") (pin "1") (pinfunction "1_1") (pintype "passive"))
    )
    (net (code "151") (name "Net-(OK41-COL)") (class "Default")
      (node (ref "OK41") (pin "4") (pinfunction "COL_4") (pintype "passive"))
      (node (ref "R99") (pin "2") (pinfunction "2_2") (pintype "passive"))
    )
    (net (code "152") (name "Net-(OK42-A)") (class "Default")
      (node (ref "OK42") (pin "1") (pinfunction "A_1") (pintype "passive"))
      (node (ref "R100") (pin "1") (pinfunction "1_1") (pintype "passive"))
    )
    (net (code "153") (name "Net-(OK43-A)") (class "Default")
      (node (ref "OK43") (pin "1") (pinfunction "A_1") (pintype "passive"))
      (node (ref "R101") (pin "1") (pinfunction "1_1") (pintype "passive"))
    )
    (net (code "154") (name "Net-(OK44-A)") (class "Default")
      (node (ref "OK44") (pin "1") (pinfunction "A_1") (pintype "passive"))
      (node (ref "R102") (pin "1") (pinfunction "1_1") (pintype "passive"))
    )
    (net (code "155") (name "Net-(OK45-A)") (class "Default")
      (node (ref "OK45") (pin "1") (pinfunction "A_1") (pintype "passive"))
      (node (ref "R103") (pin "1") (pinfunction "1_1") (pintype "passive"))
    )
    (net (code "156") (name "Net-(R2-Pad2)") (class "Default")
      (node (ref "R2") (pin "2") (pinfunction "2_2") (pintype "passive"))
      (node (ref "SP1") (pin "1") (pinfunction "1_1") (pintype "passive"))
    )
    (net (code "157") (name "Net-(R78-Pad2)") (class "Default")
      (node (ref "R78") (pin "2") (pinfunction "2_2") (pintype "passive"))
      (node (ref "X9") (pin "1") (pinfunction "1_1") (pintype "passive"))
    )
    (net (code "158") (name "Net-(U$2-VBATT)") (class "Default")
      (node (ref "G1") (pin "+") (pinfunction "+_+") (pintype "passive"))
      (node (ref "U$2") (pin "3") (pinfunction "VBATT_3") (pintype "bidirectional"))
    )
    (net (code "159") (name "Net-(U$2-X1)") (class "Default")
      (node (ref "Q1") (pin "1") (pinfunction "1_1") (pintype "passive"))
      (node (ref "U$2") (pin "1") (pinfunction "X1_1") (pintype "bidirectional"))
    )
    (net (code "160") (name "Net-(U$2-X2)") (class "Default")
      (node (ref "Q1") (pin "2") (pinfunction "2_2") (pintype "passive"))
      (node (ref "U$2") (pin "2") (pinfunction "X2_2") (pintype "bidirectional"))
    )
    (net (code "161") (name "Net-(U$3-ISET)") (class "Default")
      (node (ref "R86") (pin "2") (pinfunction "2_2") (pintype "passive"))
      (node (ref "U$3") (pin "18") (pinfunction "ISET_18") (pintype "input"))
    )
    (net (code "162") (name "Net-(U$4-MCLKIN)") (class "Default")
      (node (ref "C21") (pin "1") (pinfunction "1_1") (pintype "passive"))
      (node (ref "U$4") (pin "2") (pinfunction "MCLKIN_2") (pintype "input"))
      (node (ref "Y1") (pin "2") (pinfunction "2_2") (pintype "passive"))
    )
    (net (code "163") (name "Net-(U$4-MCLKOUT)") (class "Default")
      (node (ref "C22") (pin "1") (pinfunction "1_1") (pintype "passive"))
      (node (ref "U$4") (pin "3") (pinfunction "MCLKOUT_3") (pintype "output"))
      (node (ref "Y1") (pin "1") (pinfunction "1_1") (pintype "passive"))
    )
    (net (code "164") (name "Net-(U$4-RESET)") (class "Default")
      (node (ref "R76") (pin "2") (pinfunction "2_2") (pintype "passive"))
      (node (ref "U$4") (pin "5") (pinfunction "RESET_5") (pintype "input"))
    )
    (net (code "165") (name "Net-(U$5-MCLKIN)") (class "Default")
      (node (ref "C23") (pin "1") (pinfunction "1_1") (pintype "passive"))
      (node (ref "U$5") (pin "2") (pinfunction "MCLKIN_2") (pintype "input"))
      (node (ref "Y2") (pin "2") (pinfunction "2_2") (pintype "passive"))
    )
    (net (code "166") (name "Net-(U$5-MCLKOUT)") (class "Default")
      (node (ref "C24") (pin "1") (pinfunction "1_1") (pintype "passive"))
      (node (ref "U$5") (pin "3") (pinfunction "MCLKOUT_3") (pintype "output"))
      (node (ref "Y2") (pin "1") (pinfunction "1_1") (pintype "passive"))
    )
    (net (code "167") (name "Net-(U$5-RESET)") (class "Default")
      (node (ref "R77") (pin "2") (pinfunction "2_2") (pintype "passive"))
      (node (ref "U$5") (pin "5") (pinfunction "RESET_5") (pintype "input"))
    )
    (net (code "168") (name "Net-(U$6-C1+)") (class "Default")
      (node (ref "C35") (pin "1") (pinfunction "1_1") (pintype "passive"))
      (node (ref "U$6") (pin "2") (pinfunction "C1+_2") (pintype "bidirectional"))
    )
    (net (code "169") (name "Net-(U$6-C1-)") (class "Default")
      (node (ref "C35") (pin "2") (pinfunction "2_2") (pintype "passive"))
      (node (ref "U$6") (pin "4") (pinfunction "C1-_4") (pintype "bidirectional"))
    )
    (net (code "170") (name "Net-(U$6-C2+)") (class "Default")
      (node (ref "C36") (pin "1") (pinfunction "1_1") (pintype "passive"))
      (node (ref "U$6") (pin "5") (pinfunction "C2+_5") (pintype "bidirectional"))
    )
    (net (code "171") (name "Net-(U$6-C2-)") (class "Default")
      (node (ref "C36") (pin "2") (pinfunction "2_2") (pintype "passive"))
      (node (ref "U$6") (pin "6") (pinfunction "C2-_6") (pintype "bidirectional"))
    )
    (net (code "172") (name "Net-(U$6-V+)") (class "Default")
      (node (ref "C37") (pin "1") (pinfunction "1_1") (pintype "passive"))
      (node (ref "U$6") (pin "3") (pinfunction "V+_3") (pintype "bidirectional"))
    )
    (net (code "173") (name "Net-(U$6-V-)") (class "Default")
      (node (ref "C38") (pin "2") (pinfunction "2_2") (pintype "passive"))
      (node (ref "U$6") (pin "7") (pinfunction "V-_7") (pintype "bidirectional"))
    )
    (net (code "174") (name "Net-(U$8-DE)") (class "Default")
      (node (ref "R91") (pin "2") (pinfunction "2_2") (pintype "passive"))
      (node (ref "U$8") (pin "3") (pinfunction "DE_3") (pintype "bidirectional"))
    )
    (net (code "175") (name "Net-(U$8-{slash}RE)") (class "Default")
      (node (ref "R90") (pin "2") (pinfunction "2_2") (pintype "passive"))
      (node (ref "U$8") (pin "2") (pinfunction "/RE_2") (pintype "bidirectional"))
    )
    (net (code "176") (name "Net-(U1-XTAL1)") (class "Default")
      (node (ref "C5") (pin "2") (pinfunction "2_2") (pintype "passive"))
      (node (ref "Q2") (pin "1") (pinfunction "1_1") (pintype "passive"))
      (node (ref "U1") (pin "34") (pinfunction "XTAL1_34") (pintype "input"))
    )
    (net (code "177") (name "Net-(U1-XTAL2)") (class "Default")
      (node (ref "C4") (pin "2") (pinfunction "2_2") (pintype "passive"))
      (node (ref "Q2") (pin "2") (pinfunction "2_2") (pintype "passive"))
      (node (ref "U1") (pin "33") (pinfunction "XTAL2_33") (pintype "output"))
    )
    (net (code "178") (name "Net-(X8B-1)") (class "Default")
      (node (ref "B1") (pin "AC2") (pinfunction "AC2_AC2") (pintype "passive"))
      (node (ref "X8") (pin "2") (pinfunction "1_2") (pintype "passive"))
    )
    (net (code "179") (name "Net-(X9B-1)") (class "Default")
      (node (ref "R79") (pin "2") (pinfunction "2_2") (pintype "passive"))
      (node (ref "X9") (pin "2") (pinfunction "1_2") (pintype "passive"))
    )
    (net (code "180") (name "Net-(X9C-1)") (class "Default")
      (node (ref "R80") (pin "2") (pinfunction "2_2") (pintype "passive"))
      (node (ref "X9") (pin "3") (pinfunction "1_3") (pintype "passive"))
    )
    (net (code "181") (name "Net-(X9D-1)") (class "Default")
      (node (ref "R81") (pin "2") (pinfunction "2_2") (pintype "passive"))
      (node (ref "X9") (pin "4") (pinfunction "1_4") (pintype "passive"))
    )
    (net (code "182") (name "Net-(X9E-1)") (class "Default")
      (node (ref "R82") (pin "2") (pinfunction "2_2") (pintype "passive"))
      (node (ref "X9") (pin "5") (pinfunction "1_5") (pintype "passive"))
    )
    (net (code "183") (name "Net-(X9F-1)") (class "Default")
      (node (ref "R83") (pin "2") (pinfunction "2_2") (pintype "passive"))
      (node (ref "X9") (pin "6") (pinfunction "1_6") (pintype "passive"))
    )
    (net (code "184") (name "Net-(X9G-1)") (class "Default")
      (node (ref "R84") (pin "2") (pinfunction "2_2") (pintype "passive"))
      (node (ref "X9") (pin "7") (pinfunction "1_7") (pintype "passive"))
    )
    (net (code "185") (name "Net-(X9H-1)") (class "Default")
      (node (ref "R85") (pin "2") (pinfunction "2_2") (pintype "passive"))
      (node (ref "X9") (pin "8") (pinfunction "1_8") (pintype "passive"))
    )
    (net (code "186") (name "OP1") (class "Default")
      (node (ref "OK1") (pin "1") (pinfunction "A_1") (pintype "passive"))
      (node (ref "R10") (pin "2") (pinfunction "2_2") (pintype "passive"))
    )
    (net (code "187") (name "OP2") (class "Default")
      (node (ref "OK2") (pin "1") (pinfunction "A_1") (pintype "passive"))
      (node (ref "R11") (pin "2") (pinfunction "2_2") (pintype "passive"))
    )
    (net (code "188") (name "OP3") (class "Default")
      (node (ref "OK3") (pin "1") (pinfunction "A_1") (pintype "passive"))
      (node (ref "R12") (pin "2") (pinfunction "2_2") (pintype "passive"))
    )
    (net (code "189") (name "OP4") (class "Default")
      (node (ref "OK4") (pin "1") (pinfunction "A_1") (pintype "passive"))
      (node (ref "R13") (pin "2") (pinfunction "2_2") (pintype "passive"))
    )
    (net (code "190") (name "OP5") (class "Default")
      (node (ref "OK5") (pin "1") (pinfunction "A_1") (pintype "passive"))
      (node (ref "R14") (pin "2") (pinfunction "2_2") (pintype "passive"))
    )
    (net (code "191") (name "OP6") (class "Default")
      (node (ref "OK6") (pin "1") (pinfunction "A_1") (pintype "passive"))
      (node (ref "R15") (pin "2") (pinfunction "2_2") (pintype "passive"))
    )
    (net (code "192") (name "OP7") (class "Default")
      (node (ref "OK7") (pin "1") (pinfunction "A_1") (pintype "passive"))
      (node (ref "R16") (pin "2") (pinfunction "2_2") (pintype "passive"))
    )
    (net (code "193") (name "OP8") (class "Default")
      (node (ref "OK8") (pin "1") (pinfunction "A_1") (pintype "passive"))
      (node (ref "R17") (pin "2") (pinfunction "2_2") (pintype "passive"))
    )
    (net (code "194") (name "OP9") (class "Default")
      (node (ref "OK17") (pin "1") (pinfunction "A_1") (pintype "passive"))
      (node (ref "R18") (pin "2") (pinfunction "2_2") (pintype "passive"))
    )
    (net (code "195") (name "OP10") (class "Default")
      (node (ref "OK18") (pin "1") (pinfunction "A_1") (pintype "passive"))
      (node (ref "R19") (pin "2") (pinfunction "2_2") (pintype "passive"))
    )
    (net (code "196") (name "OP11") (class "Default")
      (node (ref "OK19") (pin "1") (pinfunction "A_1") (pintype "passive"))
      (node (ref "R20") (pin "2") (pinfunction "2_2") (pintype "passive"))
    )
    (net (code "197") (name "OP12") (class "Default")
      (node (ref "OK20") (pin "1") (pinfunction "A_1") (pintype "passive"))
      (node (ref "R21") (pin "2") (pinfunction "2_2") (pintype "passive"))
    )
    (net (code "198") (name "OP13") (class "Default")
      (node (ref "OK21") (pin "1") (pinfunction "A_1") (pintype "passive"))
      (node (ref "R22") (pin "2") (pinfunction "2_2") (pintype "passive"))
    )
    (net (code "199") (name "OP14") (class "Default")
      (node (ref "OK22") (pin "1") (pinfunction "A_1") (pintype "passive"))
      (node (ref "R23") (pin "2") (pinfunction "2_2") (pintype "passive"))
    )
    (net (code "200") (name "OP15") (class "Default")
      (node (ref "OK23") (pin "1") (pinfunction "A_1") (pintype "passive"))
      (node (ref "R24") (pin "2") (pinfunction "2_2") (pintype "passive"))
    )
    (net (code "201") (name "OP16") (class "Default")
      (node (ref "OK24") (pin "1") (pinfunction "A_1") (pintype "passive"))
      (node (ref "R25") (pin "2") (pinfunction "2_2") (pintype "passive"))
    )
    (net (code "202") (name "OP17") (class "Default")
      (node (ref "OK9") (pin "1") (pinfunction "A_1") (pintype "passive"))
      (node (ref "R26") (pin "2") (pinfunction "2_2") (pintype "passive"))
    )
    (net (code "203") (name "OP18") (class "Default")
      (node (ref "OK10") (pin "1") (pinfunction "A_1") (pintype "passive"))
      (node (ref "R27") (pin "2") (pinfunction "2_2") (pintype "passive"))
    )
    (net (code "204") (name "OP19") (class "Default")
      (node (ref "OK11") (pin "1") (pinfunction "A_1") (pintype "passive"))
      (node (ref "R28") (pin "2") (pinfunction "2_2") (pintype "passive"))
    )
    (net (code "205") (name "OP20") (class "Default")
      (node (ref "OK12") (pin "1") (pinfunction "A_1") (pintype "passive"))
      (node (ref "R29") (pin "2") (pinfunction "2_2") (pintype "passive"))
    )
    (net (code "206") (name "OP21") (class "Default")
      (node (ref "OK13") (pin "1") (pinfunction "A_1") (pintype "passive"))
      (node (ref "R30") (pin "2") (pinfunction "2_2") (pintype "passive"))
    )
    (net (code "207") (name "OP22") (class "Default")
      (node (ref "OK14") (pin "1") (pinfunction "A_1") (pintype "passive"))
      (node (ref "R31") (pin "2") (pinfunction "2_2") (pintype "passive"))
    )
    (net (code "208") (name "OP23") (class "Default")
      (node (ref "OK15") (pin "1") (pinfunction "A_1") (pintype "passive"))
      (node (ref "R32") (pin "2") (pinfunction "2_2") (pintype "passive"))
    )
    (net (code "209") (name "OP24") (class "Default")
      (node (ref "OK16") (pin "1") (pinfunction "A_1") (pintype "passive"))
      (node (ref "R33") (pin "2") (pinfunction "2_2") (pintype "passive"))
    )
    (net (code "210") (name "OP25") (class "Default")
      (node (ref "OK25") (pin "1") (pinfunction "A_1") (pintype "passive"))
      (node (ref "R34") (pin "2") (pinfunction "2_2") (pintype "passive"))
    )
    (net (code "211") (name "OP26") (class "Default")
      (node (ref "OK26") (pin "1") (pinfunction "A_1") (pintype "passive"))
      (node (ref "R35") (pin "2") (pinfunction "2_2") (pintype "passive"))
    )
    (net (code "212") (name "OP27") (class "Default")
      (node (ref "OK27") (pin "1") (pinfunction "A_1") (pintype "passive"))
      (node (ref "R36") (pin "2") (pinfunction "2_2") (pintype "passive"))
    )
    (net (code "213") (name "OP28") (class "Default")
      (node (ref "OK28") (pin "1") (pinfunction "A_1") (pintype "passive"))
      (node (ref "R37") (pin "2") (pinfunction "2_2") (pintype "passive"))
    )
    (net (code "214") (name "OP29") (class "Default")
      (node (ref "OK29") (pin "1") (pinfunction "A_1") (pintype "passive"))
      (node (ref "R38") (pin "2") (pinfunction "2_2") (pintype "passive"))
    )
    (net (code "215") (name "OP30") (class "Default")
      (node (ref "OK30") (pin "1") (pinfunction "A_1") (pintype "passive"))
      (node (ref "R39") (pin "2") (pinfunction "2_2") (pintype "passive"))
    )
    (net (code "216") (name "OP31") (class "Default")
      (node (ref "OK31") (pin "1") (pinfunction "A_1") (pintype "passive"))
      (node (ref "R40") (pin "2") (pinfunction "2_2") (pintype "passive"))
    )
    (net (code "217") (name "OP32") (class "Default")
      (node (ref "OK32") (pin "1") (pinfunction "A_1") (pintype "passive"))
      (node (ref "R41") (pin "2") (pinfunction "2_2") (pintype "passive"))
    )
    (net (code "218") (name "RLY1") (class "Default")
      (node (ref "D1") (pin "A") (pinfunction "A_A") (pintype "passive"))
      (node (ref "D33") (pin "C") (pinfunction "C_C") (pintype "passive"))
      (node (ref "K1") (pin "2") (pinfunction "2_2") (pintype "passive"))
      (node (ref "K33") (pin "1") (pinfunction "1_1") (pintype "passive"))
      (node (ref "OK1") (pin "4") (pinfunction "COL_4") (pintype "passive"))
    )
    (net (code "219") (name "RLY2") (class "Default")
      (node (ref "D2") (pin "A") (pinfunction "A_A") (pintype "passive"))
      (node (ref "D34") (pin "C") (pinfunction "C_C") (pintype "passive"))
      (node (ref "K2") (pin "2") (pinfunction "2_2") (pintype "passive"))
      (node (ref "K33") (pin "2") (pinfunction "2_2") (pintype "passive"))
      (node (ref "OK2") (pin "4") (pinfunction "COL_4") (pintype "passive"))
    )
    (net (code "220") (name "RLY3") (class "Default")
      (node (ref "D3") (pin "A") (pinfunction "A_A") (pintype "passive"))
      (node (ref "D35") (pin "C") (pinfunction "C_C") (pintype "passive"))
      (node (ref "K3") (pin "2") (pinfunction "2_2") (pintype "passive"))
      (node (ref "K33") (pin "3") (pinfunction "3_3") (pintype "passive"))
      (node (ref "OK3") (pin "4") (pinfunction "COL_4") (pintype "passive"))
    )
    (net (code "221") (name "RLY4") (class "Default")
      (node (ref "D36") (pin "C") (pinfunction "C_C") (pintype "passive"))
      (node (ref "D4") (pin "A") (pinfunction "A_A") (pintype "passive"))
      (node (ref "K33") (pin "4") (pinfunction "4_4") (pintype "passive"))
      (node (ref "K4") (pin "2") (pinfunction "2_2") (pintype "passive"))
      (node (ref "OK4") (pin "4") (pinfunction "COL_4") (pintype "passive"))
    )
    (net (code "222") (name "RLY5") (class "Default")
      (node (ref "D37") (pin "C") (pinfunction "C_C") (pintype "passive"))
      (node (ref "D5") (pin "A") (pinfunction "A_A") (pintype "passive"))
      (node (ref "K33") (pin "5") (pinfunction "5_5") (pintype "passive"))
      (node (ref "K5") (pin "2") (pinfunction "2_2") (pintype "passive"))
      (node (ref "OK5") (pin "4") (pinfunction "COL_4") (pintype "passive"))
    )
    (net (code "223") (name "RLY6") (class "Default")
      (node (ref "D38") (pin "C") (pinfunction "C_C") (pintype "passive"))
      (node (ref "D6") (pin "A") (pinfunction "A_A") (pintype "passive"))
      (node (ref "K33") (pin "6") (pinfunction "6_6") (pintype "passive"))
      (node (ref "K6") (pin "2") (pinfunction "2_2") (pintype "passive"))
      (node (ref "OK6") (pin "4") (pinfunction "COL_4") (pintype "passive"))
    )
    (net (code "224") (name "RLY7") (class "Default")
      (node (ref "D39") (pin "C") (pinfunction "C_C") (pintype "passive"))
      (node (ref "D7") (pin "A") (pinfunction "A_A") (pintype "passive"))
      (node (ref "K33") (pin "7") (pinfunction "7_7") (pintype "passive"))
      (node (ref "K7") (pin "2") (pinfunction "2_2") (pintype "passive"))
      (node (ref "OK7") (pin "4") (pinfunction "COL_4") (pintype "passive"))
    )
    (net (code "225") (name "RLY8") (class "Default")
      (node (ref "D40") (pin "C") (pinfunction "C_C") (pintype "passive"))
      (node (ref "D8") (pin "A") (pinfunction "A_A") (pintype "passive"))
      (node (ref "K33") (pin "8") (pinfunction "8_8") (pintype "passive"))
      (node (ref "K8") (pin "2") (pinfunction "2_2") (pintype "passive"))
      (node (ref "OK8") (pin "4") (pinfunction "COL_4") (pintype "passive"))
    )
    (net (code "226") (name "RLY9") (class "Default")
      (node (ref "D41") (pin "C") (pinfunction "C_C") (pintype "passive"))
      (node (ref "D9") (pin "A") (pinfunction "A_A") (pintype "passive"))
      (node (ref "K33") (pin "9") (pinfunction "9_9") (pintype "passive"))
      (node (ref "K9") (pin "2") (pinfunction "2_2") (pintype "passive"))
      (node (ref "OK17") (pin "4") (pinfunction "COL_4") (pintype "passive"))
    )
    (net (code "227") (name "RLY10") (class "Default")
      (node (ref "D10") (pin "A") (pinfunction "A_A") (pintype "passive"))
      (node (ref "D42") (pin "C") (pinfunction "C_C") (pintype "passive"))
      (node (ref "K10") (pin "2") (pinfunction "2_2") (pintype "passive"))
      (node (ref "K33") (pin "10") (pinfunction "10_10") (pintype "passive"))
      (node (ref "OK18") (pin "4") (pinfunction "COL_4") (pintype "passive"))
    )
    (net (code "228") (name "RLY11") (class "Default")
      (node (ref "D11") (pin "A") (pinfunction "A_A") (pintype "passive"))
      (node (ref "D43") (pin "C") (pinfunction "C_C") (pintype "passive"))
      (node (ref "K11") (pin "2") (pinfunction "2_2") (pintype "passive"))
      (node (ref "K33") (pin "11") (pinfunction "11_11") (pintype "passive"))
      (node (ref "OK19") (pin "4") (pinfunction "COL_4") (pintype "passive"))
    )
    (net (code "229") (name "RLY12") (class "Default")
      (node (ref "D12") (pin "A") (pinfunction "A_A") (pintype "passive"))
      (node (ref "D44") (pin "C") (pinfunction "C_C") (pintype "passive"))
      (node (ref "K12") (pin "2") (pinfunction "2_2") (pintype "passive"))
      (node (ref "K33") (pin "12") (pinfunction "12_12") (pintype "passive"))
      (node (ref "OK20") (pin "4") (pinfunction "COL_4") (pintype "passive"))
    )
    (net (code "230") (name "RLY13") (class "Default")
      (node (ref "D13") (pin "A") (pinfunction "A_A") (pintype "passive"))
      (node (ref "D45") (pin "C") (pinfunction "C_C") (pintype "passive"))
      (node (ref "K13") (pin "2") (pinfunction "2_2") (pintype "passive"))
      (node (ref "K33") (pin "13") (pinfunction "13_13") (pintype "passive"))
      (node (ref "OK21") (pin "4") (pinfunction "COL_4") (pintype "passive"))
    )
    (net (code "231") (name "RLY14") (class "Default")
      (node (ref "D14") (pin "A") (pinfunction "A_A") (pintype "passive"))
      (node (ref "D46") (pin "C") (pinfunction "C_C") (pintype "passive"))
      (node (ref "K14") (pin "2") (pinfunction "2_2") (pintype "passive"))
      (node (ref "K33") (pin "14") (pinfunction "14_14") (pintype "passive"))
      (node (ref "OK22") (pin "4") (pinfunction "COL_4") (pintype "passive"))
    )
    (net (code "232") (name "RLY15") (class "Default")
      (node (ref "D15") (pin "A") (pinfunction "A_A") (pintype "passive"))
      (node (ref "D47") (pin "C") (pinfunction "C_C") (pintype "passive"))
      (node (ref "K15") (pin "2") (pinfunction "2_2") (pintype "passive"))
      (node (ref "K33") (pin "15") (pinfunction "15_15") (pintype "passive"))
      (node (ref "OK23") (pin "4") (pinfunction "COL_4") (pintype "passive"))
    )
    (net (code "233") (name "RLY16") (class "Default")
      (node (ref "D16") (pin "A") (pinfunction "A_A") (pintype "passive"))
      (node (ref "D48") (pin "C") (pinfunction "C_C") (pintype "passive"))
      (node (ref "K16") (pin "2") (pinfunction "2_2") (pintype "passive"))
      (node (ref "K33") (pin "16") (pinfunction "16_16") (pintype "passive"))
      (node (ref "OK24") (pin "4") (pinfunction "COL_4") (pintype "passive"))
    )
    (net (code "234") (name "RLY17") (class "Default")
      (node (ref "D17") (pin "A") (pinfunction "A_A") (pintype "passive"))
      (node (ref "D49") (pin "C") (pinfunction "C_C") (pintype "passive"))
      (node (ref "K17") (pin "2") (pinfunction "2_2") (pintype "passive"))
      (node (ref "K33") (pin "17") (pinfunction "17_17") (pintype "passive"))
      (node (ref "OK9") (pin "4") (pinfunction "COL_4") (pintype "passive"))
    )
    (net (code "235") (name "RLY18") (class "Default")
      (node (ref "D18") (pin "A") (pinfunction "A_A") (pintype "passive"))
      (node (ref "D50") (pin "C") (pinfunction "C_C") (pintype "passive"))
      (node (ref "K18") (pin "2") (pinfunction "2_2") (pintype "passive"))
      (node (ref "K33") (pin "18") (pinfunction "18_18") (pintype "passive"))
      (node (ref "OK10") (pin "4") (pinfunction "COL_4") (pintype "passive"))
    )
    (net (code "236") (name "RLY19") (class "Default")
      (node (ref "D19") (pin "A") (pinfunction "A_A") (pintype "passive"))
      (node (ref "D51") (pin "C") (pinfunction "C_C") (pintype "passive"))
      (node (ref "K19") (pin "2") (pinfunction "2_2") (pintype "passive"))
      (node (ref "K33") (pin "19") (pinfunction "19_19") (pintype "passive"))
      (node (ref "OK11") (pin "4") (pinfunction "COL_4") (pintype "passive"))
    )
    (net (code "237") (name "RLY20") (class "Default")
      (node (ref "D20") (pin "A") (pinfunction "A_A") (pintype "passive"))
      (node (ref "D52") (pin "C") (pinfunction "C_C") (pintype "passive"))
      (node (ref "K20") (pin "2") (pinfunction "2_2") (pintype "passive"))
      (node (ref "K33") (pin "20") (pinfunction "20_20") (pintype "passive"))
      (node (ref "OK12") (pin "4") (pinfunction "COL_4") (pintype "passive"))
    )
    (net (code "238") (name "RLY21") (class "Default")
      (node (ref "D21") (pin "A") (pinfunction "A_A") (pintype "passive"))
      (node (ref "D53") (pin "C") (pinfunction "C_C") (pintype "passive"))
      (node (ref "K21") (pin "2") (pinfunction "2_2") (pintype "passive"))
      (node (ref "K33") (pin "21") (pinfunction "21_21") (pintype "passive"))
      (node (ref "OK13") (pin "4") (pinfunction "COL_4") (pintype "passive"))
    )
    (net (code "239") (name "RLY22") (class "Default")
      (node (ref "D22") (pin "A") (pinfunction "A_A") (pintype "passive"))
      (node (ref "D54") (pin "C") (pinfunction "C_C") (pintype "passive"))
      (node (ref "K22") (pin "2") (pinfunction "2_2") (pintype "passive"))
      (node (ref "K33") (pin "22") (pinfunction "22_22") (pintype "passive"))
      (node (ref "OK14") (pin "4") (pinfunction "COL_4") (pintype "passive"))
    )
    (net (code "240") (name "RLY23") (class "Default")
      (node (ref "D23") (pin "A") (pinfunction "A_A") (pintype "passive"))
      (node (ref "D55") (pin "C") (pinfunction "C_C") (pintype "passive"))
      (node (ref "K23") (pin "2") (pinfunction "2_2") (pintype "passive"))
      (node (ref "K33") (pin "23") (pinfunction "23_23") (pintype "passive"))
      (node (ref "OK15") (pin "4") (pinfunction "COL_4") (pintype "passive"))
    )
    (net (code "241") (name "RLY24") (class "Default")
      (node (ref "D24") (pin "A") (pinfunction "A_A") (pintype "passive"))
      (node (ref "D56") (pin "C") (pinfunction "C_C") (pintype "passive"))
      (node (ref "K24") (pin "2") (pinfunction "2_2") (pintype "passive"))
      (node (ref "K33") (pin "24") (pinfunction "24_24") (pintype "passive"))
      (node (ref "OK16") (pin "4") (pinfunction "COL_4") (pintype "passive"))
    )
    (net (code "242") (name "RLY25") (class "Default")
      (node (ref "D25") (pin "A") (pinfunction "A_A") (pintype "passive"))
      (node (ref "D57") (pin "C") (pinfunction "C_C") (pintype "passive"))
      (node (ref "K25") (pin "2") (pinfunction "2_2") (pintype "passive"))
      (node (ref "K33") (pin "25") (pinfunction "25_25") (pintype "passive"))
      (node (ref "OK25") (pin "4") (pinfunction "COL_4") (pintype "passive"))
    )
    (net (code "243") (name "RLY26") (class "Default")
      (node (ref "D26") (pin "A") (pinfunction "A_A") (pintype "passive"))
      (node (ref "D58") (pin "C") (pinfunction "C_C") (pintype "passive"))
      (node (ref "K26") (pin "2") (pinfunction "2_2") (pintype "passive"))
      (node (ref "K33") (pin "26") (pinfunction "26_26") (pintype "passive"))
      (node (ref "OK26") (pin "4") (pinfunction "COL_4") (pintype "passive"))
    )
    (net (code "244") (name "RLY27") (class "Default")
      (node (ref "D27") (pin "A") (pinfunction "A_A") (pintype "passive"))
      (node (ref "D59") (pin "C") (pinfunction "C_C") (pintype "passive"))
      (node (ref "K27") (pin "2") (pinfunction "2_2") (pintype "passive"))
      (node (ref "K33") (pin "27") (pinfunction "27_27") (pintype "passive"))
      (node (ref "OK27") (pin "4") (pinfunction "COL_4") (pintype "passive"))
    )
    (net (code "245") (name "RLY28") (class "Default")
      (node (ref "D28") (pin "A") (pinfunction "A_A") (pintype "passive"))
      (node (ref "D60") (pin "C") (pinfunction "C_C") (pintype "passive"))
      (node (ref "K28") (pin "2") (pinfunction "2_2") (pintype "passive"))
      (node (ref "K33") (pin "28") (pinfunction "28_28") (pintype "passive"))
      (node (ref "OK28") (pin "4") (pinfunction "COL_4") (pintype "passive"))
    )
    (net (code "246") (name "RLY29") (class "Default")
      (node (ref "D29") (pin "A") (pinfunction "A_A") (pintype "passive"))
      (node (ref "D61") (pin "C") (pinfunction "C_C") (pintype "passive"))
      (node (ref "K29") (pin "2") (pinfunction "2_2") (pintype "passive"))
      (node (ref "K33") (pin "29") (pinfunction "29_29") (pintype "passive"))
      (node (ref "OK29") (pin "4") (pinfunction "COL_4") (pintype "passive"))
    )
    (net (code "247") (name "RLY30") (class "Default")
      (node (ref "D30") (pin "A") (pinfunction "A_A") (pintype "passive"))
      (node (ref "D62") (pin "C") (pinfunction "C_C") (pintype "passive"))
      (node (ref "K30") (pin "2") (pinfunction "2_2") (pintype "passive"))
      (node (ref "K33") (pin "30") (pinfunction "30_30") (pintype "passive"))
      (node (ref "OK30") (pin "4") (pinfunction "COL_4") (pintype "passive"))
    )
    (net (code "248") (name "RLY31") (class "Default")
      (node (ref "D31") (pin "A") (pinfunction "A_A") (pintype "passive"))
      (node (ref "D63") (pin "C") (pinfunction "C_C") (pintype "passive"))
      (node (ref "K31") (pin "2") (pinfunction "2_2") (pintype "passive"))
      (node (ref "K33") (pin "31") (pinfunction "31_31") (pintype "passive"))
      (node (ref "OK31") (pin "4") (pinfunction "COL_4") (pintype "passive"))
    )
    (net (code "249") (name "RLY32") (class "Default")
      (node (ref "D32") (pin "A") (pinfunction "A_A") (pintype "passive"))
      (node (ref "D64") (pin "C") (pinfunction "C_C") (pintype "passive"))
      (node (ref "K32") (pin "2") (pinfunction "2_2") (pintype "passive"))
      (node (ref "K33") (pin "32") (pinfunction "32_32") (pintype "passive"))
      (node (ref "OK32") (pin "4") (pinfunction "COL_4") (pintype "passive"))
    )
    (net (code "250") (name "ROW1") (class "Default")
      (node (ref "K34") (pin "1") (pinfunction "1_1") (pintype "passive"))
      (node (ref "U1") (pin "4") (pinfunction "(XCK0/AIN0)PE2_4") (pintype "bidirectional"))
    )
    (net (code "251") (name "ROW2") (class "Default")
      (node (ref "K34") (pin "2") (pinfunction "2_2") (pintype "passive"))
      (node (ref "U1") (pin "5") (pinfunction "(OC3A/AIN1)PE3_5") (pintype "bidirectional"))
    )
    (net (code "252") (name "ROW3") (class "Default")
      (node (ref "K34") (pin "3") (pinfunction "3_3") (pintype "passive"))
      (node (ref "U1") (pin "6") (pinfunction "(OC3B/INT4)PE4_6") (pintype "bidirectional"))
    )
    (net (code "253") (name "ROW4") (class "Default")
      (node (ref "K34") (pin "4") (pinfunction "4_4") (pintype "passive"))
      (node (ref "U1") (pin "7") (pinfunction "(OC3C/INT5)PE5_7") (pintype "bidirectional"))
    )
    (net (code "254") (name "ROW5") (class "Default")
      (node (ref "K34") (pin "5") (pinfunction "5_5") (pintype "passive"))
      (node (ref "U1") (pin "8") (pinfunction "(T3/INT6)PE6_8") (pintype "bidirectional"))
    )
    (net (code "255") (name "ROW6") (class "Default")
      (node (ref "K34") (pin "6") (pinfunction "6_6") (pintype "passive"))
      (node (ref "U1") (pin "9") (pinfunction "(CLKO/ICP3/INT7)PE7_9") (pintype "bidirectional"))
    )
    (net (code "256") (name "RS") (class "Default")
      (node (ref "K34") (pin "15") (pinfunction "15_15") (pintype "passive"))
      (node (ref "U1") (pin "51") (pinfunction "(WR)PG0_51") (pintype "bidirectional"))
    )
    (net (code "257") (name "RST") (class "Default")
      (node (ref "J1") (pin "5") (pinfunction "RESET_5") (pintype "passive"))
      (node (ref "R3") (pin "1") (pinfunction "1_1") (pintype "passive"))
      (node (ref "S31") (pin "A2") (pinfunction "1_A2") (pintype "passive"))
      (node (ref "U1") (pin "30") (pinfunction "RESET_30") (pintype "input"))
    )
    (net (code "258") (name "RX") (class "Default")
      (node (ref "U$6") (pin "15") (pinfunction "R1OUT_15") (pintype "bidirectional"))
      (node (ref "U$8") (pin "1") (pinfunction "RO_1") (pintype "bidirectional"))
      (node (ref "U1") (pin "2") (pinfunction "(RXD0/PCIN8)PE0_2") (pintype "bidirectional"))
    )
    (net (code "259") (name "RX_PC") (class "Default")
      (node (ref "U$6") (pin "16") (pinfunction "R1IN_16") (pintype "bidirectional"))
      (node (ref "X7") (pin "3") (pinfunction "F_3") (pintype "passive"))
    )
    (net (code "260") (name "SCK") (class "Default")
      (node (ref "J1") (pin "7") (pinfunction "SCK_7") (pintype "passive"))
      (node (ref "U$3") (pin "13") (pinfunction "CLK_13") (pintype "input"))
      (node (ref "U$4") (pin "1") (pinfunction "SCLK_1") (pintype "bidirectional"))
      (node (ref "U$5") (pin "1") (pinfunction "SCLK_1") (pintype "bidirectional"))
      (node (ref "U1") (pin "20") (pinfunction "(SCK/PCINT1)PB1_20") (pintype "bidirectional"))
    )
    (net (code "261") (name "SCL") (class "Default")
      (node (ref "R4") (pin "2") (pinfunction "2_2") (pintype "passive"))
      (node (ref "U$1") (pin "6") (pinfunction "SCL_6") (pintype "input"))
      (node (ref "U$2") (pin "6") (pinfunction "SCL_6") (pintype "bidirectional"))
      (node (ref "U1") (pin "43") (pinfunction "(SCL/INT0)PD0_43") (pintype "bidirectional"))
    )
    (net (code "262") (name "SDA") (class "Default")
      (node (ref "R5") (pin "2") (pinfunction "2_2") (pintype "passive"))
      (node (ref "U$1") (pin "5") (pinfunction "SDA_5") (pintype "bidirectional"))
      (node (ref "U$2") (pin "5") (pinfunction "SDA_5") (pintype "bidirectional"))
      (node (ref "U1") (pin "44") (pinfunction "(SDA/INT1)PD1_44") (pintype "bidirectional"))
    )
    (net (code "263") (name "SEGA") (class "Default")
      (node (ref "K35") (pin "9") (pinfunction "9_9") (pintype "passive"))
      (node (ref "U$3") (pin "14") (pinfunction "SEGA_14") (pintype "output"))
    )
    (net (code "264") (name "SEGB") (class "Default")
      (node (ref "K35") (pin "10") (pinfunction "10_10") (pintype "passive"))
      (node (ref "U$3") (pin "16") (pinfunction "SEGB_16") (pintype "output"))
    )
    (net (code "265") (name "SEGC") (class "Default")
      (node (ref "K35") (pin "11") (pinfunction "11_11") (pintype "passive"))
      (node (ref "U$3") (pin "20") (pinfunction "SEGC_20") (pintype "output"))
    )
    (net (code "266") (name "SEGD") (class "Default")
      (node (ref "K35") (pin "12") (pinfunction "12_12") (pintype "passive"))
      (node (ref "U$3") (pin "23") (pinfunction "SEGD_23") (pintype "output"))
    )
    (net (code "267") (name "SEGDP") (class "Default")
      (node (ref "K35") (pin "16") (pinfunction "16_16") (pintype "passive"))
      (node (ref "U$3") (pin "22") (pinfunction "SEGDP_22") (pintype "output"))
    )
    (net (code "268") (name "SEGE") (class "Default")
      (node (ref "K35") (pin "13") (pinfunction "13_13") (pintype "passive"))
      (node (ref "U$3") (pin "21") (pinfunction "SEGE_21") (pintype "output"))
    )
    (net (code "269") (name "SEGF") (class "Default")
      (node (ref "K35") (pin "14") (pinfunction "14_14") (pintype "passive"))
      (node (ref "U$3") (pin "15") (pinfunction "SEGF_15") (pintype "output"))
    )
    (net (code "270") (name "SEGG") (class "Default")
      (node (ref "K35") (pin "15") (pinfunction "15_15") (pintype "passive"))
      (node (ref "U$3") (pin "17") (pinfunction "SEGG_17") (pintype "output"))
    )
    (net (code "271") (name "SQW{slash}INT") (class "Default")
      (node (ref "R6") (pin "2") (pinfunction "2_2") (pintype "passive"))
      (node (ref "U$2") (pin "7") (pinfunction "SQW_7") (pintype "bidirectional"))
      (node (ref "U1") (pin "45") (pinfunction "(RXD1/INT2)PD2_45") (pintype "bidirectional"))
    )
    (net (code "272") (name "T1_DRDY") (class "Default")
      (node (ref "U$4") (pin "12") (pinfunction "DRDY_12") (pintype "bidirectional"))
      (node (ref "U1") (pin "25") (pinfunction "(OC1B/PCINT6)PB6_25") (pintype "bidirectional"))
    )
    (net (code "273") (name "T1_SS") (class "Default")
      (node (ref "U$4") (pin "4") (pinfunction "CS_4") (pintype "input"))
      (node (ref "U1") (pin "23") (pinfunction "(OC2A/PCINT4)PB4_23") (pintype "bidirectional"))
    )
    (net (code "274") (name "T2_DRDY") (class "Default")
      (node (ref "U$5") (pin "12") (pinfunction "DRDY_12") (pintype "bidirectional"))
      (node (ref "U1") (pin "26") (pinfunction "(OC0A/OC1C/PCINT7)PB7_26") (pintype "bidirectional"))
    )
    (net (code "275") (name "T2_S1+") (class "Default")
      (node (ref "C29") (pin "1") (pinfunction "1_1") (pintype "passive"))
      (node (ref "R82") (pin "1") (pinfunction "1_1") (pintype "passive"))
      (node (ref "U$5") (pin "7") (pinfunction "AIN1+_7") (pintype "input"))
    )
    (net (code "276") (name "T2_S1-") (class "Default")
      (node (ref "C30") (pin "1") (pinfunction "1_1") (pintype "passive"))
      (node (ref "R83") (pin "1") (pinfunction "1_1") (pintype "passive"))
      (node (ref "U$5") (pin "8") (pinfunction "AIN1-_8") (pintype "input"))
    )
    (net (code "277") (name "T2_S2+") (class "Default")
      (node (ref "C31") (pin "1") (pinfunction "1_1") (pintype "passive"))
      (node (ref "R84") (pin "1") (pinfunction "1_1") (pintype "passive"))
      (node (ref "U$5") (pin "6") (pinfunction "AIN2+_6") (pintype "input"))
    )
    (net (code "278") (name "T2_S2-") (class "Default")
      (node (ref "C32") (pin "1") (pinfunction "1_1") (pintype "passive"))
      (node (ref "R85") (pin "1") (pinfunction "1_1") (pintype "passive"))
      (node (ref "U$5") (pin "11") (pinfunction "AIN2-_11") (pintype "input"))
    )
    (net (code "279") (name "T2_SS") (class "Default")
      (node (ref "U$5") (pin "4") (pinfunction "CS_4") (pintype "input"))
      (node (ref "U1") (pin "24") (pinfunction "(OC1A/PCINT5)PB5_24") (pintype "bidirectional"))
    )
    (net (code "280") (name "TER1") (class "Default")
      (node (ref "K1") (pin "S") (pinfunction "S_S") (pintype "passive"))
      (node (ref "X3") (pin "2") (pinfunction "1_2") (pintype "passive"))
    )
    (net (code "281") (name "TER2") (class "Default")
      (node (ref "K2") (pin "S") (pinfunction "S_S") (pintype "passive"))
      (node (ref "X3") (pin "3") (pinfunction "1_3") (pintype "passive"))
    )
    (net (code "282") (name "TER3") (class "Default")
      (node (ref "K3") (pin "S") (pinfunction "S_S") (pintype "passive"))
      (node (ref "X3") (pin "4") (pinfunction "1_4") (pintype "passive"))
    )
    (net (code "283") (name "TER4") (class "Default")
      (node (ref "K4") (pin "S") (pinfunction "S_S") (pintype "passive"))
      (node (ref "X3") (pin "5") (pinfunction "1_5") (pintype "passive"))
    )
    (net (code "284") (name "TER5") (class "Default")
      (node (ref "K5") (pin "S") (pinfunction "S_S") (pintype "passive"))
      (node (ref "X3") (pin "6") (pinfunction "1_6") (pintype "passive"))
    )
    (net (code "285") (name "TER6") (class "Default")
      (node (ref "K6") (pin "S") (pinfunction "S_S") (pintype "passive"))
      (node (ref "X3") (pin "7") (pinfunction "1_7") (pintype "passive"))
    )
    (net (code "286") (name "TER7") (class "Default")
      (node (ref "K7") (pin "S") (pinfunction "S_S") (pintype "passive"))
      (node (ref "X3") (pin "8") (pinfunction "1_8") (pintype "passive"))
    )
    (net (code "287") (name "TER8") (class "Default")
      (node (ref "K8") (pin "S") (pinfunction "S_S") (pintype "passive"))
      (node (ref "X3") (pin "9") (pinfunction "1_9") (pintype "passive"))
    )
    (net (code "288") (name "TER9") (class "Default")
      (node (ref "K9") (pin "S") (pinfunction "S_S") (pintype "passive"))
      (node (ref "X4") (pin "2") (pinfunction "1_2") (pintype "passive"))
    )
    (net (code "289") (name "TER10") (class "Default")
      (node (ref "K10") (pin "S") (pinfunction "S_S") (pintype "passive"))
      (node (ref "X4") (pin "3") (pinfunction "1_3") (pintype "passive"))
    )
    (net (code "290") (name "TER11") (class "Default")
      (node (ref "K11") (pin "S") (pinfunction "S_S") (pintype "passive"))
      (node (ref "X4") (pin "4") (pinfunction "1_4") (pintype "passive"))
    )
    (net (code "291") (name "TER12") (class "Default")
      (node (ref "K12") (pin "S") (pinfunction "S_S") (pintype "passive"))
      (node (ref "X4") (pin "5") (pinfunction "1_5") (pintype "passive"))
    )
    (net (code "292") (name "TER13") (class "Default")
      (node (ref "K13") (pin "S") (pinfunction "S_S") (pintype "passive"))
      (node (ref "X4") (pin "6") (pinfunction "1_6") (pintype "passive"))
    )
    (net (code "293") (name "TER14") (class "Default")
      (node (ref "K14") (pin "S") (pinfunction "S_S") (pintype "passive"))
      (node (ref "X4") (pin "7") (pinfunction "1_7") (pintype "passive"))
    )
    (net (code "294") (name "TER15") (class "Default")
      (node (ref "K15") (pin "S") (pinfunction "S_S") (pintype "passive"))
      (node (ref "X4") (pin "8") (pinfunction "1_8") (pintype "passive"))
    )
    (net (code "295") (name "TER16") (class "Default")
      (node (ref "K16") (pin "S") (pinfunction "S_S") (pintype "passive"))
      (node (ref "X4") (pin "9") (pinfunction "1_9") (pintype "passive"))
    )
    (net (code "296") (name "TER17") (class "Default")
      (node (ref "K17") (pin "S") (pinfunction "S_S") (pintype "passive"))
      (node (ref "X5") (pin "2") (pinfunction "1_2") (pintype "passive"))
    )
    (net (code "297") (name "TER18") (class "Default")
      (node (ref "K18") (pin "S") (pinfunction "S_S") (pintype "passive"))
      (node (ref "X5") (pin "3") (pinfunction "1_3") (pintype "passive"))
    )
    (net (code "298") (name "TER19") (class "Default")
      (node (ref "K19") (pin "S") (pinfunction "S_S") (pintype "passive"))
      (node (ref "X5") (pin "4") (pinfunction "1_4") (pintype "passive"))
    )
    (net (code "299") (name "TER20") (class "Default")
      (node (ref "K20") (pin "S") (pinfunction "S_S") (pintype "passive"))
      (node (ref "X5") (pin "5") (pinfunction "1_5") (pintype "passive"))
    )
    (net (code "300") (name "TER21") (class "Default")
      (node (ref "K21") (pin "S") (pinfunction "S_S") (pintype "passive"))
      (node (ref "X5") (pin "6") (pinfunction "1_6") (pintype "passive"))
    )
    (net (code "301") (name "TER22") (class "Default")
      (node (ref "K22") (pin "S") (pinfunction "S_S") (pintype "passive"))
      (node (ref "X5") (pin "7") (pinfunction "1_7") (pintype "passive"))
    )
    (net (code "302") (name "TER23") (class "Default")
      (node (ref "K23") (pin "S") (pinfunction "S_S") (pintype "passive"))
      (node (ref "X5") (pin "8") (pinfunction "1_8") (pintype "passive"))
    )
    (net (code "303") (name "TER24") (class "Default")
      (node (ref "K24") (pin "S") (pinfunction "S_S") (pintype "passive"))
      (node (ref "X5") (pin "9") (pinfunction "1_9") (pintype "passive"))
    )
    (net (code "304") (name "TER25") (class "Default")
      (node (ref "K25") (pin "S") (pinfunction "S_S") (pintype "passive"))
      (node (ref "X6") (pin "2") (pinfunction "1_2") (pintype "passive"))
    )
    (net (code "305") (name "TER26") (class "Default")
      (node (ref "K26") (pin "S") (pinfunction "S_S") (pintype "passive"))
      (node (ref "X6") (pin "3") (pinfunction "1_3") (pintype "passive"))
    )
    (net (code "306") (name "TER27") (class "Default")
      (node (ref "K27") (pin "S") (pinfunction "S_S") (pintype "passive"))
      (node (ref "X6") (pin "4") (pinfunction "1_4") (pintype "passive"))
    )
    (net (code "307") (name "TER28") (class "Default")
      (node (ref "K28") (pin "S") (pinfunction "S_S") (pintype "passive"))
      (node (ref "X6") (pin "5") (pinfunction "1_5") (pintype "passive"))
    )
    (net (code "308") (name "TER29") (class "Default")
      (node (ref "K29") (pin "S") (pinfunction "S_S") (pintype "passive"))
      (node (ref "X6") (pin "6") (pinfunction "1_6") (pintype "passive"))
    )
    (net (code "309") (name "TER30") (class "Default")
      (node (ref "K30") (pin "S") (pinfunction "S_S") (pintype "passive"))
      (node (ref "X6") (pin "7") (pinfunction "1_7") (pintype "passive"))
    )
    (net (code "310") (name "TER31") (class "Default")
      (node (ref "K31") (pin "S") (pinfunction "S_S") (pintype "passive"))
      (node (ref "X6") (pin "8") (pinfunction "1_8") (pintype "passive"))
    )
    (net (code "311") (name "TER32") (class "Default")
      (node (ref "K32") (pin "S") (pinfunction "S_S") (pintype "passive"))
      (node (ref "X6") (pin "9") (pinfunction "1_9") (pintype "passive"))
    )
    (net (code "312") (name "TT1_LED") (class "Default")
      (node (ref "R100") (pin "2") (pinfunction "2_2") (pintype "passive"))
      (node (ref "U1") (pin "12") (pinfunction "PH0(RXD2)_12") (pintype "bidirectional"))
    )
    (net (code "313") (name "TT2_LED") (class "Default")
      (node (ref "R101") (pin "2") (pinfunction "2_2") (pintype "passive"))
      (node (ref "U1") (pin "13") (pinfunction "PH1(TXD2)_13") (pintype "bidirectional"))
    )
    (net (code "314") (name "TT3_LED") (class "Default")
      (node (ref "R102") (pin "2") (pinfunction "2_2") (pintype "passive"))
      (node (ref "U1") (pin "14") (pinfunction "PH2(XCK2)_14") (pintype "bidirectional"))
    )
    (net (code "315") (name "TT4_LED") (class "Default")
      (node (ref "R103") (pin "2") (pinfunction "2_2") (pintype "passive"))
      (node (ref "U1") (pin "15") (pinfunction "PH3(OC4A)_15") (pintype "bidirectional"))
    )
    (net (code "316") (name "TT_LED1") (class "Default")
      (node (ref "K35") (pin "1") (pinfunction "1_1") (pintype "passive"))
      (node (ref "OK42") (pin "4") (pinfunction "COL_4") (pintype "passive"))
    )
    (net (code "317") (name "TT_LED2") (class "Default")
      (node (ref "K35") (pin "2") (pinfunction "2_2") (pintype "passive"))
      (node (ref "OK43") (pin "4") (pinfunction "COL_4") (pintype "passive"))
    )
    (net (code "318") (name "TT_LED3") (class "Default")
      (node (ref "K35") (pin "3") (pinfunction "3_3") (pintype "passive"))
      (node (ref "OK44") (pin "4") (pinfunction "COL_4") (pintype "passive"))
    )
    (net (code "319") (name "TT_LED4") (class "Default")
      (node (ref "K35") (pin "4") (pinfunction "4_4") (pintype "passive"))
      (node (ref "OK45") (pin "4") (pinfunction "COL_4") (pintype "passive"))
    )
    (net (code "320") (name "TX") (class "Default")
      (node (ref "U$6") (pin "13") (pinfunction "T1IN_13") (pintype "bidirectional"))
      (node (ref "U$8") (pin "4") (pinfunction "DI_4") (pintype "bidirectional"))
      (node (ref "U1") (pin "3") (pinfunction "(TXD0)PE1_3") (pintype "bidirectional"))
    )
    (net (code "321") (name "TX_PC") (class "Default")
      (node (ref "U$6") (pin "17") (pinfunction "T1OUT_17") (pintype "bidirectional"))
      (node (ref "X7") (pin "2") (pinfunction "F_2") (pintype "passive"))
    )
    (net (code "322") (name "T_S1+") (class "Default")
      (node (ref "C25") (pin "1") (pinfunction "1_1") (pintype "passive"))
      (node (ref "R78") (pin "1") (pinfunction "1_1") (pintype "passive"))
      (node (ref "U$4") (pin "7") (pinfunction "AIN1+_7") (pintype "input"))
    )
    (net (code "323") (name "T_S1-") (class "Default")
      (node (ref "C26") (pin "1") (pinfunction "1_1") (pintype "passive"))
      (node (ref "R79") (pin "1") (pinfunction "1_1") (pintype "passive"))
      (node (ref "U$4") (pin "8") (pinfunction "AIN1-_8") (pintype "input"))
    )
    (net (code "324") (name "T_S2+") (class "Default")
      (node (ref "C27") (pin "1") (pinfunction "1_1") (pintype "passive"))
      (node (ref "R80") (pin "1") (pinfunction "1_1") (pintype "passive"))
      (node (ref "U$4") (pin "6") (pinfunction "AIN2+_6") (pintype "input"))
    )
    (net (code "325") (name "T_S2-") (class "Default")
      (node (ref "C28") (pin "1") (pinfunction "1_1") (pintype "passive"))
      (node (ref "R81") (pin "1") (pinfunction "1_1") (pintype "passive"))
      (node (ref "U$4") (pin "11") (pinfunction "AIN2-_11") (pintype "input"))
    )
    (net (code "326") (name "VREF+") (class "Default")
      (node (ref "C19") (pin "1") (pinfunction "1_1") (pintype "passive"))
      (node (ref "C20") (pin "1") (pinfunction "1_1") (pintype "passive"))
      (node (ref "IC6") (pin "6") (pinfunction "VOUT_6") (pintype "input"))
      (node (ref "U$4") (pin "9") (pinfunction "REF+_9") (pintype "input"))
      (node (ref "U$5") (pin "9") (pinfunction "REF+_9") (pintype "input"))
    )
    (net (code "327") (name "WP") (class "Default")
      (node (ref "U$1") (pin "7") (pinfunction "WP_7") (pintype "input"))
      (node (ref "U1") (pin "50") (pinfunction "(T0)PD7_50") (pintype "bidirectional"))
    )
    (net (code "328") (name "unconnected-(G1-+-Pad+@1)") (class "Default")
      (node (ref "G1") (pin "+@1") (pinfunction "+_+@1") (pintype "passive"))
    )
    (net (code "329") (name "unconnected-(IC6-O{slash}P-Pad8)") (class "Default")
      (node (ref "IC6") (pin "8") (pinfunction "O/P_8") (pintype "passive"))
    )
    (net (code "330") (name "unconnected-(IC6-TEMP-Pad3)") (class "Default")
      (node (ref "IC6") (pin "3") (pinfunction "TEMP_3") (pintype "input"))
    )
    (net (code "331") (name "unconnected-(IC6-TRIM-Pad5)") (class "Default")
      (node (ref "IC6") (pin "5") (pinfunction "TRIM_5") (pintype "input"))
    )
    (net (code "332") (name "unconnected-(J1-NC-Pad3)") (class "Default")
      (node (ref "J1") (pin "3") (pinfunction "NC_3") (pintype "no_connect"))
    )
    (net (code "333") (name "unconnected-(K1-PadO)") (class "Default")
      (node (ref "K1") (pin "O") (pinfunction "O_O") (pintype "passive"))
    )
    (net (code "334") (name "unconnected-(K2-PadO)") (class "Default")
      (node (ref "K2") (pin "O") (pinfunction "O_O") (pintype "passive"))
    )
    (net (code "335") (name "unconnected-(K3-PadO)") (class "Default")
      (node (ref "K3") (pin "O") (pinfunction "O_O") (pintype "passive"))
    )
    (net (code "336") (name "unconnected-(K4-PadO)") (class "Default")
      (node (ref "K4") (pin "O") (pinfunction "O_O") (pintype "passive"))
    )
    (net (code "337") (name "unconnected-(K5-PadO)") (class "Default")
      (node (ref "K5") (pin "O") (pinfunction "O_O") (pintype "passive"))
    )
    (net (code "338") (name "unconnected-(K6-PadO)") (class "Default")
      (node (ref "K6") (pin "O") (pinfunction "O_O") (pintype "passive"))
    )
    (net (code "339") (name "unconnected-(K7-PadO)") (class "Default")
      (node (ref "K7") (pin "O") (pinfunction "O_O") (pintype "passive"))
    )
    (net (code "340") (name "unconnected-(K8-PadO)") (class "Default")
      (node (ref "K8") (pin "O") (pinfunction "O_O") (pintype "passive"))
    )
    (net (code "341") (name "unconnected-(K9-PadO)") (class "Default")
      (node (ref "K9") (pin "O") (pinfunction "O_O") (pintype "passive"))
    )
    (net (code "342") (name "unconnected-(K10-PadO)") (class "Default")
      (node (ref "K10") (pin "O") (pinfunction "O_O") (pintype "passive"))
    )
    (net (code "343") (name "unconnected-(K11-PadO)") (class "Default")
      (node (ref "K11") (pin "O") (pinfunction "O_O") (pintype "passive"))
    )
    (net (code "344") (name "unconnected-(K12-PadO)") (class "Default")
      (node (ref "K12") (pin "O") (pinfunction "O_O") (pintype "passive"))
    )
    (net (code "345") (name "unconnected-(K13-PadO)") (class "Default")
      (node (ref "K13") (pin "O") (pinfunction "O_O") (pintype "passive"))
    )
    (net (code "346") (name "unconnected-(K14-PadO)") (class "Default")
      (node (ref "K14") (pin "O") (pinfunction "O_O") (pintype "passive"))
    )
    (net (code "347") (name "unconnected-(K15-PadO)") (class "Default")
      (node (ref "K15") (pin "O") (pinfunction "O_O") (pintype "passive"))
    )
    (net (code "348") (name "unconnected-(K16-PadO)") (class "Default")
      (node (ref "K16") (pin "O") (pinfunction "O_O") (pintype "passive"))
    )
    (net (code "349") (name "unconnected-(K17-PadO)") (class "Default")
      (node (ref "K17") (pin "O") (pinfunction "O_O") (pintype "passive"))
    )
    (net (code "350") (name "unconnected-(K18-PadO)") (class "Default")
      (node (ref "K18") (pin "O") (pinfunction "O_O") (pintype "passive"))
    )
    (net (code "351") (name "unconnected-(K19-PadO)") (class "Default")
      (node (ref "K19") (pin "O") (pinfunction "O_O") (pintype "passive"))
    )
    (net (code "352") (name "unconnected-(K20-PadO)") (class "Default")
      (node (ref "K20") (pin "O") (pinfunction "O_O") (pintype "passive"))
    )
    (net (code "353") (name "unconnected-(K21-PadO)") (class "Default")
      (node (ref "K21") (pin "O") (pinfunction "O_O") (pintype "passive"))
    )
    (net (code "354") (name "unconnected-(K22-PadO)") (class "Default")
      (node (ref "K22") (pin "O") (pinfunction "O_O") (pintype "passive"))
    )
    (net (code "355") (name "unconnected-(K23-PadO)") (class "Default")
      (node (ref "K23") (pin "O") (pinfunction "O_O") (pintype "passive"))
    )
    (net (code "356") (name "unconnected-(K24-PadO)") (class "Default")
      (node (ref "K24") (pin "O") (pinfunction "O_O") (pintype "passive"))
    )
    (net (code "357") (name "unconnected-(K25-PadO)") (class "Default")
      (node (ref "K25") (pin "O") (pinfunction "O_O") (pintype "passive"))
    )
    (net (code "358") (name "unconnected-(K26-PadO)") (class "Default")
      (node (ref "K26") (pin "O") (pinfunction "O_O") (pintype "passive"))
    )
    (net (code "359") (name "unconnected-(K27-PadO)") (class "Default")
      (node (ref "K27") (pin "O") (pinfunction "O_O") (pintype "passive"))
    )
    (net (code "360") (name "unconnected-(K28-PadO)") (class "Default")
      (node (ref "K28") (pin "O") (pinfunction "O_O") (pintype "passive"))
    )
    (net (code "361") (name "unconnected-(K29-PadO)") (class "Default")
      (node (ref "K29") (pin "O") (pinfunction "O_O") (pintype "passive"))
    )
    (net (code "362") (name "unconnected-(K30-PadO)") (class "Default")
      (node (ref "K30") (pin "O") (pinfunction "O_O") (pintype "passive"))
    )
    (net (code "363") (name "unconnected-(K31-PadO)") (class "Default")
      (node (ref "K31") (pin "O") (pinfunction "O_O") (pintype "passive"))
    )
    (net (code "364") (name "unconnected-(K32-PadO)") (class "Default")
      (node (ref "K32") (pin "O") (pinfunction "O_O") (pintype "passive"))
    )
    (net (code "365") (name "unconnected-(U$6-INV-Pad11)") (class "Default")
      (node (ref "U$6") (pin "11") (pinfunction "INV_11") (pintype "bidirectional"))
    )
    (net (code "366") (name "unconnected-(U$6-R2IN-Pad9)") (class "Default")
      (node (ref "U$6") (pin "9") (pinfunction "R2IN_9") (pintype "bidirectional"))
    )
    (net (code "367") (name "unconnected-(U$6-R2OUT-Pad10)") (class "Default")
      (node (ref "U$6") (pin "10") (pinfunction "R2OUT_10") (pintype "bidirectional"))
    )
    (net (code "368") (name "unconnected-(U$6-T2IN-Pad12)") (class "Default")
      (node (ref "U$6") (pin "12") (pinfunction "T2IN_12") (pintype "bidirectional"))
    )
    (net (code "369") (name "unconnected-(U$6-T2OUT-Pad8)") (class "Default")
      (node (ref "U$6") (pin "8") (pinfunction "T2OUT_8") (pintype "bidirectional"))
    )
    (net (code "370") (name "unconnected-(U1-(ADC0)PF0-Pad97)") (class "Default")
      (node (ref "U1") (pin "97") (pinfunction "(ADC0)PF0_97") (pintype "bidirectional"))
    )
    (net (code "371") (name "unconnected-(U1-(ADC1)PF1-Pad96)") (class "Default")
      (node (ref "U1") (pin "96") (pinfunction "(ADC1)PF1_96") (pintype "bidirectional"))
    )
    (net (code "372") (name "unconnected-(U1-(ADC2)PF2-Pad95)") (class "Default")
      (node (ref "U1") (pin "95") (pinfunction "(ADC2)PF2_95") (pintype "bidirectional"))
    )
    (net (code "373") (name "unconnected-(U1-(ADC3)PF3-Pad94)") (class "Default")
      (node (ref "U1") (pin "94") (pinfunction "(ADC3)PF3_94") (pintype "bidirectional"))
    )
    (net (code "374") (name "unconnected-(U1-(ADC4{slash}TCK)PF4-Pad93)") (class "Default")
      (node (ref "U1") (pin "93") (pinfunction "(ADC4/TCK)PF4_93") (pintype "bidirectional"))
    )
    (net (code "375") (name "unconnected-(U1-(ADC5{slash}TMS)PF5-Pad92)") (class "Default")
      (node (ref "U1") (pin "92") (pinfunction "(ADC5/TMS)PF5_92") (pintype "bidirectional"))
    )
    (net (code "376") (name "unconnected-(U1-(ADC6{slash}TDO)PF6-Pad91)") (class "Default")
      (node (ref "U1") (pin "91") (pinfunction "(ADC6/TDO)PF6_91") (pintype "bidirectional"))
    )
    (net (code "377") (name "unconnected-(U1-(ADC7{slash}TDI)PF7-Pad90)") (class "Default")
      (node (ref "U1") (pin "90") (pinfunction "(ADC7/TDI)PF7_90") (pintype "bidirectional"))
    )
    (net (code "378") (name "unconnected-(U1-(TXD1{slash}INT3)PD3-Pad46)") (class "Default")
      (node (ref "U1") (pin "46") (pinfunction "(TXD1/INT3)PD3_46") (pintype "bidirectional"))
    )
    (net (code "379") (name "unconnected-(U1-AREF-Pad98)") (class "Default")
      (node (ref "U1") (pin "98") (pinfunction "AREF_98") (pintype "bidirectional"))
    )
    (net (code "380") (name "unconnected-(U1-PH4(OC4B)-Pad16)") (class "Default")
      (node (ref "U1") (pin "16") (pinfunction "PH4(OC4B)_16") (pintype "bidirectional"))
    )
    (net (code "381") (name "unconnected-(U1-PH5(OC4C)-Pad17)") (class "Default")
      (node (ref "U1") (pin "17") (pinfunction "PH5(OC4C)_17") (pintype "bidirectional"))
    )
    (net (code "382") (name "unconnected-(U1-PH6(OC2B)-Pad18)") (class "Default")
      (node (ref "U1") (pin "18") (pinfunction "PH6(OC2B)_18") (pintype "bidirectional"))
    )
    (net (code "383") (name "unconnected-(U1-PH7(T4)-Pad27)") (class "Default")
      (node (ref "U1") (pin "27") (pinfunction "PH7(T4)_27") (pintype "bidirectional"))
    )
    (net (code "384") (name "unconnected-(U1-PK0(ADC8{slash}PCINT16)-Pad89)") (class "Default")
      (node (ref "U1") (pin "89") (pinfunction "PK0(ADC8/PCINT16)_89") (pintype "bidirectional"))
    )
    (net (code "385") (name "unconnected-(U1-PK1(ADC9{slash}PCINT17)-Pad88)") (class "Default")
      (node (ref "U1") (pin "88") (pinfunction "PK1(ADC9/PCINT17)_88") (pintype "bidirectional"))
    )
    (net (code "386") (name "unconnected-(U1-PK2(ADC10{slash}PCINT18)-Pad87)") (class "Default")
      (node (ref "U1") (pin "87") (pinfunction "PK2(ADC10/PCINT18)_87") (pintype "bidirectional"))
    )
    (net (code "387") (name "unconnected-(U1-PK3(ADC11{slash}PCINT19)-Pad86)") (class "Default")
      (node (ref "U1") (pin "86") (pinfunction "PK3(ADC11/PCINT19)_86") (pintype "bidirectional"))
    )
    (net (code "388") (name "unconnected-(U1-PK4(ADC12{slash}PCINT20)-Pad85)") (class "Default")
      (node (ref "U1") (pin "85") (pinfunction "PK4(ADC12/PCINT20)_85") (pintype "bidirectional"))
    )
    (net (code "389") (name "unconnected-(U1-PK5(ADC13{slash}PCINT21)-Pad84)") (class "Default")
      (node (ref "U1") (pin "84") (pinfunction "PK5(ADC13/PCINT21)_84") (pintype "bidirectional"))
    )
    (net (code "390") (name "unconnected-(U1-PK6(ADC14{slash}PCINT22)-Pad83)") (class "Default")
      (node (ref "U1") (pin "83") (pinfunction "PK6(ADC14/PCINT22)_83") (pintype "bidirectional"))
    )
    (net (code "391") (name "unconnected-(U1-PK7(ADC15{slash}PCINT23)-Pad82)") (class "Default")
      (node (ref "U1") (pin "82") (pinfunction "PK7(ADC15/PCINT23)_82") (pintype "bidirectional"))
    )
    (net (code "392") (name "unconnected-(X7A-F-Pad1)") (class "Default")
      (node (ref "X7") (pin "1") (pinfunction "F_1") (pintype "passive"))
    )
    (net (code "393") (name "unconnected-(X7D-F-Pad4)") (class "Default")
      (node (ref "X7") (pin "4") (pinfunction "F_4") (pintype "passive"))
    )
    (net (code "394") (name "unconnected-(X7F-F-Pad6)") (class "Default")
      (node (ref "X7") (pin "6") (pinfunction "F_6") (pintype "passive"))
    )
    (net (code "395") (name "unconnected-(X7G-F-Pad7)") (class "Default")
      (node (ref "X7") (pin "7") (pinfunction "F_7") (pintype "passive"))
    )
    (net (code "396") (name "unconnected-(X7H-F-Pad8)") (class "Default")
      (node (ref "X7") (pin "8") (pinfunction "F_8") (pintype "passive"))
    )
    (net (code "397") (name "unconnected-(X7I-F-Pad9)") (class "Default")
      (node (ref "X7") (pin "9") (pinfunction "F_9") (pintype "passive"))
    )
  )
)
